# Dispenser_Motor_Controller.net
KiCad netlist of a schematic drawn in EasyEDA Pro
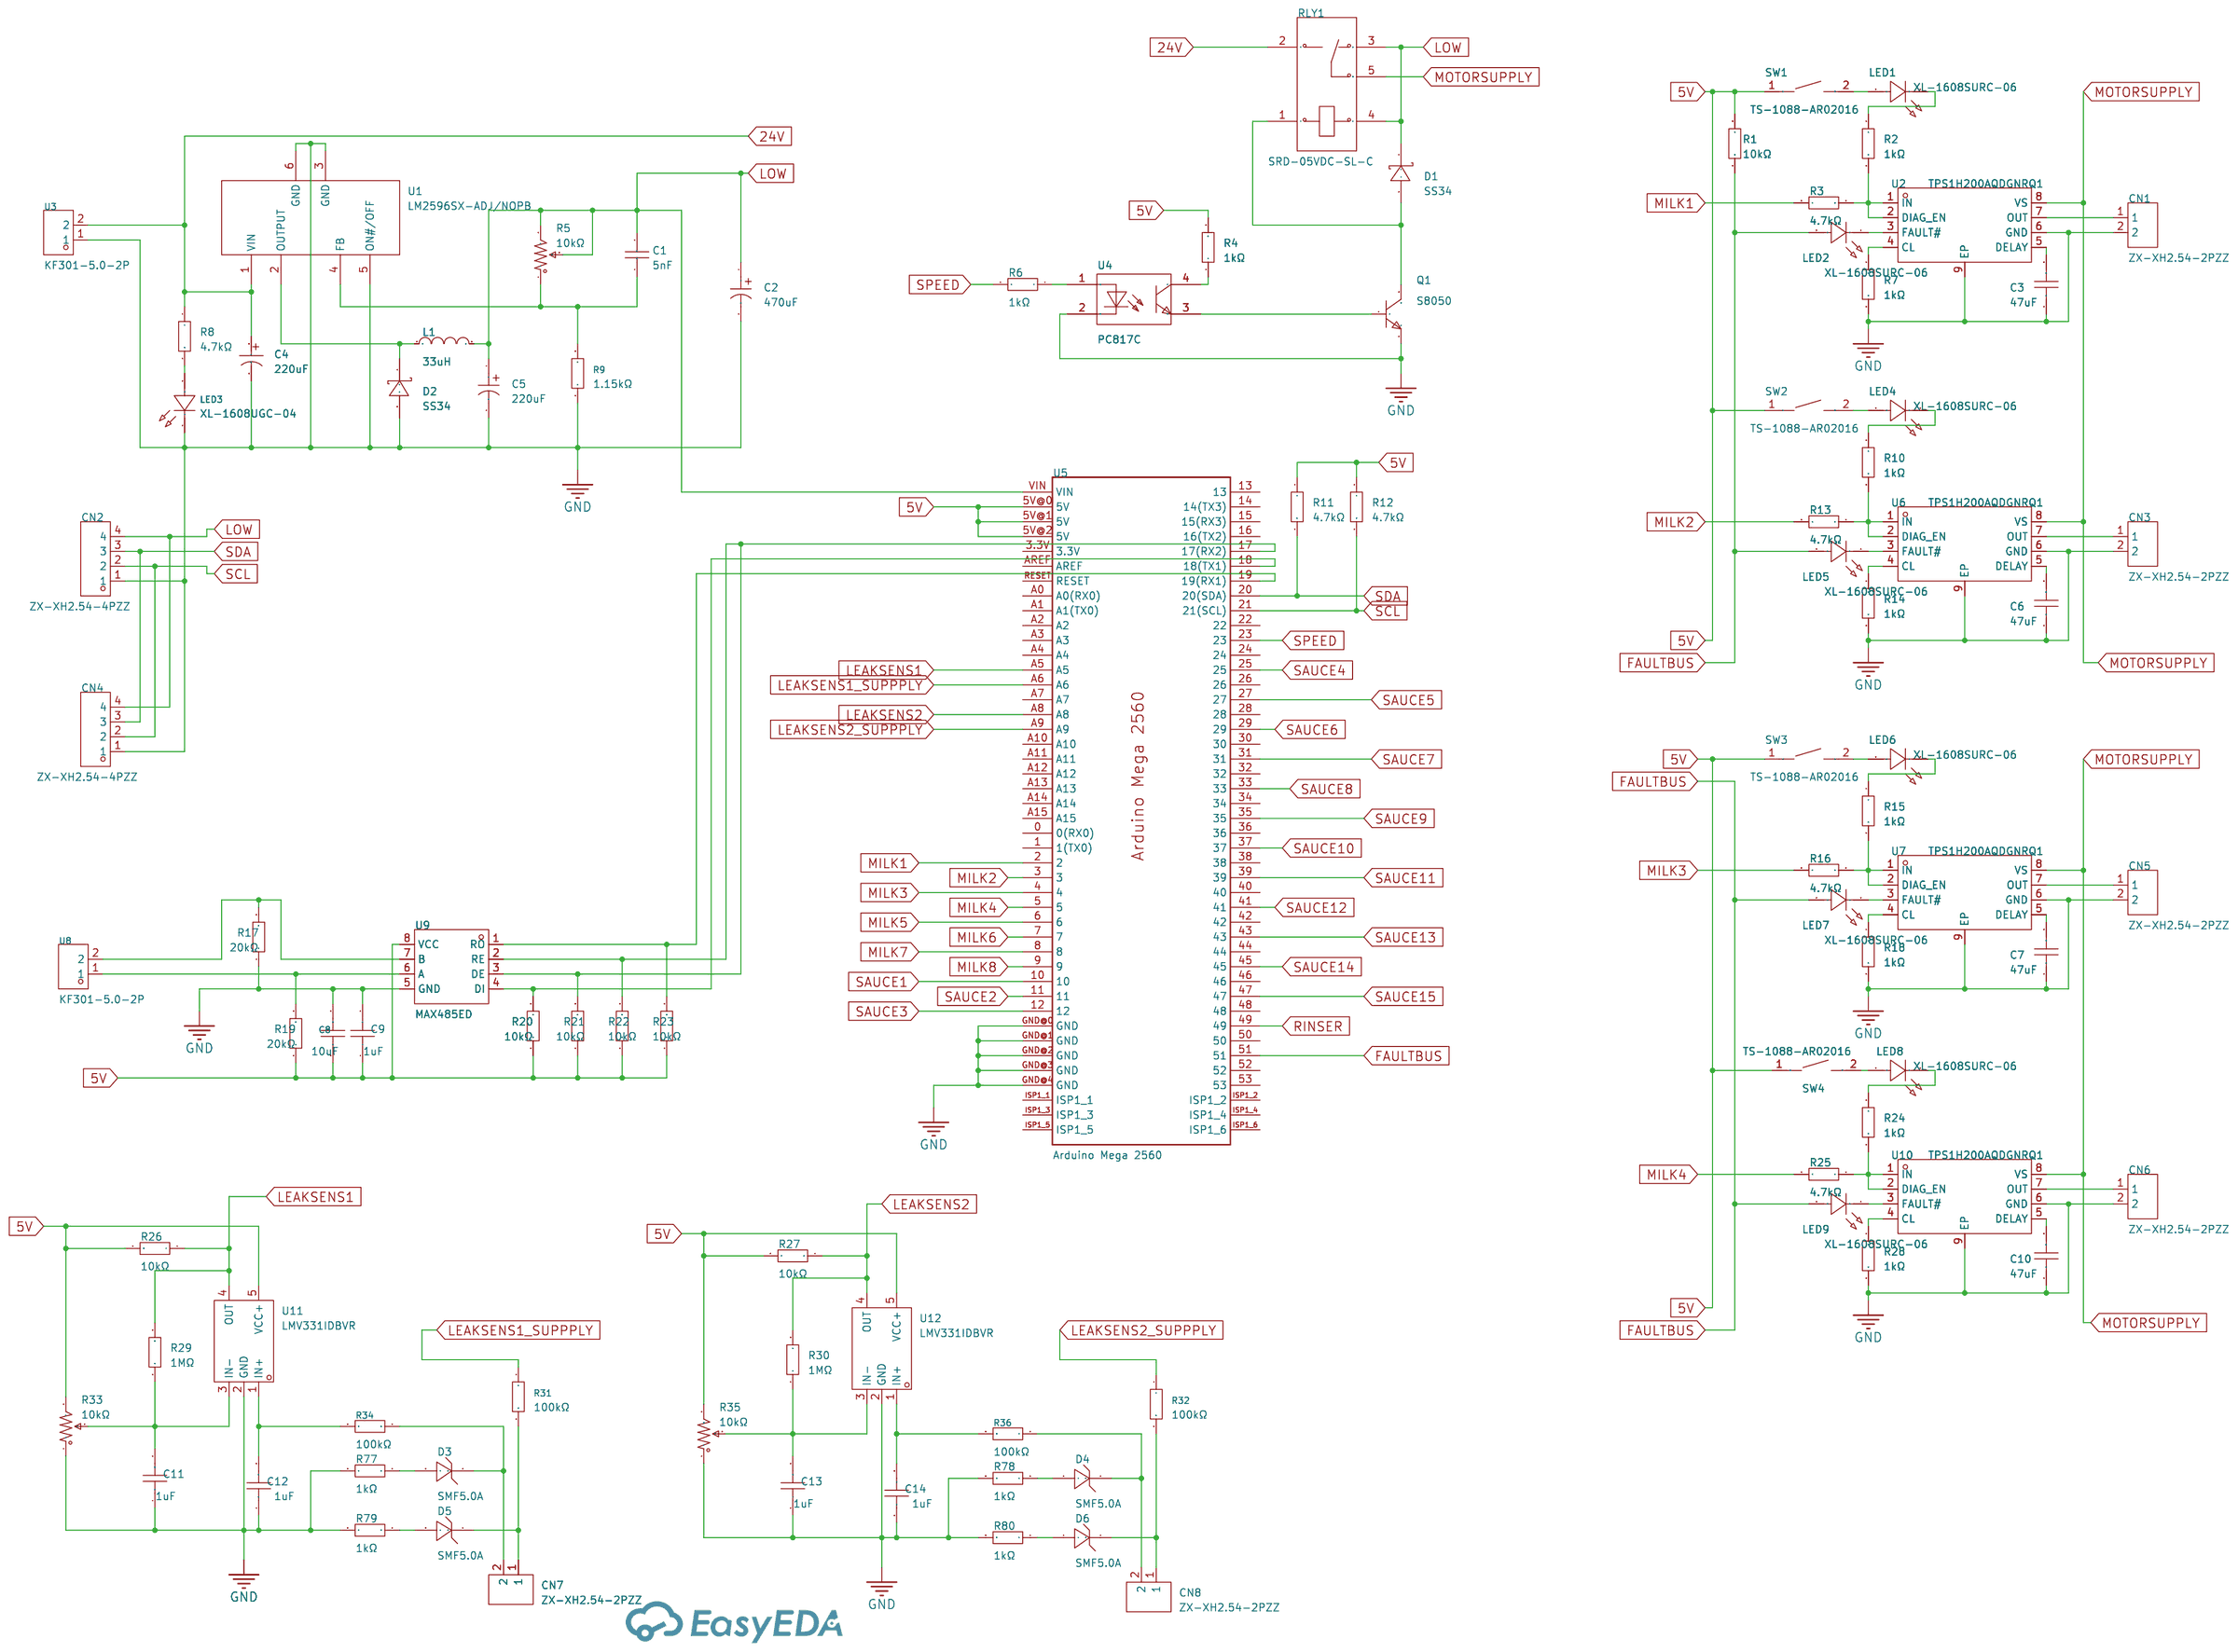
[diagram p0: P1]
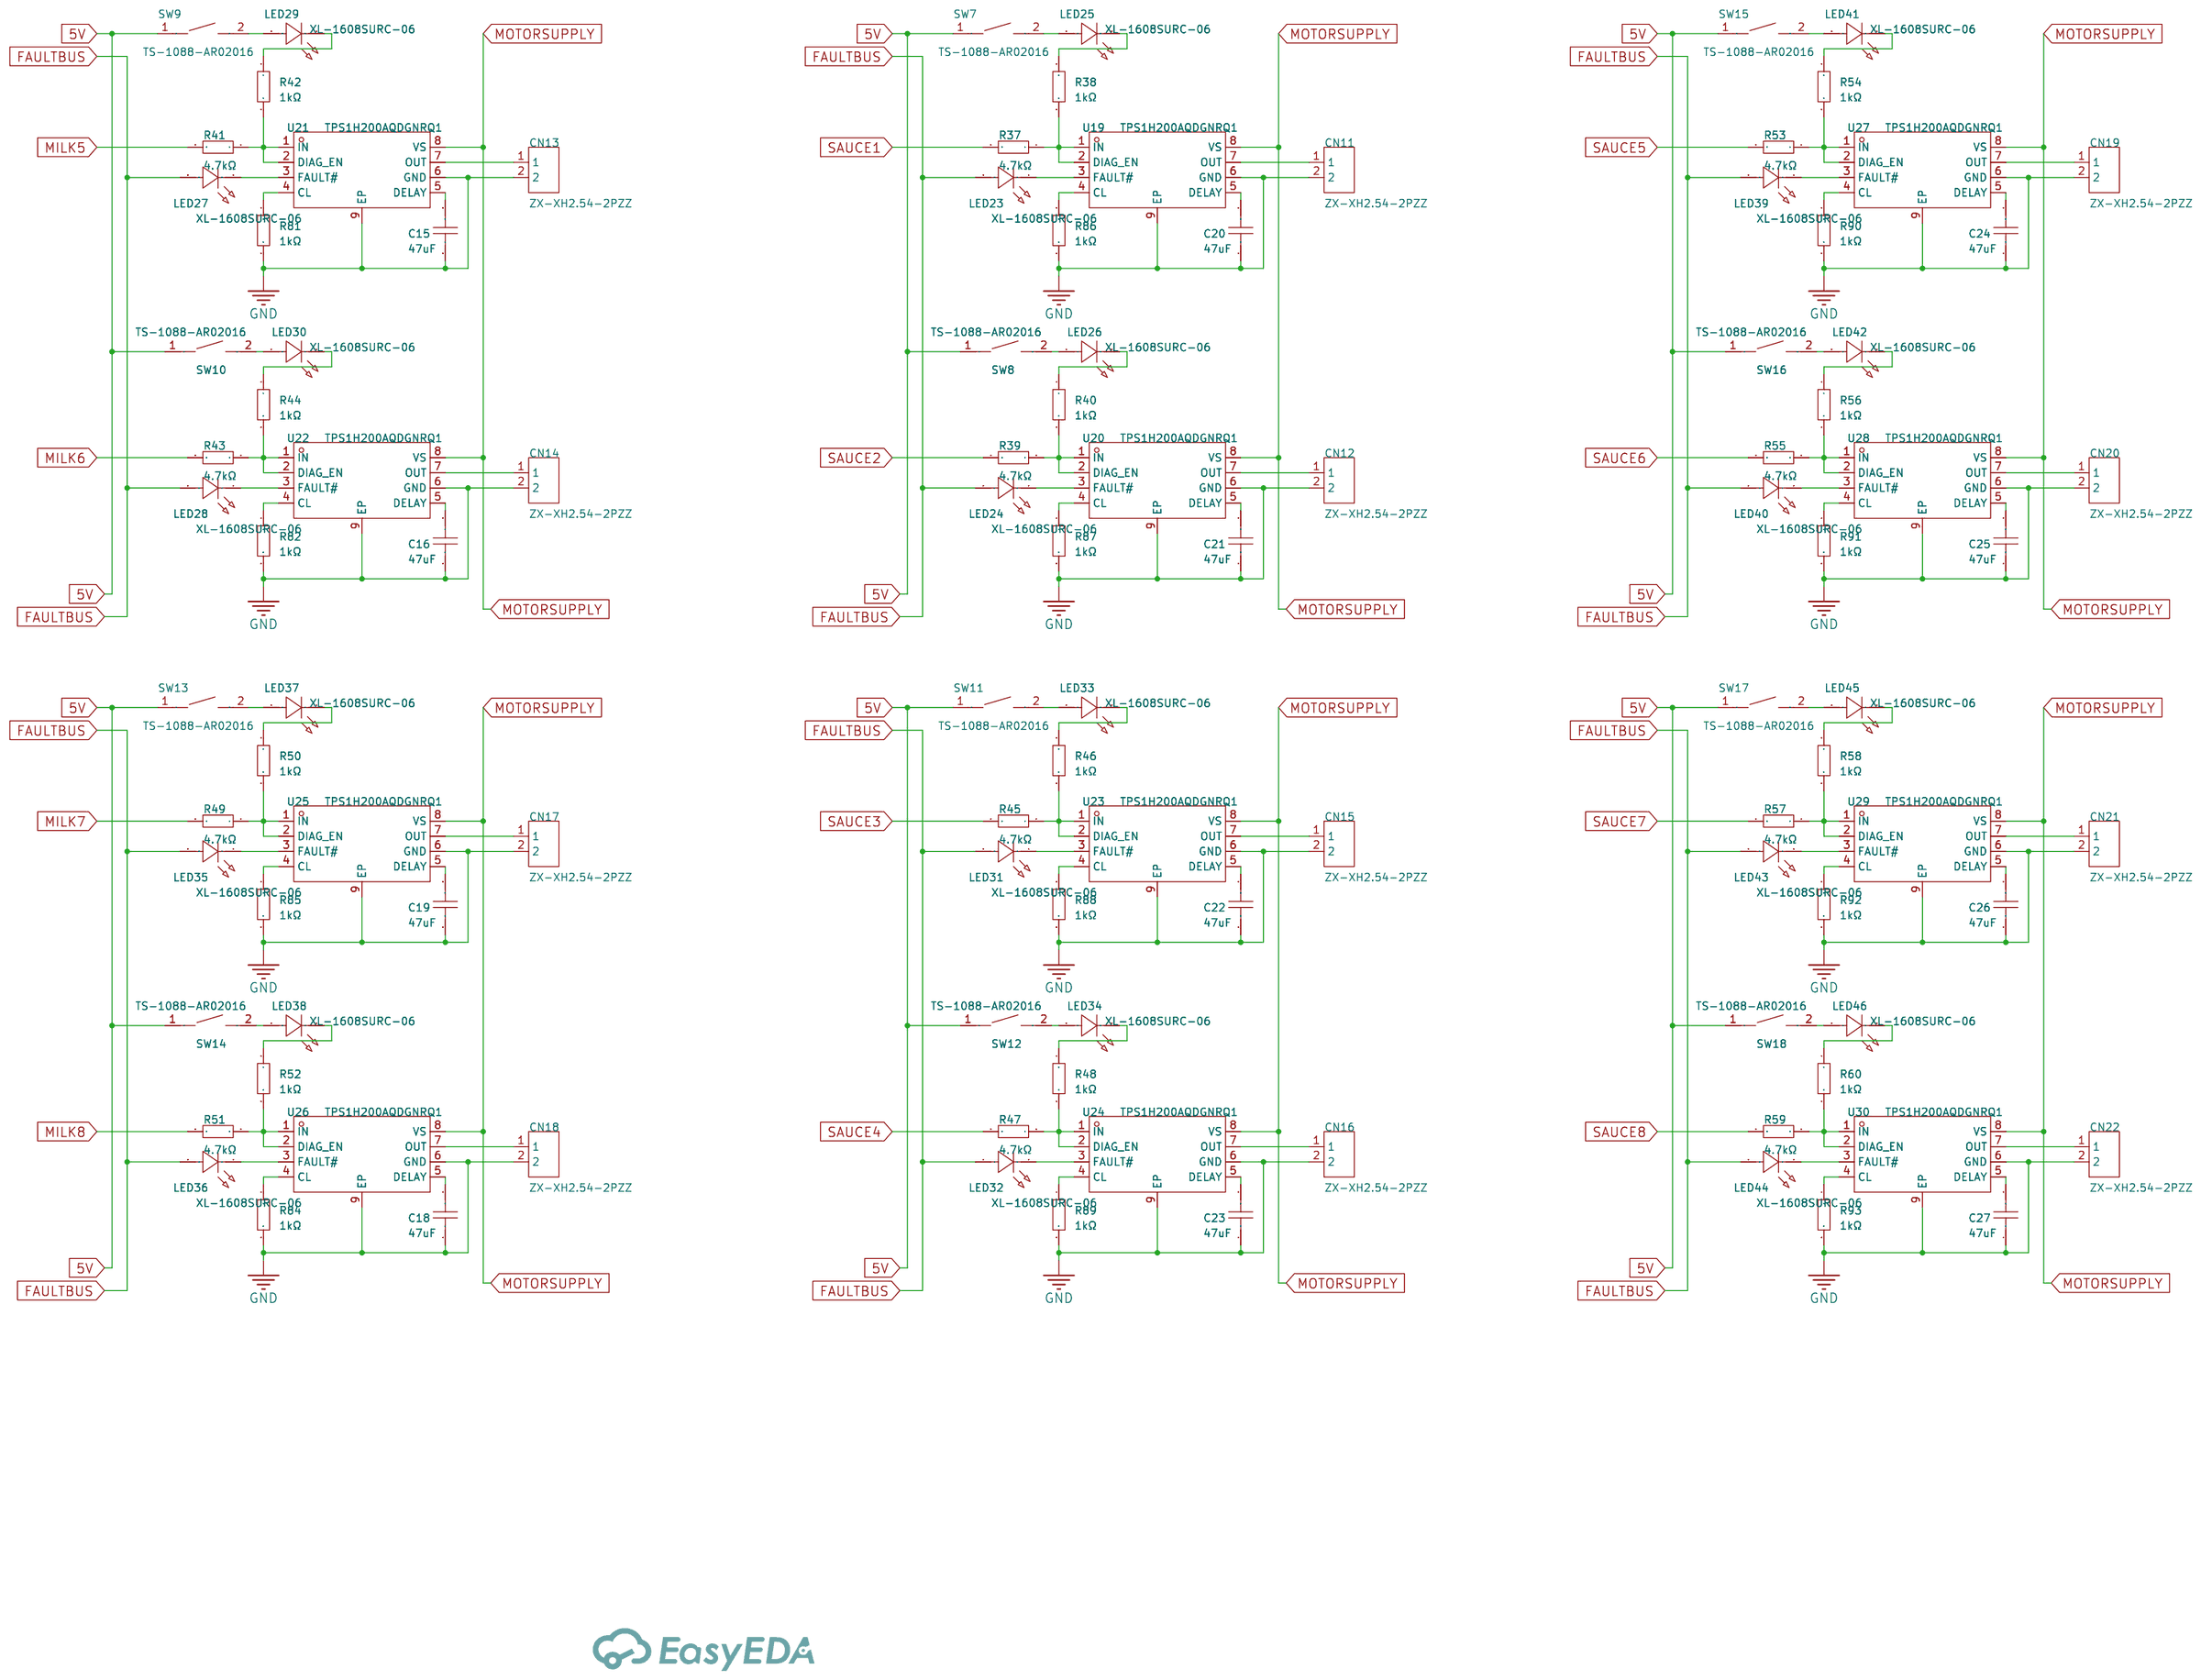
[diagram p1: P2]
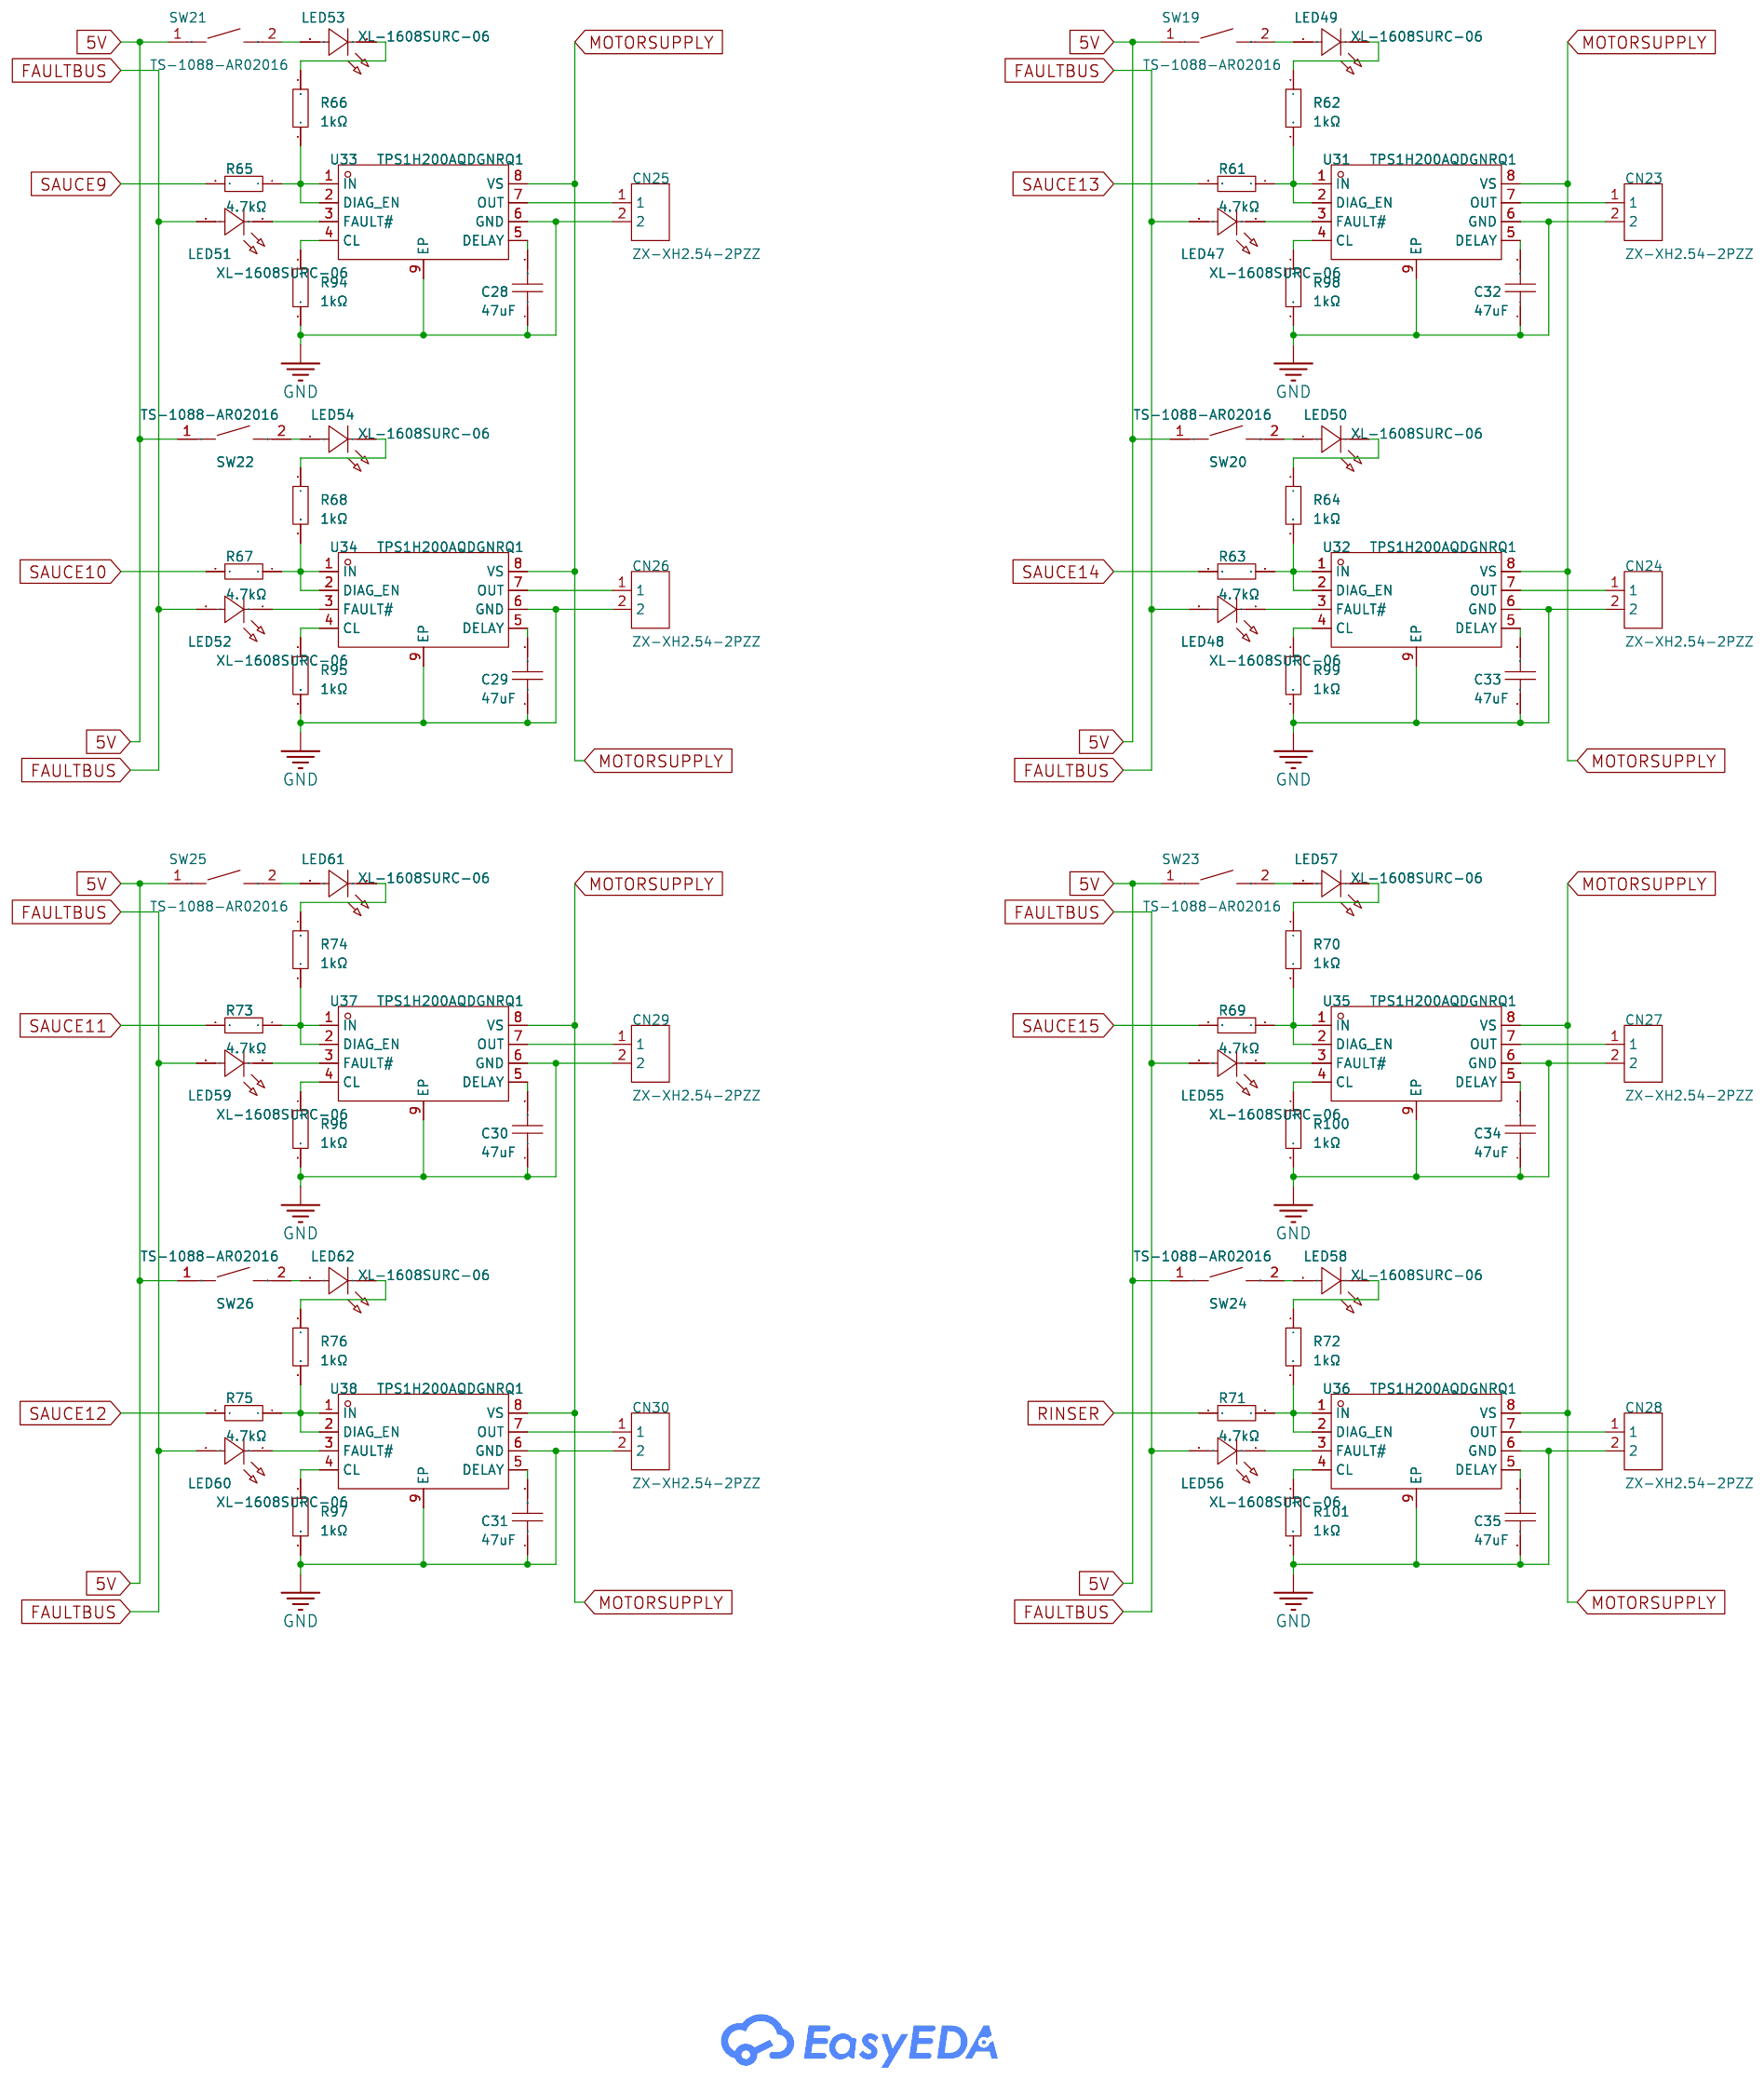
[diagram p2: P3]

(export (version "E")
  (design (tool "Eeschema 10.0.6"))
  (components
    (comp (ref "C1")
      (value "5nF")
      (footprint "easyedapro:C0805")
      (description "Capacitance:5nF Tolerance:±10% Tolerance:±10% Voltage Rating:50V Temperature Coefficient:X7R")
      (fields (field (name "Manufacturer Part") "0805B502K500NT") (field (name "Manufacturer") "FH(风华)"))
      (libsource (lib "easyedapro") (part "0805B502K500NT"))
    )
    (comp (ref "C2")
      (value "470uF")
      (footprint "easyedapro:CAP-SMD_BD8.0-L8.3-W8.3-LS9.1-FD")
      (fields
        (field (name "Manufacturer Part") "GVT1E477M0810CNVC")
        (field (name "Manufacturer") "HRK(鸿瑞凯电子)")
      )
      (libsource (lib "easyedapro") (part "GVT1E477M0810CNVC"))
    )
    (comp (ref "C3")
      (value "47uF")
      (footprint "easyedapro:C0603")
      (description "Capacitance:47uF Tolerance:±20% Tolerance:±20% Voltage Rating:6.3V Temperature Coefficient:X5R")
      (fields
        (field (name "Manufacturer Part") "CGA0603X5R476M6R3JT")
        (field (name "Manufacturer") "HRE(芯声)")
      )
      (libsource (lib "easyedapro") (part "CGA0603X5R476M6R3JT"))
    )
    (comp (ref "C4")
      (value "220uF")
      (footprint "easyedapro:CAP-SMD_BD10.0-L10.3-W10.3-LS11.3-FD")
      (fields (field (name "Manufacturer Part") "RVT1H221M1010") (field (name "Manufacturer") "ROQANG(容强)"))
      (libsource (lib "easyedapro") (part "RVT1H221M1010"))
    )
    (comp (ref "C5")
      (value "220uF")
      (footprint "easyedapro:CAP-SMD_BD6.3-L6.6-W6.6-LS7.4-FD")
      (fields (field (name "Manufacturer Part") "RVT1E221M0607") (field (name "Manufacturer") "ROQANG(容强)"))
      (libsource (lib "easyedapro") (part "RVT1E221M0607_C2918361"))
    )
    (comp (ref "C6")
      (value "47uF")
      (footprint "easyedapro:C0603")
      (description "Capacitance:47uF Tolerance:±20% Tolerance:±20% Voltage Rating:6.3V Temperature Coefficient:X5R")
      (fields
        (field (name "Manufacturer Part") "CGA0603X5R476M6R3JT")
        (field (name "Manufacturer") "HRE(芯声)")
      )
      (libsource (lib "easyedapro") (part "CGA0603X5R476M6R3JT"))
    )
    (comp (ref "C7")
      (value "47uF")
      (footprint "easyedapro:C0603")
      (description "Capacitance:47uF Tolerance:±20% Tolerance:±20% Voltage Rating:6.3V Temperature Coefficient:X5R")
      (fields
        (field (name "Manufacturer Part") "CGA0603X5R476M6R3JT")
        (field (name "Manufacturer") "HRE(芯声)")
      )
      (libsource (lib "easyedapro") (part "CGA0603X5R476M6R3JT"))
    )
    (comp (ref "C8")
      (value "10uF")
      (footprint "easyedapro:C0603")
      (fields
        (field (name "Manufacturer Part") "CL10A106MQ8NNNC")
        (field (name "Manufacturer") "SAMSUNG(三星)")
      )
      (libsource (lib "easyedapro") (part "CL10A106MQ8NNNC"))
    )
    (comp (ref "C9")
      (value "1uF")
      (footprint "easyedapro:C0603")
      (fields
        (field (name "Manufacturer Part") "CL10A105KB8NNNC")
        (field (name "Manufacturer") "SAMSUNG(三星)")
      )
      (libsource (lib "easyedapro") (part "CL10A105KB8NNNC"))
    )
    (comp (ref "C10")
      (value "47uF")
      (footprint "easyedapro:C0603")
      (description "Capacitance:47uF Tolerance:±20% Tolerance:±20% Voltage Rating:6.3V Temperature Coefficient:X5R")
      (fields
        (field (name "Manufacturer Part") "CGA0603X5R476M6R3JT")
        (field (name "Manufacturer") "HRE(芯声)")
      )
      (libsource (lib "easyedapro") (part "CGA0603X5R476M6R3JT"))
    )
    (comp (ref "C11")
      (value "1uF")
      (footprint "easyedapro:C0603")
      (fields
        (field (name "Manufacturer Part") "CL10A105KB8NNNC")
        (field (name "Manufacturer") "SAMSUNG(三星)")
      )
      (libsource (lib "easyedapro") (part "CL10A105KB8NNNC"))
    )
    (comp (ref "C12")
      (value "1uF")
      (footprint "easyedapro:C0603")
      (fields
        (field (name "Manufacturer Part") "CL10A105KB8NNNC")
        (field (name "Manufacturer") "SAMSUNG(三星)")
      )
      (libsource (lib "easyedapro") (part "CL10A105KB8NNNC"))
    )
    (comp (ref "C13")
      (value "1uF")
      (footprint "easyedapro:C0603")
      (fields
        (field (name "Manufacturer Part") "CL10A105KB8NNNC")
        (field (name "Manufacturer") "SAMSUNG(三星)")
      )
      (libsource (lib "easyedapro") (part "CL10A105KB8NNNC"))
    )
    (comp (ref "C14")
      (value "1uF")
      (footprint "easyedapro:C0603")
      (fields
        (field (name "Manufacturer Part") "CL10A105KB8NNNC")
        (field (name "Manufacturer") "SAMSUNG(三星)")
      )
      (libsource (lib "easyedapro") (part "CL10A105KB8NNNC"))
    )
    (comp (ref "CN1")
      (value "ZX-XH2.54-2PZZ")
      (footprint "easyedapro:CONN-TH_2P-P2.50_HX25003-2A")
      (fields (field (name "Manufacturer") "Megastar(兆星)"))
      (libsource (lib "easyedapro") (part "ZX-XH2.54-2PZZ"))
    )
    (comp (ref "CN2")
      (value "ZX-XH2.54-4PZZ")
      (footprint "easyedapro:CONN-TH_4P-P2.50_4PIN")
      (fields (field (name "Manufacturer") "Megastar(兆星)"))
      (libsource (lib "easyedapro") (part "ZX-XH2.54-4PZZ"))
    )
    (comp (ref "CN3")
      (value "ZX-XH2.54-2PZZ")
      (footprint "easyedapro:CONN-TH_2P-P2.50_HX25003-2A")
      (fields (field (name "Manufacturer") "Megastar(兆星)"))
      (libsource (lib "easyedapro") (part "ZX-XH2.54-2PZZ"))
    )
    (comp (ref "CN4")
      (value "ZX-XH2.54-4PZZ")
      (footprint "easyedapro:CONN-TH_4P-P2.50_4PIN")
      (fields (field (name "Manufacturer") "Megastar(兆星)"))
      (libsource (lib "easyedapro") (part "ZX-XH2.54-4PZZ"))
    )
    (comp (ref "CN5")
      (value "ZX-XH2.54-2PZZ")
      (footprint "easyedapro:CONN-TH_2P-P2.50_HX25003-2A")
      (fields (field (name "Manufacturer") "Megastar(兆星)"))
      (libsource (lib "easyedapro") (part "ZX-XH2.54-2PZZ"))
    )
    (comp (ref "CN6")
      (value "ZX-XH2.54-2PZZ")
      (footprint "easyedapro:CONN-TH_2P-P2.50_HX25003-2A")
      (fields (field (name "Manufacturer") "Megastar(兆星)"))
      (libsource (lib "easyedapro") (part "ZX-XH2.54-2PZZ"))
    )
    (comp (ref "CN7")
      (value "ZX-XH2.54-2PZZ")
      (footprint "easyedapro:CONN-TH_2P-P2.50_HX25003-2A")
      (fields (field (name "Manufacturer") "Megastar(兆星)"))
      (libsource (lib "easyedapro") (part "ZX-XH2.54-2PZZ"))
    )
    (comp (ref "CN8")
      (value "ZX-XH2.54-2PZZ")
      (footprint "easyedapro:CONN-TH_2P-P2.50_HX25003-2A")
      (fields (field (name "Manufacturer") "Megastar(兆星)"))
      (libsource (lib "easyedapro") (part "ZX-XH2.54-2PZZ"))
    )
    (comp (ref "D1")
      (value "SS34")
      (footprint "easyedapro:SMA_L4.3-W2.6-LS5.2-RD")
      (fields (field (name "Manufacturer") "MDD(辰达半导体)"))
      (libsource (lib "easyedapro") (part "SS34_C8678"))
    )
    (comp (ref "D2")
      (value "SS34")
      (footprint "easyedapro:SMA_L4.3-W2.6-LS5.2-RD")
      (fields (field (name "Manufacturer") "MDD(辰达半导体)"))
      (libsource (lib "easyedapro") (part "SS34_C8678"))
    )
    (comp (ref "D3")
      (value "SMF5.0A")
      (footprint "easyedapro:SOD-123FL_L2.7-W1.8-LS3.8-RD")
      (fields (field (name "Manufacturer") "MDD(辰达半导体)"))
      (libsource (lib "easyedapro") (part "SMF5.0A_C193402"))
    )
    (comp (ref "D4")
      (value "SMF5.0A")
      (footprint "easyedapro:SOD-123FL_L2.7-W1.8-LS3.8-RD")
      (fields (field (name "Manufacturer") "MDD(辰达半导体)"))
      (libsource (lib "easyedapro") (part "SMF5.0A_C193402"))
    )
    (comp (ref "D5")
      (value "SMF5.0A")
      (footprint "easyedapro:SOD-123FL_L2.7-W1.8-LS3.8-RD")
      (fields (field (name "Manufacturer") "MDD(辰达半导体)"))
      (libsource (lib "easyedapro") (part "SMF5.0A_C193402"))
    )
    (comp (ref "D6")
      (value "SMF5.0A")
      (footprint "easyedapro:SOD-123FL_L2.7-W1.8-LS3.8-RD")
      (fields (field (name "Manufacturer") "MDD(辰达半导体)"))
      (libsource (lib "easyedapro") (part "SMF5.0A_C193402"))
    )
    (comp (ref "L1")
      (value "33uH")
      (footprint "easyedapro:IND-SMD_L12.3-W12.3")
      (fields (field (name "Manufacturer Part") "SMDRI127-330MT") (field (name "Manufacturer") "SXN(顺翔诺)"))
      (libsource (lib "easyedapro") (part "SMDRI127-330MT"))
    )
    (comp (ref "LED1")
      (value "XL-1608SURC-06")
      (footprint "easyedapro:LED0603-RD_RED")
      (fields (field (name "Manufacturer") "XINGLIGHT(成兴光)"))
      (libsource (lib "easyedapro") (part "XL-1608SURC-06"))
    )
    (comp (ref "LED2")
      (value "XL-1608SURC-06")
      (footprint "easyedapro:LED0603-RD_RED")
      (fields (field (name "Manufacturer") "XINGLIGHT(成兴光)"))
      (libsource (lib "easyedapro") (part "XL-1608SURC-06"))
    )
    (comp (ref "LED3")
      (value "XL-1608UGC-04")
      (footprint "easyedapro:LED0603-RD_GREEN")
      (fields (field (name "Manufacturer") "XINGLIGHT(成兴光)"))
      (libsource (lib "easyedapro") (part "XL-1608UGC-04"))
    )
    (comp (ref "LED4")
      (value "XL-1608SURC-06")
      (footprint "easyedapro:LED0603-RD_RED")
      (fields (field (name "Manufacturer") "XINGLIGHT(成兴光)"))
      (libsource (lib "easyedapro") (part "XL-1608SURC-06"))
    )
    (comp (ref "LED5")
      (value "XL-1608SURC-06")
      (footprint "easyedapro:LED0603-RD_RED")
      (fields (field (name "Manufacturer") "XINGLIGHT(成兴光)"))
      (libsource (lib "easyedapro") (part "XL-1608SURC-06"))
    )
    (comp (ref "LED6")
      (value "XL-1608SURC-06")
      (footprint "easyedapro:LED0603-RD_RED")
      (fields (field (name "Manufacturer") "XINGLIGHT(成兴光)"))
      (libsource (lib "easyedapro") (part "XL-1608SURC-06"))
    )
    (comp (ref "LED7")
      (value "XL-1608SURC-06")
      (footprint "easyedapro:LED0603-RD_RED")
      (fields (field (name "Manufacturer") "XINGLIGHT(成兴光)"))
      (libsource (lib "easyedapro") (part "XL-1608SURC-06"))
    )
    (comp (ref "LED8")
      (value "XL-1608SURC-06")
      (footprint "easyedapro:LED0603-RD_RED")
      (fields (field (name "Manufacturer") "XINGLIGHT(成兴光)"))
      (libsource (lib "easyedapro") (part "XL-1608SURC-06"))
    )
    (comp (ref "LED9")
      (value "XL-1608SURC-06")
      (footprint "easyedapro:LED0603-RD_RED")
      (fields (field (name "Manufacturer") "XINGLIGHT(成兴光)"))
      (libsource (lib "easyedapro") (part "XL-1608SURC-06"))
    )
    (comp (ref "Q1")
      (value "S8050")
      (footprint "easyedapro:SOT-23-3_L2.9-W1.6-P1.90-LS2.8-BR")
      (fields (field (name "Manufacturer") "Hottech(合科泰)"))
      (libsource (lib "easyedapro") (part "S8050_C181158"))
    )
    (comp (ref "R1")
      (value "10kΩ")
      (footprint "easyedapro:R0603")
      (fields (field (name "Manufacturer Part") "RC0603FR-0710KL") (field (name "Manufacturer") "YAGEO(国巨)"))
      (libsource (lib "easyedapro") (part "RC0603FR-0710KL"))
    )
    (comp (ref "R2")
      (value "1kΩ")
      (footprint "easyedapro:R0603")
      (fields
        (field (name "Manufacturer Part") "0603WAF1001T5E")
        (field (name "Manufacturer") "UNI-ROYAL(厚声)")
      )
      (libsource (lib "easyedapro") (part "0603WAF1001T5E"))
    )
    (comp (ref "R3")
      (value "4.7kΩ")
      (footprint "easyedapro:R0603")
      (fields
        (field (name "Manufacturer Part") "0603WAF4701T5E")
        (field (name "Manufacturer") "UNI-ROYAL(厚声)")
      )
      (libsource (lib "easyedapro") (part "0603WAF4701T5E"))
    )
    (comp (ref "R4")
      (value "1kΩ")
      (footprint "easyedapro:R0603")
      (fields
        (field (name "Manufacturer Part") "0603WAF1001T5E")
        (field (name "Manufacturer") "UNI-ROYAL(厚声)")
      )
      (libsource (lib "easyedapro") (part "0603WAF1001T5E"))
    )
    (comp (ref "R5")
      (value "10kΩ")
      (footprint "easyedapro:RES-ADJ-TH_3P-L10.0-W10.0-P2.50-L")
      (description "Resistance: Tolerance:±10% Tolerance:±10%")
      (fields (field (name "Manufacturer Part") "3296W-1-103") (field (name "Manufacturer") "BOCHEN(博晨)"))
      (libsource (lib "easyedapro") (part "3296W-1-103"))
    )
    (comp (ref "R6")
      (value "1kΩ")
      (footprint "easyedapro:R0603")
      (fields
        (field (name "Manufacturer Part") "0603WAF1001T5E")
        (field (name "Manufacturer") "UNI-ROYAL(厚声)")
      )
      (libsource (lib "easyedapro") (part "0603WAF1001T5E"))
    )
    (comp (ref "R7")
      (value "1kΩ")
      (footprint "easyedapro:R0603")
      (fields
        (field (name "Manufacturer Part") "0603WAF1001T5E")
        (field (name "Manufacturer") "UNI-ROYAL(厚声)")
      )
      (libsource (lib "easyedapro") (part "0603WAF1001T5E"))
    )
    (comp (ref "R8")
      (value "4.7kΩ")
      (footprint "easyedapro:R0603")
      (fields
        (field (name "Manufacturer Part") "0603WAF4701T5E")
        (field (name "Manufacturer") "UNI-ROYAL(厚声)")
      )
      (libsource (lib "easyedapro") (part "0603WAF4701T5E"))
    )
    (comp (ref "R9")
      (value "1.15kΩ")
      (footprint "easyedapro:R0603")
      (fields
        (field (name "Manufacturer Part") "0603WAF1151T5E")
        (field (name "Manufacturer") "UNI-ROYAL(厚声)")
      )
      (libsource (lib "easyedapro") (part "0603WAF1151T5E"))
    )
    (comp (ref "R10")
      (value "1kΩ")
      (footprint "easyedapro:R0603")
      (fields
        (field (name "Manufacturer Part") "0603WAF1001T5E")
        (field (name "Manufacturer") "UNI-ROYAL(厚声)")
      )
      (libsource (lib "easyedapro") (part "0603WAF1001T5E"))
    )
    (comp (ref "R11")
      (value "4.7kΩ")
      (footprint "easyedapro:R0603")
      (fields
        (field (name "Manufacturer Part") "0603WAF4701T5E")
        (field (name "Manufacturer") "UNI-ROYAL(厚声)")
      )
      (libsource (lib "easyedapro") (part "0603WAF4701T5E"))
    )
    (comp (ref "R12")
      (value "4.7kΩ")
      (footprint "easyedapro:R0603")
      (fields
        (field (name "Manufacturer Part") "0603WAF4701T5E")
        (field (name "Manufacturer") "UNI-ROYAL(厚声)")
      )
      (libsource (lib "easyedapro") (part "0603WAF4701T5E"))
    )
    (comp (ref "R13")
      (value "4.7kΩ")
      (footprint "easyedapro:R0603")
      (fields
        (field (name "Manufacturer Part") "0603WAF4701T5E")
        (field (name "Manufacturer") "UNI-ROYAL(厚声)")
      )
      (libsource (lib "easyedapro") (part "0603WAF4701T5E"))
    )
    (comp (ref "R14")
      (value "1kΩ")
      (footprint "easyedapro:R0603")
      (fields
        (field (name "Manufacturer Part") "0603WAF1001T5E")
        (field (name "Manufacturer") "UNI-ROYAL(厚声)")
      )
      (libsource (lib "easyedapro") (part "0603WAF1001T5E"))
    )
    (comp (ref "R15")
      (value "1kΩ")
      (footprint "easyedapro:R0603")
      (fields
        (field (name "Manufacturer Part") "0603WAF1001T5E")
        (field (name "Manufacturer") "UNI-ROYAL(厚声)")
      )
      (libsource (lib "easyedapro") (part "0603WAF1001T5E"))
    )
    (comp (ref "R16")
      (value "4.7kΩ")
      (footprint "easyedapro:R0603")
      (fields
        (field (name "Manufacturer Part") "0603WAF4701T5E")
        (field (name "Manufacturer") "UNI-ROYAL(厚声)")
      )
      (libsource (lib "easyedapro") (part "0603WAF4701T5E"))
    )
    (comp (ref "R17")
      (value "20kΩ")
      (footprint "easyedapro:R0603")
      (fields (field (name "Manufacturer Part") "SCR0603J20K") (field (name "Manufacturer") "VO(翔胜)"))
      (libsource (lib "easyedapro") (part "RC0603FR-0710KL"))
    )
    (comp (ref "R18")
      (value "1kΩ")
      (footprint "easyedapro:R0603")
      (fields
        (field (name "Manufacturer Part") "0603WAF1001T5E")
        (field (name "Manufacturer") "UNI-ROYAL(厚声)")
      )
      (libsource (lib "easyedapro") (part "0603WAF1001T5E"))
    )
    (comp (ref "R19")
      (value "20kΩ")
      (footprint "easyedapro:R0603")
      (fields (field (name "Manufacturer Part") "SCR0603J20K") (field (name "Manufacturer") "VO(翔胜)"))
      (libsource (lib "easyedapro") (part "RC0603FR-0710KL"))
    )
    (comp (ref "R20")
      (value "10kΩ")
      (footprint "easyedapro:R0603")
      (fields (field (name "Manufacturer Part") "RC0603FR-0710KL") (field (name "Manufacturer") "YAGEO(国巨)"))
      (libsource (lib "easyedapro") (part "RC0603FR-0710KL"))
    )
    (comp (ref "R21")
      (value "10kΩ")
      (footprint "easyedapro:R0603")
      (fields (field (name "Manufacturer Part") "RC0603FR-0710KL") (field (name "Manufacturer") "YAGEO(国巨)"))
      (libsource (lib "easyedapro") (part "RC0603FR-0710KL"))
    )
    (comp (ref "R22")
      (value "10kΩ")
      (footprint "easyedapro:R0603")
      (fields (field (name "Manufacturer Part") "RC0603FR-0710KL") (field (name "Manufacturer") "YAGEO(国巨)"))
      (libsource (lib "easyedapro") (part "RC0603FR-0710KL"))
    )
    (comp (ref "R23")
      (value "10kΩ")
      (footprint "easyedapro:R0603")
      (fields (field (name "Manufacturer Part") "RC0603FR-0710KL") (field (name "Manufacturer") "YAGEO(国巨)"))
      (libsource (lib "easyedapro") (part "RC0603FR-0710KL"))
    )
    (comp (ref "R24")
      (value "1kΩ")
      (footprint "easyedapro:R0603")
      (fields
        (field (name "Manufacturer Part") "0603WAF1001T5E")
        (field (name "Manufacturer") "UNI-ROYAL(厚声)")
      )
      (libsource (lib "easyedapro") (part "0603WAF1001T5E"))
    )
    (comp (ref "R25")
      (value "4.7kΩ")
      (footprint "easyedapro:R0603")
      (fields
        (field (name "Manufacturer Part") "0603WAF4701T5E")
        (field (name "Manufacturer") "UNI-ROYAL(厚声)")
      )
      (libsource (lib "easyedapro") (part "0603WAF4701T5E"))
    )
    (comp (ref "R26")
      (value "10kΩ")
      (footprint "easyedapro:R0603")
      (fields (field (name "Manufacturer Part") "RC0603FR-0710KL") (field (name "Manufacturer") "YAGEO(国巨)"))
      (libsource (lib "easyedapro") (part "RC0603FR-0710KL"))
    )
    (comp (ref "R27")
      (value "10kΩ")
      (footprint "easyedapro:R0603")
      (fields (field (name "Manufacturer Part") "RC0603FR-0710KL") (field (name "Manufacturer") "YAGEO(国巨)"))
      (libsource (lib "easyedapro") (part "RC0603FR-0710KL"))
    )
    (comp (ref "R28")
      (value "1kΩ")
      (footprint "easyedapro:R0603")
      (fields
        (field (name "Manufacturer Part") "0603WAF1001T5E")
        (field (name "Manufacturer") "UNI-ROYAL(厚声)")
      )
      (libsource (lib "easyedapro") (part "0603WAF1001T5E"))
    )
    (comp (ref "R29")
      (value "1MΩ")
      (footprint "easyedapro:R0603")
      (fields (field (name "Manufacturer Part") "RC0603FR-071ML") (field (name "Manufacturer") "YAGEO(国巨)"))
      (libsource (lib "easyedapro") (part "RC0603FR-071ML"))
    )
    (comp (ref "R30")
      (value "1MΩ")
      (footprint "easyedapro:R0603")
      (fields (field (name "Manufacturer Part") "RC0603FR-071ML") (field (name "Manufacturer") "YAGEO(国巨)"))
      (libsource (lib "easyedapro") (part "RC0603FR-071ML"))
    )
    (comp (ref "R31")
      (value "100kΩ")
      (footprint "easyedapro:R0603")
      (fields (field (name "Manufacturer Part") "RC0603FR-07100KL") (field (name "Manufacturer") "YAGEO(国巨)"))
      (libsource (lib "easyedapro") (part "RC0603FR-07100KL"))
    )
    (comp (ref "R32")
      (value "100kΩ")
      (footprint "easyedapro:R0603")
      (fields (field (name "Manufacturer Part") "RC0603FR-07100KL") (field (name "Manufacturer") "YAGEO(国巨)"))
      (libsource (lib "easyedapro") (part "RC0603FR-07100KL"))
    )
    (comp (ref "R33")
      (value "10kΩ")
      (footprint "easyedapro:RES-ADJ-TH_3P-L10.0-W10.0-P2.50-L")
      (description "Resistance: Tolerance:±10% Tolerance:±10%")
      (fields (field (name "Manufacturer Part") "3296W-1-103") (field (name "Manufacturer") "BOCHEN(博晨)"))
      (libsource (lib "easyedapro") (part "3296W-1-103"))
    )
    (comp (ref "R34")
      (value "100kΩ")
      (footprint "easyedapro:R0603")
      (fields (field (name "Manufacturer Part") "RC0603FR-07100KL") (field (name "Manufacturer") "YAGEO(国巨)"))
      (libsource (lib "easyedapro") (part "RC0603FR-07100KL"))
    )
    (comp (ref "R35")
      (value "10kΩ")
      (footprint "easyedapro:RES-ADJ-TH_3P-L10.0-W10.0-P2.50-L")
      (description "Resistance: Tolerance:±10% Tolerance:±10%")
      (fields (field (name "Manufacturer Part") "3296W-1-103") (field (name "Manufacturer") "BOCHEN(博晨)"))
      (libsource (lib "easyedapro") (part "3296W-1-103"))
    )
    (comp (ref "R36")
      (value "100kΩ")
      (footprint "easyedapro:R0603")
      (fields (field (name "Manufacturer Part") "RC0603FR-07100KL") (field (name "Manufacturer") "YAGEO(国巨)"))
      (libsource (lib "easyedapro") (part "RC0603FR-07100KL"))
    )
    (comp (ref "R77")
      (value "1kΩ")
      (footprint "easyedapro:R0603")
      (fields
        (field (name "Manufacturer Part") "0603WAF1001T5E")
        (field (name "Manufacturer") "UNI-ROYAL(厚声)")
      )
      (libsource (lib "easyedapro") (part "0603WAF1001T5E"))
    )
    (comp (ref "R78")
      (value "1kΩ")
      (footprint "easyedapro:R0603")
      (fields
        (field (name "Manufacturer Part") "0603WAF1001T5E")
        (field (name "Manufacturer") "UNI-ROYAL(厚声)")
      )
      (libsource (lib "easyedapro") (part "0603WAF1001T5E"))
    )
    (comp (ref "R79")
      (value "1kΩ")
      (footprint "easyedapro:R0603")
      (fields
        (field (name "Manufacturer Part") "0603WAF1001T5E")
        (field (name "Manufacturer") "UNI-ROYAL(厚声)")
      )
      (libsource (lib "easyedapro") (part "0603WAF1001T5E"))
    )
    (comp (ref "R80")
      (value "1kΩ")
      (footprint "easyedapro:R0603")
      (fields
        (field (name "Manufacturer Part") "0603WAF1001T5E")
        (field (name "Manufacturer") "UNI-ROYAL(厚声)")
      )
      (libsource (lib "easyedapro") (part "0603WAF1001T5E"))
    )
    (comp (ref "RLY1")
      (value "SRD-05VDC-SL-C")
      (footprint "easyedapro:RELAY-TH_SRD-XXVDC-XL-C")
      (fields (field (name "Manufacturer") "松乐"))
      (libsource (lib "easyedapro") (part "SRD-05VDC-SL-C"))
    )
    (comp (ref "SW1")
      (value "TS-1088-AR02016")
      (footprint "easyedapro:SW-SMD_L3.9-W3.0-P4.45")
      (fields (field (name "Manufacturer") "XUNPU(讯普)"))
      (libsource (lib "easyedapro") (part "TS-1088-AR02016"))
    )
    (comp (ref "SW2")
      (value "TS-1088-AR02016")
      (footprint "easyedapro:SW-SMD_L3.9-W3.0-P4.45")
      (fields (field (name "Manufacturer") "XUNPU(讯普)"))
      (libsource (lib "easyedapro") (part "TS-1088-AR02016"))
    )
    (comp (ref "SW3")
      (value "TS-1088-AR02016")
      (footprint "easyedapro:SW-SMD_L3.9-W3.0-P4.45")
      (fields (field (name "Manufacturer") "XUNPU(讯普)"))
      (libsource (lib "easyedapro") (part "TS-1088-AR02016"))
    )
    (comp (ref "SW4")
      (value "TS-1088-AR02016")
      (footprint "easyedapro:SW-SMD_L3.9-W3.0-P4.45")
      (fields (field (name "Manufacturer") "XUNPU(讯普)"))
      (libsource (lib "easyedapro") (part "TS-1088-AR02016"))
    )
    (comp (ref "U1")
      (value "LM2596SX-ADJ/NOPB")
      (footprint "easyedapro:TO-263-5_L10.2-W8.9-P1.70-TL")
      (fields (field (name "Manufacturer") "TI(德州仪器)"))
      (libsource (lib "easyedapro") (part "LM2596SX-ADJ/NOPB"))
    )
    (comp (ref "U2")
      (value "TPS1H200AQDGNRQ1")
      (footprint "easyedapro:EMSOP-8_L3.0-W3.0-P0.65-LS4.9-BL-EP-A")
      (fields (field (name "Manufacturer") "TI(德州仪器)"))
      (libsource (lib "easyedapro") (part "TPS1H200AQDGNRQ1"))
    )
    (comp (ref "U3")
      (value "KF301-5.0-2P")
      (footprint "easyedapro:CONN-TH_P5.00_KF301-5.0-2P")
      (fields (field (name "Manufacturer") "KEFA(科发)"))
      (libsource (lib "easyedapro") (part "KF301-5.0-2P"))
    )
    (comp (ref "U4")
      (value "PC817C")
      (footprint "easyedapro:OPTO-SMD-4_L4.6-W6.5-P2.54-LS10.3-TL")
      (fields (field (name "Manufacturer") "GOODWORK(固得沃克)"))
      (libsource (lib "easyedapro") (part "PC817C_C3025164"))
    )
    (comp (ref "U5")
      (value "Arduino Mega 2560")
      (footprint "easyedapro:ARDUINO MEGA 2560 ADDON ON PCB")
      (libsource (lib "easyedapro") (part "Arduino Mega 2560"))
    )
    (comp (ref "U6")
      (value "TPS1H200AQDGNRQ1")
      (footprint "easyedapro:EMSOP-8_L3.0-W3.0-P0.65-LS4.9-BL-EP-A")
      (fields (field (name "Manufacturer") "TI(德州仪器)"))
      (libsource (lib "easyedapro") (part "TPS1H200AQDGNRQ1"))
    )
    (comp (ref "U7")
      (value "TPS1H200AQDGNRQ1")
      (footprint "easyedapro:EMSOP-8_L3.0-W3.0-P0.65-LS4.9-BL-EP-A")
      (fields (field (name "Manufacturer") "TI(德州仪器)"))
      (libsource (lib "easyedapro") (part "TPS1H200AQDGNRQ1"))
    )
    (comp (ref "U8")
      (value "KF301-5.0-2P")
      (footprint "easyedapro:CONN-TH_P5.00_KF301-5.0-2P")
      (fields (field (name "Manufacturer") "KEFA(科发)"))
      (libsource (lib "easyedapro") (part "KF301-5.0-2P"))
    )
    (comp (ref "U9")
      (value "MAX485ED")
      (footprint "easyedapro:SOP-8_L4.9-W3.9-P1.27-LS6.0-BL")
      (fields (field (name "Manufacturer") "HTC"))
      (libsource (lib "easyedapro") (part "MAX485ED"))
    )
    (comp (ref "U10")
      (value "TPS1H200AQDGNRQ1")
      (footprint "easyedapro:EMSOP-8_L3.0-W3.0-P0.65-LS4.9-BL-EP-A")
      (fields (field (name "Manufacturer") "TI(德州仪器)"))
      (libsource (lib "easyedapro") (part "TPS1H200AQDGNRQ1"))
    )
    (comp (ref "U11")
      (value "LMV331IDBVR")
      (footprint "easyedapro:SOT-23-5_L3.0-W1.7-P0.95-LS2.8-BR")
      (fields (field (name "Manufacturer") "TI(德州仪器)"))
      (libsource (lib "easyedapro") (part "LMV331IDBVR"))
    )
    (comp (ref "U12")
      (value "LMV331IDBVR")
      (footprint "easyedapro:SOT-23-5_L3.0-W1.7-P0.95-LS2.8-BR")
      (fields (field (name "Manufacturer") "TI(德州仪器)"))
      (libsource (lib "easyedapro") (part "LMV331IDBVR"))
    )
    (comp (ref "C15")
      (value "47uF")
      (footprint "easyedapro:C0603")
      (description "Capacitance:47uF Tolerance:±20% Tolerance:±20% Voltage Rating:6.3V Temperature Coefficient:X5R")
      (fields
        (field (name "Manufacturer Part") "CGA0603X5R476M6R3JT")
        (field (name "Manufacturer") "HRE(芯声)")
      )
      (libsource (lib "easyedapro") (part "CGA0603X5R476M6R3JT"))
    )
    (comp (ref "C16")
      (value "47uF")
      (footprint "easyedapro:C0603")
      (description "Capacitance:47uF Tolerance:±20% Tolerance:±20% Voltage Rating:6.3V Temperature Coefficient:X5R")
      (fields
        (field (name "Manufacturer Part") "CGA0603X5R476M6R3JT")
        (field (name "Manufacturer") "HRE(芯声)")
      )
      (libsource (lib "easyedapro") (part "CGA0603X5R476M6R3JT"))
    )
    (comp (ref "C18")
      (value "47uF")
      (footprint "easyedapro:C0603")
      (description "Capacitance:47uF Tolerance:±20% Tolerance:±20% Voltage Rating:6.3V Temperature Coefficient:X5R")
      (fields
        (field (name "Manufacturer Part") "CGA0603X5R476M6R3JT")
        (field (name "Manufacturer") "HRE(芯声)")
      )
      (libsource (lib "easyedapro") (part "CGA0603X5R476M6R3JT"))
    )
    (comp (ref "C19")
      (value "47uF")
      (footprint "easyedapro:C0603")
      (description "Capacitance:47uF Tolerance:±20% Tolerance:±20% Voltage Rating:6.3V Temperature Coefficient:X5R")
      (fields
        (field (name "Manufacturer Part") "CGA0603X5R476M6R3JT")
        (field (name "Manufacturer") "HRE(芯声)")
      )
      (libsource (lib "easyedapro") (part "CGA0603X5R476M6R3JT"))
    )
    (comp (ref "C20")
      (value "47uF")
      (footprint "easyedapro:C0603")
      (description "Capacitance:47uF Tolerance:±20% Tolerance:±20% Voltage Rating:6.3V Temperature Coefficient:X5R")
      (fields
        (field (name "Manufacturer Part") "CGA0603X5R476M6R3JT")
        (field (name "Manufacturer") "HRE(芯声)")
      )
      (libsource (lib "easyedapro") (part "CGA0603X5R476M6R3JT"))
    )
    (comp (ref "C21")
      (value "47uF")
      (footprint "easyedapro:C0603")
      (description "Capacitance:47uF Tolerance:±20% Tolerance:±20% Voltage Rating:6.3V Temperature Coefficient:X5R")
      (fields
        (field (name "Manufacturer Part") "CGA0603X5R476M6R3JT")
        (field (name "Manufacturer") "HRE(芯声)")
      )
      (libsource (lib "easyedapro") (part "CGA0603X5R476M6R3JT"))
    )
    (comp (ref "C22")
      (value "47uF")
      (footprint "easyedapro:C0603")
      (description "Capacitance:47uF Tolerance:±20% Tolerance:±20% Voltage Rating:6.3V Temperature Coefficient:X5R")
      (fields
        (field (name "Manufacturer Part") "CGA0603X5R476M6R3JT")
        (field (name "Manufacturer") "HRE(芯声)")
      )
      (libsource (lib "easyedapro") (part "CGA0603X5R476M6R3JT"))
    )
    (comp (ref "C23")
      (value "47uF")
      (footprint "easyedapro:C0603")
      (description "Capacitance:47uF Tolerance:±20% Tolerance:±20% Voltage Rating:6.3V Temperature Coefficient:X5R")
      (fields
        (field (name "Manufacturer Part") "CGA0603X5R476M6R3JT")
        (field (name "Manufacturer") "HRE(芯声)")
      )
      (libsource (lib "easyedapro") (part "CGA0603X5R476M6R3JT"))
    )
    (comp (ref "C24")
      (value "47uF")
      (footprint "easyedapro:C0603")
      (description "Capacitance:47uF Tolerance:±20% Tolerance:±20% Voltage Rating:6.3V Temperature Coefficient:X5R")
      (fields
        (field (name "Manufacturer Part") "CGA0603X5R476M6R3JT")
        (field (name "Manufacturer") "HRE(芯声)")
      )
      (libsource (lib "easyedapro") (part "CGA0603X5R476M6R3JT"))
    )
    (comp (ref "C25")
      (value "47uF")
      (footprint "easyedapro:C0603")
      (description "Capacitance:47uF Tolerance:±20% Tolerance:±20% Voltage Rating:6.3V Temperature Coefficient:X5R")
      (fields
        (field (name "Manufacturer Part") "CGA0603X5R476M6R3JT")
        (field (name "Manufacturer") "HRE(芯声)")
      )
      (libsource (lib "easyedapro") (part "CGA0603X5R476M6R3JT"))
    )
    (comp (ref "C26")
      (value "47uF")
      (footprint "easyedapro:C0603")
      (description "Capacitance:47uF Tolerance:±20% Tolerance:±20% Voltage Rating:6.3V Temperature Coefficient:X5R")
      (fields
        (field (name "Manufacturer Part") "CGA0603X5R476M6R3JT")
        (field (name "Manufacturer") "HRE(芯声)")
      )
      (libsource (lib "easyedapro") (part "CGA0603X5R476M6R3JT"))
    )
    (comp (ref "C27")
      (value "47uF")
      (footprint "easyedapro:C0603")
      (description "Capacitance:47uF Tolerance:±20% Tolerance:±20% Voltage Rating:6.3V Temperature Coefficient:X5R")
      (fields
        (field (name "Manufacturer Part") "CGA0603X5R476M6R3JT")
        (field (name "Manufacturer") "HRE(芯声)")
      )
      (libsource (lib "easyedapro") (part "CGA0603X5R476M6R3JT"))
    )
    (comp (ref "CN11")
      (value "ZX-XH2.54-2PZZ")
      (footprint "easyedapro:CONN-TH_2P-P2.50_HX25003-2A")
      (fields (field (name "Manufacturer") "Megastar(兆星)"))
      (libsource (lib "easyedapro") (part "ZX-XH2.54-2PZZ"))
    )
    (comp (ref "CN12")
      (value "ZX-XH2.54-2PZZ")
      (footprint "easyedapro:CONN-TH_2P-P2.50_HX25003-2A")
      (fields (field (name "Manufacturer") "Megastar(兆星)"))
      (libsource (lib "easyedapro") (part "ZX-XH2.54-2PZZ"))
    )
    (comp (ref "CN13")
      (value "ZX-XH2.54-2PZZ")
      (footprint "easyedapro:CONN-TH_2P-P2.50_HX25003-2A")
      (fields (field (name "Manufacturer") "Megastar(兆星)"))
      (libsource (lib "easyedapro") (part "ZX-XH2.54-2PZZ"))
    )
    (comp (ref "CN14")
      (value "ZX-XH2.54-2PZZ")
      (footprint "easyedapro:CONN-TH_2P-P2.50_HX25003-2A")
      (fields (field (name "Manufacturer") "Megastar(兆星)"))
      (libsource (lib "easyedapro") (part "ZX-XH2.54-2PZZ"))
    )
    (comp (ref "CN15")
      (value "ZX-XH2.54-2PZZ")
      (footprint "easyedapro:CONN-TH_2P-P2.50_HX25003-2A")
      (fields (field (name "Manufacturer") "Megastar(兆星)"))
      (libsource (lib "easyedapro") (part "ZX-XH2.54-2PZZ"))
    )
    (comp (ref "CN16")
      (value "ZX-XH2.54-2PZZ")
      (footprint "easyedapro:CONN-TH_2P-P2.50_HX25003-2A")
      (fields (field (name "Manufacturer") "Megastar(兆星)"))
      (libsource (lib "easyedapro") (part "ZX-XH2.54-2PZZ"))
    )
    (comp (ref "CN17")
      (value "ZX-XH2.54-2PZZ")
      (footprint "easyedapro:CONN-TH_2P-P2.50_HX25003-2A")
      (fields (field (name "Manufacturer") "Megastar(兆星)"))
      (libsource (lib "easyedapro") (part "ZX-XH2.54-2PZZ"))
    )
    (comp (ref "CN18")
      (value "ZX-XH2.54-2PZZ")
      (footprint "easyedapro:CONN-TH_2P-P2.50_HX25003-2A")
      (fields (field (name "Manufacturer") "Megastar(兆星)"))
      (libsource (lib "easyedapro") (part "ZX-XH2.54-2PZZ"))
    )
    (comp (ref "CN19")
      (value "ZX-XH2.54-2PZZ")
      (footprint "easyedapro:CONN-TH_2P-P2.50_HX25003-2A")
      (fields (field (name "Manufacturer") "Megastar(兆星)"))
      (libsource (lib "easyedapro") (part "ZX-XH2.54-2PZZ"))
    )
    (comp (ref "CN20")
      (value "ZX-XH2.54-2PZZ")
      (footprint "easyedapro:CONN-TH_2P-P2.50_HX25003-2A")
      (fields (field (name "Manufacturer") "Megastar(兆星)"))
      (libsource (lib "easyedapro") (part "ZX-XH2.54-2PZZ"))
    )
    (comp (ref "CN21")
      (value "ZX-XH2.54-2PZZ")
      (footprint "easyedapro:CONN-TH_2P-P2.50_HX25003-2A")
      (fields (field (name "Manufacturer") "Megastar(兆星)"))
      (libsource (lib "easyedapro") (part "ZX-XH2.54-2PZZ"))
    )
    (comp (ref "CN22")
      (value "ZX-XH2.54-2PZZ")
      (footprint "easyedapro:CONN-TH_2P-P2.50_HX25003-2A")
      (fields (field (name "Manufacturer") "Megastar(兆星)"))
      (libsource (lib "easyedapro") (part "ZX-XH2.54-2PZZ"))
    )
    (comp (ref "LED23")
      (value "XL-1608SURC-06")
      (footprint "easyedapro:LED0603-RD_RED")
      (fields (field (name "Manufacturer") "XINGLIGHT(成兴光)"))
      (libsource (lib "easyedapro") (part "XL-1608SURC-06"))
    )
    (comp (ref "LED24")
      (value "XL-1608SURC-06")
      (footprint "easyedapro:LED0603-RD_RED")
      (fields (field (name "Manufacturer") "XINGLIGHT(成兴光)"))
      (libsource (lib "easyedapro") (part "XL-1608SURC-06"))
    )
    (comp (ref "LED25")
      (value "XL-1608SURC-06")
      (footprint "easyedapro:LED0603-RD_RED")
      (fields (field (name "Manufacturer") "XINGLIGHT(成兴光)"))
      (libsource (lib "easyedapro") (part "XL-1608SURC-06"))
    )
    (comp (ref "LED26")
      (value "XL-1608SURC-06")
      (footprint "easyedapro:LED0603-RD_RED")
      (fields (field (name "Manufacturer") "XINGLIGHT(成兴光)"))
      (libsource (lib "easyedapro") (part "XL-1608SURC-06"))
    )
    (comp (ref "LED27")
      (value "XL-1608SURC-06")
      (footprint "easyedapro:LED0603-RD_RED")
      (fields (field (name "Manufacturer") "XINGLIGHT(成兴光)"))
      (libsource (lib "easyedapro") (part "XL-1608SURC-06"))
    )
    (comp (ref "LED28")
      (value "XL-1608SURC-06")
      (footprint "easyedapro:LED0603-RD_RED")
      (fields (field (name "Manufacturer") "XINGLIGHT(成兴光)"))
      (libsource (lib "easyedapro") (part "XL-1608SURC-06"))
    )
    (comp (ref "LED29")
      (value "XL-1608SURC-06")
      (footprint "easyedapro:LED0603-RD_RED")
      (fields (field (name "Manufacturer") "XINGLIGHT(成兴光)"))
      (libsource (lib "easyedapro") (part "XL-1608SURC-06"))
    )
    (comp (ref "LED30")
      (value "XL-1608SURC-06")
      (footprint "easyedapro:LED0603-RD_RED")
      (fields (field (name "Manufacturer") "XINGLIGHT(成兴光)"))
      (libsource (lib "easyedapro") (part "XL-1608SURC-06"))
    )
    (comp (ref "LED31")
      (value "XL-1608SURC-06")
      (footprint "easyedapro:LED0603-RD_RED")
      (fields (field (name "Manufacturer") "XINGLIGHT(成兴光)"))
      (libsource (lib "easyedapro") (part "XL-1608SURC-06"))
    )
    (comp (ref "LED32")
      (value "XL-1608SURC-06")
      (footprint "easyedapro:LED0603-RD_RED")
      (fields (field (name "Manufacturer") "XINGLIGHT(成兴光)"))
      (libsource (lib "easyedapro") (part "XL-1608SURC-06"))
    )
    (comp (ref "LED33")
      (value "XL-1608SURC-06")
      (footprint "easyedapro:LED0603-RD_RED")
      (fields (field (name "Manufacturer") "XINGLIGHT(成兴光)"))
      (libsource (lib "easyedapro") (part "XL-1608SURC-06"))
    )
    (comp (ref "LED34")
      (value "XL-1608SURC-06")
      (footprint "easyedapro:LED0603-RD_RED")
      (fields (field (name "Manufacturer") "XINGLIGHT(成兴光)"))
      (libsource (lib "easyedapro") (part "XL-1608SURC-06"))
    )
    (comp (ref "LED35")
      (value "XL-1608SURC-06")
      (footprint "easyedapro:LED0603-RD_RED")
      (fields (field (name "Manufacturer") "XINGLIGHT(成兴光)"))
      (libsource (lib "easyedapro") (part "XL-1608SURC-06"))
    )
    (comp (ref "LED36")
      (value "XL-1608SURC-06")
      (footprint "easyedapro:LED0603-RD_RED")
      (fields (field (name "Manufacturer") "XINGLIGHT(成兴光)"))
      (libsource (lib "easyedapro") (part "XL-1608SURC-06"))
    )
    (comp (ref "LED37")
      (value "XL-1608SURC-06")
      (footprint "easyedapro:LED0603-RD_RED")
      (fields (field (name "Manufacturer") "XINGLIGHT(成兴光)"))
      (libsource (lib "easyedapro") (part "XL-1608SURC-06"))
    )
    (comp (ref "LED38")
      (value "XL-1608SURC-06")
      (footprint "easyedapro:LED0603-RD_RED")
      (fields (field (name "Manufacturer") "XINGLIGHT(成兴光)"))
      (libsource (lib "easyedapro") (part "XL-1608SURC-06"))
    )
    (comp (ref "LED39")
      (value "XL-1608SURC-06")
      (footprint "easyedapro:LED0603-RD_RED")
      (fields (field (name "Manufacturer") "XINGLIGHT(成兴光)"))
      (libsource (lib "easyedapro") (part "XL-1608SURC-06"))
    )
    (comp (ref "LED40")
      (value "XL-1608SURC-06")
      (footprint "easyedapro:LED0603-RD_RED")
      (fields (field (name "Manufacturer") "XINGLIGHT(成兴光)"))
      (libsource (lib "easyedapro") (part "XL-1608SURC-06"))
    )
    (comp (ref "LED41")
      (value "XL-1608SURC-06")
      (footprint "easyedapro:LED0603-RD_RED")
      (fields (field (name "Manufacturer") "XINGLIGHT(成兴光)"))
      (libsource (lib "easyedapro") (part "XL-1608SURC-06"))
    )
    (comp (ref "LED42")
      (value "XL-1608SURC-06")
      (footprint "easyedapro:LED0603-RD_RED")
      (fields (field (name "Manufacturer") "XINGLIGHT(成兴光)"))
      (libsource (lib "easyedapro") (part "XL-1608SURC-06"))
    )
    (comp (ref "LED43")
      (value "XL-1608SURC-06")
      (footprint "easyedapro:LED0603-RD_RED")
      (fields (field (name "Manufacturer") "XINGLIGHT(成兴光)"))
      (libsource (lib "easyedapro") (part "XL-1608SURC-06"))
    )
    (comp (ref "LED44")
      (value "XL-1608SURC-06")
      (footprint "easyedapro:LED0603-RD_RED")
      (fields (field (name "Manufacturer") "XINGLIGHT(成兴光)"))
      (libsource (lib "easyedapro") (part "XL-1608SURC-06"))
    )
    (comp (ref "LED45")
      (value "XL-1608SURC-06")
      (footprint "easyedapro:LED0603-RD_RED")
      (fields (field (name "Manufacturer") "XINGLIGHT(成兴光)"))
      (libsource (lib "easyedapro") (part "XL-1608SURC-06"))
    )
    (comp (ref "LED46")
      (value "XL-1608SURC-06")
      (footprint "easyedapro:LED0603-RD_RED")
      (fields (field (name "Manufacturer") "XINGLIGHT(成兴光)"))
      (libsource (lib "easyedapro") (part "XL-1608SURC-06"))
    )
    (comp (ref "R37")
      (value "4.7kΩ")
      (footprint "easyedapro:R0603")
      (fields
        (field (name "Manufacturer Part") "0603WAF4701T5E")
        (field (name "Manufacturer") "UNI-ROYAL(厚声)")
      )
      (libsource (lib "easyedapro") (part "0603WAF4701T5E"))
    )
    (comp (ref "R38")
      (value "1kΩ")
      (footprint "easyedapro:R0603")
      (fields
        (field (name "Manufacturer Part") "0603WAF1001T5E")
        (field (name "Manufacturer") "UNI-ROYAL(厚声)")
      )
      (libsource (lib "easyedapro") (part "0603WAF1001T5E"))
    )
    (comp (ref "R39")
      (value "4.7kΩ")
      (footprint "easyedapro:R0603")
      (fields
        (field (name "Manufacturer Part") "0603WAF4701T5E")
        (field (name "Manufacturer") "UNI-ROYAL(厚声)")
      )
      (libsource (lib "easyedapro") (part "0603WAF4701T5E"))
    )
    (comp (ref "R40")
      (value "1kΩ")
      (footprint "easyedapro:R0603")
      (fields
        (field (name "Manufacturer Part") "0603WAF1001T5E")
        (field (name "Manufacturer") "UNI-ROYAL(厚声)")
      )
      (libsource (lib "easyedapro") (part "0603WAF1001T5E"))
    )
    (comp (ref "R41")
      (value "4.7kΩ")
      (footprint "easyedapro:R0603")
      (fields
        (field (name "Manufacturer Part") "0603WAF4701T5E")
        (field (name "Manufacturer") "UNI-ROYAL(厚声)")
      )
      (libsource (lib "easyedapro") (part "0603WAF4701T5E"))
    )
    (comp (ref "R42")
      (value "1kΩ")
      (footprint "easyedapro:R0603")
      (fields
        (field (name "Manufacturer Part") "0603WAF1001T5E")
        (field (name "Manufacturer") "UNI-ROYAL(厚声)")
      )
      (libsource (lib "easyedapro") (part "0603WAF1001T5E"))
    )
    (comp (ref "R43")
      (value "4.7kΩ")
      (footprint "easyedapro:R0603")
      (fields
        (field (name "Manufacturer Part") "0603WAF4701T5E")
        (field (name "Manufacturer") "UNI-ROYAL(厚声)")
      )
      (libsource (lib "easyedapro") (part "0603WAF4701T5E"))
    )
    (comp (ref "R44")
      (value "1kΩ")
      (footprint "easyedapro:R0603")
      (fields
        (field (name "Manufacturer Part") "0603WAF1001T5E")
        (field (name "Manufacturer") "UNI-ROYAL(厚声)")
      )
      (libsource (lib "easyedapro") (part "0603WAF1001T5E"))
    )
    (comp (ref "R45")
      (value "4.7kΩ")
      (footprint "easyedapro:R0603")
      (fields
        (field (name "Manufacturer Part") "0603WAF4701T5E")
        (field (name "Manufacturer") "UNI-ROYAL(厚声)")
      )
      (libsource (lib "easyedapro") (part "0603WAF4701T5E"))
    )
    (comp (ref "R46")
      (value "1kΩ")
      (footprint "easyedapro:R0603")
      (fields
        (field (name "Manufacturer Part") "0603WAF1001T5E")
        (field (name "Manufacturer") "UNI-ROYAL(厚声)")
      )
      (libsource (lib "easyedapro") (part "0603WAF1001T5E"))
    )
    (comp (ref "R47")
      (value "4.7kΩ")
      (footprint "easyedapro:R0603")
      (fields
        (field (name "Manufacturer Part") "0603WAF4701T5E")
        (field (name "Manufacturer") "UNI-ROYAL(厚声)")
      )
      (libsource (lib "easyedapro") (part "0603WAF4701T5E"))
    )
    (comp (ref "R48")
      (value "1kΩ")
      (footprint "easyedapro:R0603")
      (fields
        (field (name "Manufacturer Part") "0603WAF1001T5E")
        (field (name "Manufacturer") "UNI-ROYAL(厚声)")
      )
      (libsource (lib "easyedapro") (part "0603WAF1001T5E"))
    )
    (comp (ref "R49")
      (value "4.7kΩ")
      (footprint "easyedapro:R0603")
      (fields
        (field (name "Manufacturer Part") "0603WAF4701T5E")
        (field (name "Manufacturer") "UNI-ROYAL(厚声)")
      )
      (libsource (lib "easyedapro") (part "0603WAF4701T5E"))
    )
    (comp (ref "R50")
      (value "1kΩ")
      (footprint "easyedapro:R0603")
      (fields
        (field (name "Manufacturer Part") "0603WAF1001T5E")
        (field (name "Manufacturer") "UNI-ROYAL(厚声)")
      )
      (libsource (lib "easyedapro") (part "0603WAF1001T5E"))
    )
    (comp (ref "R51")
      (value "4.7kΩ")
      (footprint "easyedapro:R0603")
      (fields
        (field (name "Manufacturer Part") "0603WAF4701T5E")
        (field (name "Manufacturer") "UNI-ROYAL(厚声)")
      )
      (libsource (lib "easyedapro") (part "0603WAF4701T5E"))
    )
    (comp (ref "R52")
      (value "1kΩ")
      (footprint "easyedapro:R0603")
      (fields
        (field (name "Manufacturer Part") "0603WAF1001T5E")
        (field (name "Manufacturer") "UNI-ROYAL(厚声)")
      )
      (libsource (lib "easyedapro") (part "0603WAF1001T5E"))
    )
    (comp (ref "R53")
      (value "4.7kΩ")
      (footprint "easyedapro:R0603")
      (fields
        (field (name "Manufacturer Part") "0603WAF4701T5E")
        (field (name "Manufacturer") "UNI-ROYAL(厚声)")
      )
      (libsource (lib "easyedapro") (part "0603WAF4701T5E"))
    )
    (comp (ref "R54")
      (value "1kΩ")
      (footprint "easyedapro:R0603")
      (fields
        (field (name "Manufacturer Part") "0603WAF1001T5E")
        (field (name "Manufacturer") "UNI-ROYAL(厚声)")
      )
      (libsource (lib "easyedapro") (part "0603WAF1001T5E"))
    )
    (comp (ref "R55")
      (value "4.7kΩ")
      (footprint "easyedapro:R0603")
      (fields
        (field (name "Manufacturer Part") "0603WAF4701T5E")
        (field (name "Manufacturer") "UNI-ROYAL(厚声)")
      )
      (libsource (lib "easyedapro") (part "0603WAF4701T5E"))
    )
    (comp (ref "R56")
      (value "1kΩ")
      (footprint "easyedapro:R0603")
      (fields
        (field (name "Manufacturer Part") "0603WAF1001T5E")
        (field (name "Manufacturer") "UNI-ROYAL(厚声)")
      )
      (libsource (lib "easyedapro") (part "0603WAF1001T5E"))
    )
    (comp (ref "R57")
      (value "4.7kΩ")
      (footprint "easyedapro:R0603")
      (fields
        (field (name "Manufacturer Part") "0603WAF4701T5E")
        (field (name "Manufacturer") "UNI-ROYAL(厚声)")
      )
      (libsource (lib "easyedapro") (part "0603WAF4701T5E"))
    )
    (comp (ref "R58")
      (value "1kΩ")
      (footprint "easyedapro:R0603")
      (fields
        (field (name "Manufacturer Part") "0603WAF1001T5E")
        (field (name "Manufacturer") "UNI-ROYAL(厚声)")
      )
      (libsource (lib "easyedapro") (part "0603WAF1001T5E"))
    )
    (comp (ref "R59")
      (value "4.7kΩ")
      (footprint "easyedapro:R0603")
      (fields
        (field (name "Manufacturer Part") "0603WAF4701T5E")
        (field (name "Manufacturer") "UNI-ROYAL(厚声)")
      )
      (libsource (lib "easyedapro") (part "0603WAF4701T5E"))
    )
    (comp (ref "R60")
      (value "1kΩ")
      (footprint "easyedapro:R0603")
      (fields
        (field (name "Manufacturer Part") "0603WAF1001T5E")
        (field (name "Manufacturer") "UNI-ROYAL(厚声)")
      )
      (libsource (lib "easyedapro") (part "0603WAF1001T5E"))
    )
    (comp (ref "R81")
      (value "1kΩ")
      (footprint "easyedapro:R0603")
      (fields
        (field (name "Manufacturer Part") "0603WAF1001T5E")
        (field (name "Manufacturer") "UNI-ROYAL(厚声)")
      )
      (libsource (lib "easyedapro") (part "0603WAF1001T5E"))
    )
    (comp (ref "R82")
      (value "1kΩ")
      (footprint "easyedapro:R0603")
      (fields
        (field (name "Manufacturer Part") "0603WAF1001T5E")
        (field (name "Manufacturer") "UNI-ROYAL(厚声)")
      )
      (libsource (lib "easyedapro") (part "0603WAF1001T5E"))
    )
    (comp (ref "R84")
      (value "1kΩ")
      (footprint "easyedapro:R0603")
      (fields
        (field (name "Manufacturer Part") "0603WAF1001T5E")
        (field (name "Manufacturer") "UNI-ROYAL(厚声)")
      )
      (libsource (lib "easyedapro") (part "0603WAF1001T5E"))
    )
    (comp (ref "R85")
      (value "1kΩ")
      (footprint "easyedapro:R0603")
      (fields
        (field (name "Manufacturer Part") "0603WAF1001T5E")
        (field (name "Manufacturer") "UNI-ROYAL(厚声)")
      )
      (libsource (lib "easyedapro") (part "0603WAF1001T5E"))
    )
    (comp (ref "R86")
      (value "1kΩ")
      (footprint "easyedapro:R0603")
      (fields
        (field (name "Manufacturer Part") "0603WAF1001T5E")
        (field (name "Manufacturer") "UNI-ROYAL(厚声)")
      )
      (libsource (lib "easyedapro") (part "0603WAF1001T5E"))
    )
    (comp (ref "R87")
      (value "1kΩ")
      (footprint "easyedapro:R0603")
      (fields
        (field (name "Manufacturer Part") "0603WAF1001T5E")
        (field (name "Manufacturer") "UNI-ROYAL(厚声)")
      )
      (libsource (lib "easyedapro") (part "0603WAF1001T5E"))
    )
    (comp (ref "R88")
      (value "1kΩ")
      (footprint "easyedapro:R0603")
      (fields
        (field (name "Manufacturer Part") "0603WAF1001T5E")
        (field (name "Manufacturer") "UNI-ROYAL(厚声)")
      )
      (libsource (lib "easyedapro") (part "0603WAF1001T5E"))
    )
    (comp (ref "R89")
      (value "1kΩ")
      (footprint "easyedapro:R0603")
      (fields
        (field (name "Manufacturer Part") "0603WAF1001T5E")
        (field (name "Manufacturer") "UNI-ROYAL(厚声)")
      )
      (libsource (lib "easyedapro") (part "0603WAF1001T5E"))
    )
    (comp (ref "R90")
      (value "1kΩ")
      (footprint "easyedapro:R0603")
      (fields
        (field (name "Manufacturer Part") "0603WAF1001T5E")
        (field (name "Manufacturer") "UNI-ROYAL(厚声)")
      )
      (libsource (lib "easyedapro") (part "0603WAF1001T5E"))
    )
    (comp (ref "R91")
      (value "1kΩ")
      (footprint "easyedapro:R0603")
      (fields
        (field (name "Manufacturer Part") "0603WAF1001T5E")
        (field (name "Manufacturer") "UNI-ROYAL(厚声)")
      )
      (libsource (lib "easyedapro") (part "0603WAF1001T5E"))
    )
    (comp (ref "R92")
      (value "1kΩ")
      (footprint "easyedapro:R0603")
      (fields
        (field (name "Manufacturer Part") "0603WAF1001T5E")
        (field (name "Manufacturer") "UNI-ROYAL(厚声)")
      )
      (libsource (lib "easyedapro") (part "0603WAF1001T5E"))
    )
    (comp (ref "R93")
      (value "1kΩ")
      (footprint "easyedapro:R0603")
      (fields
        (field (name "Manufacturer Part") "0603WAF1001T5E")
        (field (name "Manufacturer") "UNI-ROYAL(厚声)")
      )
      (libsource (lib "easyedapro") (part "0603WAF1001T5E"))
    )
    (comp (ref "SW7")
      (value "TS-1088-AR02016")
      (footprint "easyedapro:SW-SMD_L3.9-W3.0-P4.45")
      (fields (field (name "Manufacturer") "XUNPU(讯普)"))
      (libsource (lib "easyedapro") (part "TS-1088-AR02016"))
    )
    (comp (ref "SW8")
      (value "TS-1088-AR02016")
      (footprint "easyedapro:SW-SMD_L3.9-W3.0-P4.45")
      (fields (field (name "Manufacturer") "XUNPU(讯普)"))
      (libsource (lib "easyedapro") (part "TS-1088-AR02016"))
    )
    (comp (ref "SW9")
      (value "TS-1088-AR02016")
      (footprint "easyedapro:SW-SMD_L3.9-W3.0-P4.45")
      (fields (field (name "Manufacturer") "XUNPU(讯普)"))
      (libsource (lib "easyedapro") (part "TS-1088-AR02016"))
    )
    (comp (ref "SW10")
      (value "TS-1088-AR02016")
      (footprint "easyedapro:SW-SMD_L3.9-W3.0-P4.45")
      (fields (field (name "Manufacturer") "XUNPU(讯普)"))
      (libsource (lib "easyedapro") (part "TS-1088-AR02016"))
    )
    (comp (ref "SW11")
      (value "TS-1088-AR02016")
      (footprint "easyedapro:SW-SMD_L3.9-W3.0-P4.45")
      (fields (field (name "Manufacturer") "XUNPU(讯普)"))
      (libsource (lib "easyedapro") (part "TS-1088-AR02016"))
    )
    (comp (ref "SW12")
      (value "TS-1088-AR02016")
      (footprint "easyedapro:SW-SMD_L3.9-W3.0-P4.45")
      (fields (field (name "Manufacturer") "XUNPU(讯普)"))
      (libsource (lib "easyedapro") (part "TS-1088-AR02016"))
    )
    (comp (ref "SW13")
      (value "TS-1088-AR02016")
      (footprint "easyedapro:SW-SMD_L3.9-W3.0-P4.45")
      (fields (field (name "Manufacturer") "XUNPU(讯普)"))
      (libsource (lib "easyedapro") (part "TS-1088-AR02016"))
    )
    (comp (ref "SW14")
      (value "TS-1088-AR02016")
      (footprint "easyedapro:SW-SMD_L3.9-W3.0-P4.45")
      (fields (field (name "Manufacturer") "XUNPU(讯普)"))
      (libsource (lib "easyedapro") (part "TS-1088-AR02016"))
    )
    (comp (ref "SW15")
      (value "TS-1088-AR02016")
      (footprint "easyedapro:SW-SMD_L3.9-W3.0-P4.45")
      (fields (field (name "Manufacturer") "XUNPU(讯普)"))
      (libsource (lib "easyedapro") (part "TS-1088-AR02016"))
    )
    (comp (ref "SW16")
      (value "TS-1088-AR02016")
      (footprint "easyedapro:SW-SMD_L3.9-W3.0-P4.45")
      (fields (field (name "Manufacturer") "XUNPU(讯普)"))
      (libsource (lib "easyedapro") (part "TS-1088-AR02016"))
    )
    (comp (ref "SW17")
      (value "TS-1088-AR02016")
      (footprint "easyedapro:SW-SMD_L3.9-W3.0-P4.45")
      (fields (field (name "Manufacturer") "XUNPU(讯普)"))
      (libsource (lib "easyedapro") (part "TS-1088-AR02016"))
    )
    (comp (ref "SW18")
      (value "TS-1088-AR02016")
      (footprint "easyedapro:SW-SMD_L3.9-W3.0-P4.45")
      (fields (field (name "Manufacturer") "XUNPU(讯普)"))
      (libsource (lib "easyedapro") (part "TS-1088-AR02016"))
    )
    (comp (ref "U19")
      (value "TPS1H200AQDGNRQ1")
      (footprint "easyedapro:EMSOP-8_L3.0-W3.0-P0.65-LS4.9-BL-EP-A")
      (fields (field (name "Manufacturer") "TI(德州仪器)"))
      (libsource (lib "easyedapro") (part "TPS1H200AQDGNRQ1"))
    )
    (comp (ref "U20")
      (value "TPS1H200AQDGNRQ1")
      (footprint "easyedapro:EMSOP-8_L3.0-W3.0-P0.65-LS4.9-BL-EP-A")
      (fields (field (name "Manufacturer") "TI(德州仪器)"))
      (libsource (lib "easyedapro") (part "TPS1H200AQDGNRQ1"))
    )
    (comp (ref "U21")
      (value "TPS1H200AQDGNRQ1")
      (footprint "easyedapro:EMSOP-8_L3.0-W3.0-P0.65-LS4.9-BL-EP-A")
      (fields (field (name "Manufacturer") "TI(德州仪器)"))
      (libsource (lib "easyedapro") (part "TPS1H200AQDGNRQ1"))
    )
    (comp (ref "U22")
      (value "TPS1H200AQDGNRQ1")
      (footprint "easyedapro:EMSOP-8_L3.0-W3.0-P0.65-LS4.9-BL-EP-A")
      (fields (field (name "Manufacturer") "TI(德州仪器)"))
      (libsource (lib "easyedapro") (part "TPS1H200AQDGNRQ1"))
    )
    (comp (ref "U23")
      (value "TPS1H200AQDGNRQ1")
      (footprint "easyedapro:EMSOP-8_L3.0-W3.0-P0.65-LS4.9-BL-EP-A")
      (fields (field (name "Manufacturer") "TI(德州仪器)"))
      (libsource (lib "easyedapro") (part "TPS1H200AQDGNRQ1"))
    )
    (comp (ref "U24")
      (value "TPS1H200AQDGNRQ1")
      (footprint "easyedapro:EMSOP-8_L3.0-W3.0-P0.65-LS4.9-BL-EP-A")
      (fields (field (name "Manufacturer") "TI(德州仪器)"))
      (libsource (lib "easyedapro") (part "TPS1H200AQDGNRQ1"))
    )
    (comp (ref "U25")
      (value "TPS1H200AQDGNRQ1")
      (footprint "easyedapro:EMSOP-8_L3.0-W3.0-P0.65-LS4.9-BL-EP-A")
      (fields (field (name "Manufacturer") "TI(德州仪器)"))
      (libsource (lib "easyedapro") (part "TPS1H200AQDGNRQ1"))
    )
    (comp (ref "U26")
      (value "TPS1H200AQDGNRQ1")
      (footprint "easyedapro:EMSOP-8_L3.0-W3.0-P0.65-LS4.9-BL-EP-A")
      (fields (field (name "Manufacturer") "TI(德州仪器)"))
      (libsource (lib "easyedapro") (part "TPS1H200AQDGNRQ1"))
    )
    (comp (ref "U27")
      (value "TPS1H200AQDGNRQ1")
      (footprint "easyedapro:EMSOP-8_L3.0-W3.0-P0.65-LS4.9-BL-EP-A")
      (fields (field (name "Manufacturer") "TI(德州仪器)"))
      (libsource (lib "easyedapro") (part "TPS1H200AQDGNRQ1"))
    )
    (comp (ref "U28")
      (value "TPS1H200AQDGNRQ1")
      (footprint "easyedapro:EMSOP-8_L3.0-W3.0-P0.65-LS4.9-BL-EP-A")
      (fields (field (name "Manufacturer") "TI(德州仪器)"))
      (libsource (lib "easyedapro") (part "TPS1H200AQDGNRQ1"))
    )
    (comp (ref "U29")
      (value "TPS1H200AQDGNRQ1")
      (footprint "easyedapro:EMSOP-8_L3.0-W3.0-P0.65-LS4.9-BL-EP-A")
      (fields (field (name "Manufacturer") "TI(德州仪器)"))
      (libsource (lib "easyedapro") (part "TPS1H200AQDGNRQ1"))
    )
    (comp (ref "U30")
      (value "TPS1H200AQDGNRQ1")
      (footprint "easyedapro:EMSOP-8_L3.0-W3.0-P0.65-LS4.9-BL-EP-A")
      (fields (field (name "Manufacturer") "TI(德州仪器)"))
      (libsource (lib "easyedapro") (part "TPS1H200AQDGNRQ1"))
    )
    (comp (ref "C28")
      (value "47uF")
      (footprint "easyedapro:C0603")
      (description "Capacitance:47uF Tolerance:±20% Tolerance:±20% Voltage Rating:6.3V Temperature Coefficient:X5R")
      (fields
        (field (name "Manufacturer Part") "CGA0603X5R476M6R3JT")
        (field (name "Manufacturer") "HRE(芯声)")
      )
      (libsource (lib "easyedapro") (part "CGA0603X5R476M6R3JT"))
    )
    (comp (ref "C29")
      (value "47uF")
      (footprint "easyedapro:C0603")
      (description "Capacitance:47uF Tolerance:±20% Tolerance:±20% Voltage Rating:6.3V Temperature Coefficient:X5R")
      (fields
        (field (name "Manufacturer Part") "CGA0603X5R476M6R3JT")
        (field (name "Manufacturer") "HRE(芯声)")
      )
      (libsource (lib "easyedapro") (part "CGA0603X5R476M6R3JT"))
    )
    (comp (ref "C30")
      (value "47uF")
      (footprint "easyedapro:C0603")
      (description "Capacitance:47uF Tolerance:±20% Tolerance:±20% Voltage Rating:6.3V Temperature Coefficient:X5R")
      (fields
        (field (name "Manufacturer Part") "CGA0603X5R476M6R3JT")
        (field (name "Manufacturer") "HRE(芯声)")
      )
      (libsource (lib "easyedapro") (part "CGA0603X5R476M6R3JT"))
    )
    (comp (ref "C31")
      (value "47uF")
      (footprint "easyedapro:C0603")
      (description "Capacitance:47uF Tolerance:±20% Tolerance:±20% Voltage Rating:6.3V Temperature Coefficient:X5R")
      (fields
        (field (name "Manufacturer Part") "CGA0603X5R476M6R3JT")
        (field (name "Manufacturer") "HRE(芯声)")
      )
      (libsource (lib "easyedapro") (part "CGA0603X5R476M6R3JT"))
    )
    (comp (ref "C32")
      (value "47uF")
      (footprint "easyedapro:C0603")
      (description "Capacitance:47uF Tolerance:±20% Tolerance:±20% Voltage Rating:6.3V Temperature Coefficient:X5R")
      (fields
        (field (name "Manufacturer Part") "CGA0603X5R476M6R3JT")
        (field (name "Manufacturer") "HRE(芯声)")
      )
      (libsource (lib "easyedapro") (part "CGA0603X5R476M6R3JT"))
    )
    (comp (ref "C33")
      (value "47uF")
      (footprint "easyedapro:C0603")
      (description "Capacitance:47uF Tolerance:±20% Tolerance:±20% Voltage Rating:6.3V Temperature Coefficient:X5R")
      (fields
        (field (name "Manufacturer Part") "CGA0603X5R476M6R3JT")
        (field (name "Manufacturer") "HRE(芯声)")
      )
      (libsource (lib "easyedapro") (part "CGA0603X5R476M6R3JT"))
    )
    (comp (ref "C34")
      (value "47uF")
      (footprint "easyedapro:C0603")
      (description "Capacitance:47uF Tolerance:±20% Tolerance:±20% Voltage Rating:6.3V Temperature Coefficient:X5R")
      (fields
        (field (name "Manufacturer Part") "CGA0603X5R476M6R3JT")
        (field (name "Manufacturer") "HRE(芯声)")
      )
      (libsource (lib "easyedapro") (part "CGA0603X5R476M6R3JT"))
    )
    (comp (ref "C35")
      (value "47uF")
      (footprint "easyedapro:C0603")
      (description "Capacitance:47uF Tolerance:±20% Tolerance:±20% Voltage Rating:6.3V Temperature Coefficient:X5R")
      (fields
        (field (name "Manufacturer Part") "CGA0603X5R476M6R3JT")
        (field (name "Manufacturer") "HRE(芯声)")
      )
      (libsource (lib "easyedapro") (part "CGA0603X5R476M6R3JT"))
    )
    (comp (ref "CN23")
      (value "ZX-XH2.54-2PZZ")
      (footprint "easyedapro:CONN-TH_2P-P2.50_HX25003-2A")
      (fields (field (name "Manufacturer") "Megastar(兆星)"))
      (libsource (lib "easyedapro") (part "ZX-XH2.54-2PZZ"))
    )
    (comp (ref "CN24")
      (value "ZX-XH2.54-2PZZ")
      (footprint "easyedapro:CONN-TH_2P-P2.50_HX25003-2A")
      (fields (field (name "Manufacturer") "Megastar(兆星)"))
      (libsource (lib "easyedapro") (part "ZX-XH2.54-2PZZ"))
    )
    (comp (ref "CN25")
      (value "ZX-XH2.54-2PZZ")
      (footprint "easyedapro:CONN-TH_2P-P2.50_HX25003-2A")
      (fields (field (name "Manufacturer") "Megastar(兆星)"))
      (libsource (lib "easyedapro") (part "ZX-XH2.54-2PZZ"))
    )
    (comp (ref "CN26")
      (value "ZX-XH2.54-2PZZ")
      (footprint "easyedapro:CONN-TH_2P-P2.50_HX25003-2A")
      (fields (field (name "Manufacturer") "Megastar(兆星)"))
      (libsource (lib "easyedapro") (part "ZX-XH2.54-2PZZ"))
    )
    (comp (ref "CN27")
      (value "ZX-XH2.54-2PZZ")
      (footprint "easyedapro:CONN-TH_2P-P2.50_HX25003-2A")
      (fields (field (name "Manufacturer") "Megastar(兆星)"))
      (libsource (lib "easyedapro") (part "ZX-XH2.54-2PZZ"))
    )
    (comp (ref "CN28")
      (value "ZX-XH2.54-2PZZ")
      (footprint "easyedapro:CONN-TH_2P-P2.50_HX25003-2A")
      (fields (field (name "Manufacturer") "Megastar(兆星)"))
      (libsource (lib "easyedapro") (part "ZX-XH2.54-2PZZ"))
    )
    (comp (ref "CN29")
      (value "ZX-XH2.54-2PZZ")
      (footprint "easyedapro:CONN-TH_2P-P2.50_HX25003-2A")
      (fields (field (name "Manufacturer") "Megastar(兆星)"))
      (libsource (lib "easyedapro") (part "ZX-XH2.54-2PZZ"))
    )
    (comp (ref "CN30")
      (value "ZX-XH2.54-2PZZ")
      (footprint "easyedapro:CONN-TH_2P-P2.50_HX25003-2A")
      (fields (field (name "Manufacturer") "Megastar(兆星)"))
      (libsource (lib "easyedapro") (part "ZX-XH2.54-2PZZ"))
    )
    (comp (ref "LED47")
      (value "XL-1608SURC-06")
      (footprint "easyedapro:LED0603-RD_RED")
      (fields (field (name "Manufacturer") "XINGLIGHT(成兴光)"))
      (libsource (lib "easyedapro") (part "XL-1608SURC-06"))
    )
    (comp (ref "LED48")
      (value "XL-1608SURC-06")
      (footprint "easyedapro:LED0603-RD_RED")
      (fields (field (name "Manufacturer") "XINGLIGHT(成兴光)"))
      (libsource (lib "easyedapro") (part "XL-1608SURC-06"))
    )
    (comp (ref "LED49")
      (value "XL-1608SURC-06")
      (footprint "easyedapro:LED0603-RD_RED")
      (fields (field (name "Manufacturer") "XINGLIGHT(成兴光)"))
      (libsource (lib "easyedapro") (part "XL-1608SURC-06"))
    )
    (comp (ref "LED50")
      (value "XL-1608SURC-06")
      (footprint "easyedapro:LED0603-RD_RED")
      (fields (field (name "Manufacturer") "XINGLIGHT(成兴光)"))
      (libsource (lib "easyedapro") (part "XL-1608SURC-06"))
    )
    (comp (ref "LED51")
      (value "XL-1608SURC-06")
      (footprint "easyedapro:LED0603-RD_RED")
      (fields (field (name "Manufacturer") "XINGLIGHT(成兴光)"))
      (libsource (lib "easyedapro") (part "XL-1608SURC-06"))
    )
    (comp (ref "LED52")
      (value "XL-1608SURC-06")
      (footprint "easyedapro:LED0603-RD_RED")
      (fields (field (name "Manufacturer") "XINGLIGHT(成兴光)"))
      (libsource (lib "easyedapro") (part "XL-1608SURC-06"))
    )
    (comp (ref "LED53")
      (value "XL-1608SURC-06")
      (footprint "easyedapro:LED0603-RD_RED")
      (fields (field (name "Manufacturer") "XINGLIGHT(成兴光)"))
      (libsource (lib "easyedapro") (part "XL-1608SURC-06"))
    )
    (comp (ref "LED54")
      (value "XL-1608SURC-06")
      (footprint "easyedapro:LED0603-RD_RED")
      (fields (field (name "Manufacturer") "XINGLIGHT(成兴光)"))
      (libsource (lib "easyedapro") (part "XL-1608SURC-06"))
    )
    (comp (ref "LED55")
      (value "XL-1608SURC-06")
      (footprint "easyedapro:LED0603-RD_RED")
      (fields (field (name "Manufacturer") "XINGLIGHT(成兴光)"))
      (libsource (lib "easyedapro") (part "XL-1608SURC-06"))
    )
    (comp (ref "LED56")
      (value "XL-1608SURC-06")
      (footprint "easyedapro:LED0603-RD_RED")
      (fields (field (name "Manufacturer") "XINGLIGHT(成兴光)"))
      (libsource (lib "easyedapro") (part "XL-1608SURC-06"))
    )
    (comp (ref "LED57")
      (value "XL-1608SURC-06")
      (footprint "easyedapro:LED0603-RD_RED")
      (fields (field (name "Manufacturer") "XINGLIGHT(成兴光)"))
      (libsource (lib "easyedapro") (part "XL-1608SURC-06"))
    )
    (comp (ref "LED58")
      (value "XL-1608SURC-06")
      (footprint "easyedapro:LED0603-RD_RED")
      (fields (field (name "Manufacturer") "XINGLIGHT(成兴光)"))
      (libsource (lib "easyedapro") (part "XL-1608SURC-06"))
    )
    (comp (ref "LED59")
      (value "XL-1608SURC-06")
      (footprint "easyedapro:LED0603-RD_RED")
      (fields (field (name "Manufacturer") "XINGLIGHT(成兴光)"))
      (libsource (lib "easyedapro") (part "XL-1608SURC-06"))
    )
    (comp (ref "LED60")
      (value "XL-1608SURC-06")
      (footprint "easyedapro:LED0603-RD_RED")
      (fields (field (name "Manufacturer") "XINGLIGHT(成兴光)"))
      (libsource (lib "easyedapro") (part "XL-1608SURC-06"))
    )
    (comp (ref "LED61")
      (value "XL-1608SURC-06")
      (footprint "easyedapro:LED0603-RD_RED")
      (fields (field (name "Manufacturer") "XINGLIGHT(成兴光)"))
      (libsource (lib "easyedapro") (part "XL-1608SURC-06"))
    )
    (comp (ref "LED62")
      (value "XL-1608SURC-06")
      (footprint "easyedapro:LED0603-RD_RED")
      (fields (field (name "Manufacturer") "XINGLIGHT(成兴光)"))
      (libsource (lib "easyedapro") (part "XL-1608SURC-06"))
    )
    (comp (ref "R61")
      (value "4.7kΩ")
      (footprint "easyedapro:R0603")
      (fields
        (field (name "Manufacturer Part") "0603WAF4701T5E")
        (field (name "Manufacturer") "UNI-ROYAL(厚声)")
      )
      (libsource (lib "easyedapro") (part "0603WAF4701T5E"))
    )
    (comp (ref "R62")
      (value "1kΩ")
      (footprint "easyedapro:R0603")
      (fields
        (field (name "Manufacturer Part") "0603WAF1001T5E")
        (field (name "Manufacturer") "UNI-ROYAL(厚声)")
      )
      (libsource (lib "easyedapro") (part "0603WAF1001T5E"))
    )
    (comp (ref "R63")
      (value "4.7kΩ")
      (footprint "easyedapro:R0603")
      (fields
        (field (name "Manufacturer Part") "0603WAF4701T5E")
        (field (name "Manufacturer") "UNI-ROYAL(厚声)")
      )
      (libsource (lib "easyedapro") (part "0603WAF4701T5E"))
    )
    (comp (ref "R64")
      (value "1kΩ")
      (footprint "easyedapro:R0603")
      (fields
        (field (name "Manufacturer Part") "0603WAF1001T5E")
        (field (name "Manufacturer") "UNI-ROYAL(厚声)")
      )
      (libsource (lib "easyedapro") (part "0603WAF1001T5E"))
    )
    (comp (ref "R65")
      (value "4.7kΩ")
      (footprint "easyedapro:R0603")
      (fields
        (field (name "Manufacturer Part") "0603WAF4701T5E")
        (field (name "Manufacturer") "UNI-ROYAL(厚声)")
      )
      (libsource (lib "easyedapro") (part "0603WAF4701T5E"))
    )
    (comp (ref "R66")
      (value "1kΩ")
      (footprint "easyedapro:R0603")
      (fields
        (field (name "Manufacturer Part") "0603WAF1001T5E")
        (field (name "Manufacturer") "UNI-ROYAL(厚声)")
      )
      (libsource (lib "easyedapro") (part "0603WAF1001T5E"))
    )
    (comp (ref "R67")
      (value "4.7kΩ")
      (footprint "easyedapro:R0603")
      (fields
        (field (name "Manufacturer Part") "0603WAF4701T5E")
        (field (name "Manufacturer") "UNI-ROYAL(厚声)")
      )
      (libsource (lib "easyedapro") (part "0603WAF4701T5E"))
    )
    (comp (ref "R68")
      (value "1kΩ")
      (footprint "easyedapro:R0603")
      (fields
        (field (name "Manufacturer Part") "0603WAF1001T5E")
        (field (name "Manufacturer") "UNI-ROYAL(厚声)")
      )
      (libsource (lib "easyedapro") (part "0603WAF1001T5E"))
    )
    (comp (ref "R69")
      (value "4.7kΩ")
      (footprint "easyedapro:R0603")
      (fields
        (field (name "Manufacturer Part") "0603WAF4701T5E")
        (field (name "Manufacturer") "UNI-ROYAL(厚声)")
      )
      (libsource (lib "easyedapro") (part "0603WAF4701T5E"))
    )
    (comp (ref "R70")
      (value "1kΩ")
      (footprint "easyedapro:R0603")
      (fields
        (field (name "Manufacturer Part") "0603WAF1001T5E")
        (field (name "Manufacturer") "UNI-ROYAL(厚声)")
      )
      (libsource (lib "easyedapro") (part "0603WAF1001T5E"))
    )
    (comp (ref "R71")
      (value "4.7kΩ")
      (footprint "easyedapro:R0603")
      (fields
        (field (name "Manufacturer Part") "0603WAF4701T5E")
        (field (name "Manufacturer") "UNI-ROYAL(厚声)")
      )
      (libsource (lib "easyedapro") (part "0603WAF4701T5E"))
    )
    (comp (ref "R72")
      (value "1kΩ")
      (footprint "easyedapro:R0603")
      (fields
        (field (name "Manufacturer Part") "0603WAF1001T5E")
        (field (name "Manufacturer") "UNI-ROYAL(厚声)")
      )
      (libsource (lib "easyedapro") (part "0603WAF1001T5E"))
    )
    (comp (ref "R73")
      (value "4.7kΩ")
      (footprint "easyedapro:R0603")
      (fields
        (field (name "Manufacturer Part") "0603WAF4701T5E")
        (field (name "Manufacturer") "UNI-ROYAL(厚声)")
      )
      (libsource (lib "easyedapro") (part "0603WAF4701T5E"))
    )
    (comp (ref "R74")
      (value "1kΩ")
      (footprint "easyedapro:R0603")
      (fields
        (field (name "Manufacturer Part") "0603WAF1001T5E")
        (field (name "Manufacturer") "UNI-ROYAL(厚声)")
      )
      (libsource (lib "easyedapro") (part "0603WAF1001T5E"))
    )
    (comp (ref "R75")
      (value "4.7kΩ")
      (footprint "easyedapro:R0603")
      (fields
        (field (name "Manufacturer Part") "0603WAF4701T5E")
        (field (name "Manufacturer") "UNI-ROYAL(厚声)")
      )
      (libsource (lib "easyedapro") (part "0603WAF4701T5E"))
    )
    (comp (ref "R76")
      (value "1kΩ")
      (footprint "easyedapro:R0603")
      (fields
        (field (name "Manufacturer Part") "0603WAF1001T5E")
        (field (name "Manufacturer") "UNI-ROYAL(厚声)")
      )
      (libsource (lib "easyedapro") (part "0603WAF1001T5E"))
    )
    (comp (ref "R94")
      (value "1kΩ")
      (footprint "easyedapro:R0603")
      (fields
        (field (name "Manufacturer Part") "0603WAF1001T5E")
        (field (name "Manufacturer") "UNI-ROYAL(厚声)")
      )
      (libsource (lib "easyedapro") (part "0603WAF1001T5E"))
    )
    (comp (ref "R95")
      (value "1kΩ")
      (footprint "easyedapro:R0603")
      (fields
        (field (name "Manufacturer Part") "0603WAF1001T5E")
        (field (name "Manufacturer") "UNI-ROYAL(厚声)")
      )
      (libsource (lib "easyedapro") (part "0603WAF1001T5E"))
    )
    (comp (ref "R96")
      (value "1kΩ")
      (footprint "easyedapro:R0603")
      (fields
        (field (name "Manufacturer Part") "0603WAF1001T5E")
        (field (name "Manufacturer") "UNI-ROYAL(厚声)")
      )
      (libsource (lib "easyedapro") (part "0603WAF1001T5E"))
    )
    (comp (ref "R97")
      (value "1kΩ")
      (footprint "easyedapro:R0603")
      (fields
        (field (name "Manufacturer Part") "0603WAF1001T5E")
        (field (name "Manufacturer") "UNI-ROYAL(厚声)")
      )
      (libsource (lib "easyedapro") (part "0603WAF1001T5E"))
    )
    (comp (ref "R98")
      (value "1kΩ")
      (footprint "easyedapro:R0603")
      (fields
        (field (name "Manufacturer Part") "0603WAF1001T5E")
        (field (name "Manufacturer") "UNI-ROYAL(厚声)")
      )
      (libsource (lib "easyedapro") (part "0603WAF1001T5E"))
    )
    (comp (ref "R99")
      (value "1kΩ")
      (footprint "easyedapro:R0603")
      (fields
        (field (name "Manufacturer Part") "0603WAF1001T5E")
        (field (name "Manufacturer") "UNI-ROYAL(厚声)")
      )
      (libsource (lib "easyedapro") (part "0603WAF1001T5E"))
    )
    (comp (ref "R100")
      (value "1kΩ")
      (footprint "easyedapro:R0603")
      (fields
        (field (name "Manufacturer Part") "0603WAF1001T5E")
        (field (name "Manufacturer") "UNI-ROYAL(厚声)")
      )
      (libsource (lib "easyedapro") (part "0603WAF1001T5E"))
    )
    (comp (ref "R101")
      (value "1kΩ")
      (footprint "easyedapro:R0603")
      (fields
        (field (name "Manufacturer Part") "0603WAF1001T5E")
        (field (name "Manufacturer") "UNI-ROYAL(厚声)")
      )
      (libsource (lib "easyedapro") (part "0603WAF1001T5E"))
    )
    (comp (ref "SW19")
      (value "TS-1088-AR02016")
      (footprint "easyedapro:SW-SMD_L3.9-W3.0-P4.45")
      (fields (field (name "Manufacturer") "XUNPU(讯普)"))
      (libsource (lib "easyedapro") (part "TS-1088-AR02016"))
    )
    (comp (ref "SW20")
      (value "TS-1088-AR02016")
      (footprint "easyedapro:SW-SMD_L3.9-W3.0-P4.45")
      (fields (field (name "Manufacturer") "XUNPU(讯普)"))
      (libsource (lib "easyedapro") (part "TS-1088-AR02016"))
    )
    (comp (ref "SW21")
      (value "TS-1088-AR02016")
      (footprint "easyedapro:SW-SMD_L3.9-W3.0-P4.45")
      (fields (field (name "Manufacturer") "XUNPU(讯普)"))
      (libsource (lib "easyedapro") (part "TS-1088-AR02016"))
    )
    (comp (ref "SW22")
      (value "TS-1088-AR02016")
      (footprint "easyedapro:SW-SMD_L3.9-W3.0-P4.45")
      (fields (field (name "Manufacturer") "XUNPU(讯普)"))
      (libsource (lib "easyedapro") (part "TS-1088-AR02016"))
    )
    (comp (ref "SW23")
      (value "TS-1088-AR02016")
      (footprint "easyedapro:SW-SMD_L3.9-W3.0-P4.45")
      (fields (field (name "Manufacturer") "XUNPU(讯普)"))
      (libsource (lib "easyedapro") (part "TS-1088-AR02016"))
    )
    (comp (ref "SW24")
      (value "TS-1088-AR02016")
      (footprint "easyedapro:SW-SMD_L3.9-W3.0-P4.45")
      (fields (field (name "Manufacturer") "XUNPU(讯普)"))
      (libsource (lib "easyedapro") (part "TS-1088-AR02016"))
    )
    (comp (ref "SW25")
      (value "TS-1088-AR02016")
      (footprint "easyedapro:SW-SMD_L3.9-W3.0-P4.45")
      (fields (field (name "Manufacturer") "XUNPU(讯普)"))
      (libsource (lib "easyedapro") (part "TS-1088-AR02016"))
    )
    (comp (ref "SW26")
      (value "TS-1088-AR02016")
      (footprint "easyedapro:SW-SMD_L3.9-W3.0-P4.45")
      (fields (field (name "Manufacturer") "XUNPU(讯普)"))
      (libsource (lib "easyedapro") (part "TS-1088-AR02016"))
    )
    (comp (ref "U31")
      (value "TPS1H200AQDGNRQ1")
      (footprint "easyedapro:EMSOP-8_L3.0-W3.0-P0.65-LS4.9-BL-EP-A")
      (fields (field (name "Manufacturer") "TI(德州仪器)"))
      (libsource (lib "easyedapro") (part "TPS1H200AQDGNRQ1"))
    )
    (comp (ref "U32")
      (value "TPS1H200AQDGNRQ1")
      (footprint "easyedapro:EMSOP-8_L3.0-W3.0-P0.65-LS4.9-BL-EP-A")
      (fields (field (name "Manufacturer") "TI(德州仪器)"))
      (libsource (lib "easyedapro") (part "TPS1H200AQDGNRQ1"))
    )
    (comp (ref "U33")
      (value "TPS1H200AQDGNRQ1")
      (footprint "easyedapro:EMSOP-8_L3.0-W3.0-P0.65-LS4.9-BL-EP-A")
      (fields (field (name "Manufacturer") "TI(德州仪器)"))
      (libsource (lib "easyedapro") (part "TPS1H200AQDGNRQ1"))
    )
    (comp (ref "U34")
      (value "TPS1H200AQDGNRQ1")
      (footprint "easyedapro:EMSOP-8_L3.0-W3.0-P0.65-LS4.9-BL-EP-A")
      (fields (field (name "Manufacturer") "TI(德州仪器)"))
      (libsource (lib "easyedapro") (part "TPS1H200AQDGNRQ1"))
    )
    (comp (ref "U35")
      (value "TPS1H200AQDGNRQ1")
      (footprint "easyedapro:EMSOP-8_L3.0-W3.0-P0.65-LS4.9-BL-EP-A")
      (fields (field (name "Manufacturer") "TI(德州仪器)"))
      (libsource (lib "easyedapro") (part "TPS1H200AQDGNRQ1"))
    )
    (comp (ref "U36")
      (value "TPS1H200AQDGNRQ1")
      (footprint "easyedapro:EMSOP-8_L3.0-W3.0-P0.65-LS4.9-BL-EP-A")
      (fields (field (name "Manufacturer") "TI(德州仪器)"))
      (libsource (lib "easyedapro") (part "TPS1H200AQDGNRQ1"))
    )
    (comp (ref "U37")
      (value "TPS1H200AQDGNRQ1")
      (footprint "easyedapro:EMSOP-8_L3.0-W3.0-P0.65-LS4.9-BL-EP-A")
      (fields (field (name "Manufacturer") "TI(德州仪器)"))
      (libsource (lib "easyedapro") (part "TPS1H200AQDGNRQ1"))
    )
    (comp (ref "U38")
      (value "TPS1H200AQDGNRQ1")
      (footprint "easyedapro:EMSOP-8_L3.0-W3.0-P0.65-LS4.9-BL-EP-A")
      (fields (field (name "Manufacturer") "TI(德州仪器)"))
      (libsource (lib "easyedapro") (part "TPS1H200AQDGNRQ1"))
    )
  )
  (nets
    (net (code "1") (name "5V") (class "Default")
      (node (ref "C8") (pin "1") (pinfunction "1_1") (pintype "input"))
      (node (ref "C9") (pin "1") (pinfunction "1_1") (pintype "unspecified"))
      (node (ref "R1") (pin "2") (pinfunction "2_2") (pintype "input"))
      (node (ref "R11") (pin "1") (pinfunction "1_1") (pintype "input"))
      (node (ref "R12") (pin "1") (pinfunction "1_1") (pintype "input"))
      (node (ref "R19") (pin "1") (pinfunction "1_1") (pintype "input"))
      (node (ref "R20") (pin "1") (pinfunction "1_1") (pintype "input"))
      (node (ref "R21") (pin "1") (pinfunction "1_1") (pintype "input"))
      (node (ref "R22") (pin "1") (pinfunction "1_1") (pintype "input"))
      (node (ref "R23") (pin "1") (pinfunction "1_1") (pintype "input"))
      (node (ref "R26") (pin "2") (pinfunction "2_2") (pintype "input"))
      (node (ref "R27") (pin "2") (pinfunction "2_2") (pintype "input"))
      (node (ref "R33") (pin "3") (pinfunction "3_3") (pintype "input"))
      (node (ref "R35") (pin "3") (pinfunction "3_3") (pintype "input"))
      (node (ref "R4") (pin "2") (pinfunction "2_2") (pintype "input"))
      (node (ref "SW1") (pin "1") (pinfunction "1_1") (pintype "unspecified"))
      (node (ref "SW10") (pin "1") (pinfunction "1_1") (pintype "unspecified"))
      (node (ref "SW11") (pin "1") (pinfunction "1_1") (pintype "unspecified"))
      (node (ref "SW12") (pin "1") (pinfunction "1_1") (pintype "unspecified"))
      (node (ref "SW13") (pin "1") (pinfunction "1_1") (pintype "unspecified"))
      (node (ref "SW14") (pin "1") (pinfunction "1_1") (pintype "unspecified"))
      (node (ref "SW15") (pin "1") (pinfunction "1_1") (pintype "unspecified"))
      (node (ref "SW16") (pin "1") (pinfunction "1_1") (pintype "unspecified"))
      (node (ref "SW17") (pin "1") (pinfunction "1_1") (pintype "unspecified"))
      (node (ref "SW18") (pin "1") (pinfunction "1_1") (pintype "unspecified"))
      (node (ref "SW19") (pin "1") (pinfunction "1_1") (pintype "unspecified"))
      (node (ref "SW2") (pin "1") (pinfunction "1_1") (pintype "unspecified"))
      (node (ref "SW20") (pin "1") (pinfunction "1_1") (pintype "unspecified"))
      (node (ref "SW21") (pin "1") (pinfunction "1_1") (pintype "unspecified"))
      (node (ref "SW22") (pin "1") (pinfunction "1_1") (pintype "unspecified"))
      (node (ref "SW23") (pin "1") (pinfunction "1_1") (pintype "unspecified"))
      (node (ref "SW24") (pin "1") (pinfunction "1_1") (pintype "unspecified"))
      (node (ref "SW25") (pin "1") (pinfunction "1_1") (pintype "unspecified"))
      (node (ref "SW26") (pin "1") (pinfunction "1_1") (pintype "unspecified"))
      (node (ref "SW3") (pin "1") (pinfunction "1_1") (pintype "unspecified"))
      (node (ref "SW4") (pin "1") (pinfunction "1_1") (pintype "unspecified"))
      (node (ref "SW7") (pin "1") (pinfunction "1_1") (pintype "unspecified"))
      (node (ref "SW8") (pin "1") (pinfunction "1_1") (pintype "unspecified"))
      (node (ref "SW9") (pin "1") (pinfunction "1_1") (pintype "unspecified"))
      (node (ref "U11") (pin "5") (pinfunction "VCC+_5") (pintype "input"))
      (node (ref "U12") (pin "5") (pinfunction "VCC+_5") (pintype "input"))
      (node (ref "U5") (pin "5V@0") (pinfunction "5V_5V@0") (pintype "unspecified"))
      (node (ref "U5") (pin "5V@1") (pinfunction "5V_5V@1") (pintype "unspecified"))
      (node (ref "U5") (pin "5V@2") (pinfunction "5V_5V@2") (pintype "unspecified"))
      (node (ref "U9") (pin "8") (pinfunction "VCC_8") (pintype "unspecified"))
    )
    (net (code "2") (name "24V") (class "Default")
      (node (ref "C4") (pin "1") (pinfunction "1_1") (pintype "input"))
      (node (ref "R8") (pin "1") (pinfunction "1_1") (pintype "input"))
      (node (ref "RLY1") (pin "2") (pinfunction "2_2") (pintype "input"))
      (node (ref "U1") (pin "1") (pinfunction "VIN_1") (pintype "unspecified"))
      (node (ref "U3") (pin "2") (pinfunction "2_2") (pintype "input"))
    )
    (net (code "3") (name "FAULTBUS") (class "Default")
      (node (ref "LED2") (pin "2") (pinfunction "A_2") (pintype "unspecified"))
      (node (ref "LED23") (pin "2") (pinfunction "A_2") (pintype "unspecified"))
      (node (ref "LED24") (pin "2") (pinfunction "A_2") (pintype "unspecified"))
      (node (ref "LED27") (pin "2") (pinfunction "A_2") (pintype "unspecified"))
      (node (ref "LED28") (pin "2") (pinfunction "A_2") (pintype "unspecified"))
      (node (ref "LED31") (pin "2") (pinfunction "A_2") (pintype "unspecified"))
      (node (ref "LED32") (pin "2") (pinfunction "A_2") (pintype "unspecified"))
      (node (ref "LED35") (pin "2") (pinfunction "A_2") (pintype "unspecified"))
      (node (ref "LED36") (pin "2") (pinfunction "A_2") (pintype "unspecified"))
      (node (ref "LED39") (pin "2") (pinfunction "A_2") (pintype "unspecified"))
      (node (ref "LED40") (pin "2") (pinfunction "A_2") (pintype "unspecified"))
      (node (ref "LED43") (pin "2") (pinfunction "A_2") (pintype "unspecified"))
      (node (ref "LED44") (pin "2") (pinfunction "A_2") (pintype "unspecified"))
      (node (ref "LED47") (pin "2") (pinfunction "A_2") (pintype "unspecified"))
      (node (ref "LED48") (pin "2") (pinfunction "A_2") (pintype "unspecified"))
      (node (ref "LED5") (pin "2") (pinfunction "A_2") (pintype "unspecified"))
      (node (ref "LED51") (pin "2") (pinfunction "A_2") (pintype "unspecified"))
      (node (ref "LED52") (pin "2") (pinfunction "A_2") (pintype "unspecified"))
      (node (ref "LED55") (pin "2") (pinfunction "A_2") (pintype "unspecified"))
      (node (ref "LED56") (pin "2") (pinfunction "A_2") (pintype "unspecified"))
      (node (ref "LED59") (pin "2") (pinfunction "A_2") (pintype "unspecified"))
      (node (ref "LED60") (pin "2") (pinfunction "A_2") (pintype "unspecified"))
      (node (ref "LED7") (pin "2") (pinfunction "A_2") (pintype "unspecified"))
      (node (ref "LED9") (pin "2") (pinfunction "A_2") (pintype "unspecified"))
      (node (ref "R1") (pin "1") (pinfunction "1_1") (pintype "input"))
      (node (ref "U5") (pin "51") (pinfunction "51_51") (pintype "unspecified"))
    )
    (net (code "4") (name "GND") (class "Default")
      (node (ref "C10") (pin "1") (pinfunction "1_1") (pintype "unspecified"))
      (node (ref "C11") (pin "1") (pinfunction "1_1") (pintype "unspecified"))
      (node (ref "C12") (pin "1") (pinfunction "1_1") (pintype "unspecified"))
      (node (ref "C13") (pin "1") (pinfunction "1_1") (pintype "unspecified"))
      (node (ref "C14") (pin "1") (pinfunction "1_1") (pintype "unspecified"))
      (node (ref "C15") (pin "1") (pinfunction "1_1") (pintype "unspecified"))
      (node (ref "C16") (pin "1") (pinfunction "1_1") (pintype "unspecified"))
      (node (ref "C18") (pin "1") (pinfunction "1_1") (pintype "unspecified"))
      (node (ref "C19") (pin "1") (pinfunction "1_1") (pintype "unspecified"))
      (node (ref "C2") (pin "2") (pinfunction "2_2") (pintype "input"))
      (node (ref "C20") (pin "1") (pinfunction "1_1") (pintype "unspecified"))
      (node (ref "C21") (pin "1") (pinfunction "1_1") (pintype "unspecified"))
      (node (ref "C22") (pin "1") (pinfunction "1_1") (pintype "unspecified"))
      (node (ref "C23") (pin "1") (pinfunction "1_1") (pintype "unspecified"))
      (node (ref "C24") (pin "1") (pinfunction "1_1") (pintype "unspecified"))
      (node (ref "C25") (pin "1") (pinfunction "1_1") (pintype "unspecified"))
      (node (ref "C26") (pin "1") (pinfunction "1_1") (pintype "unspecified"))
      (node (ref "C27") (pin "1") (pinfunction "1_1") (pintype "unspecified"))
      (node (ref "C28") (pin "1") (pinfunction "1_1") (pintype "unspecified"))
      (node (ref "C29") (pin "1") (pinfunction "1_1") (pintype "unspecified"))
      (node (ref "C3") (pin "1") (pinfunction "1_1") (pintype "unspecified"))
      (node (ref "C30") (pin "1") (pinfunction "1_1") (pintype "unspecified"))
      (node (ref "C31") (pin "1") (pinfunction "1_1") (pintype "unspecified"))
      (node (ref "C32") (pin "1") (pinfunction "1_1") (pintype "unspecified"))
      (node (ref "C33") (pin "1") (pinfunction "1_1") (pintype "unspecified"))
      (node (ref "C34") (pin "1") (pinfunction "1_1") (pintype "unspecified"))
      (node (ref "C35") (pin "1") (pinfunction "1_1") (pintype "unspecified"))
      (node (ref "C4") (pin "2") (pinfunction "2_2") (pintype "input"))
      (node (ref "C5") (pin "2") (pinfunction "2_2") (pintype "input"))
      (node (ref "C6") (pin "1") (pinfunction "1_1") (pintype "unspecified"))
      (node (ref "C7") (pin "1") (pinfunction "1_1") (pintype "unspecified"))
      (node (ref "C8") (pin "2") (pinfunction "2_2") (pintype "input"))
      (node (ref "C9") (pin "2") (pinfunction "2_2") (pintype "unspecified"))
      (node (ref "CN1") (pin "2") (pinfunction "2_2") (pintype "unspecified"))
      (node (ref "CN11") (pin "2") (pinfunction "2_2") (pintype "unspecified"))
      (node (ref "CN12") (pin "2") (pinfunction "2_2") (pintype "unspecified"))
      (node (ref "CN13") (pin "2") (pinfunction "2_2") (pintype "unspecified"))
      (node (ref "CN14") (pin "2") (pinfunction "2_2") (pintype "unspecified"))
      (node (ref "CN15") (pin "2") (pinfunction "2_2") (pintype "unspecified"))
      (node (ref "CN16") (pin "2") (pinfunction "2_2") (pintype "unspecified"))
      (node (ref "CN17") (pin "2") (pinfunction "2_2") (pintype "unspecified"))
      (node (ref "CN18") (pin "2") (pinfunction "2_2") (pintype "unspecified"))
      (node (ref "CN19") (pin "2") (pinfunction "2_2") (pintype "unspecified"))
      (node (ref "CN2") (pin "1") (pinfunction "1_1") (pintype "unspecified"))
      (node (ref "CN20") (pin "2") (pinfunction "2_2") (pintype "unspecified"))
      (node (ref "CN21") (pin "2") (pinfunction "2_2") (pintype "unspecified"))
      (node (ref "CN22") (pin "2") (pinfunction "2_2") (pintype "unspecified"))
      (node (ref "CN23") (pin "2") (pinfunction "2_2") (pintype "unspecified"))
      (node (ref "CN24") (pin "2") (pinfunction "2_2") (pintype "unspecified"))
      (node (ref "CN25") (pin "2") (pinfunction "2_2") (pintype "unspecified"))
      (node (ref "CN26") (pin "2") (pinfunction "2_2") (pintype "unspecified"))
      (node (ref "CN27") (pin "2") (pinfunction "2_2") (pintype "unspecified"))
      (node (ref "CN28") (pin "2") (pinfunction "2_2") (pintype "unspecified"))
      (node (ref "CN29") (pin "2") (pinfunction "2_2") (pintype "unspecified"))
      (node (ref "CN3") (pin "2") (pinfunction "2_2") (pintype "unspecified"))
      (node (ref "CN30") (pin "2") (pinfunction "2_2") (pintype "unspecified"))
      (node (ref "CN4") (pin "1") (pinfunction "1_1") (pintype "unspecified"))
      (node (ref "CN5") (pin "2") (pinfunction "2_2") (pintype "unspecified"))
      (node (ref "CN6") (pin "2") (pinfunction "2_2") (pintype "unspecified"))
      (node (ref "D2") (pin "2") (pinfunction "A_2") (pintype "unspecified"))
      (node (ref "LED3") (pin "1") (pinfunction "K_1") (pintype "input"))
      (node (ref "Q1") (pin "2") (pinfunction "2_2") (pintype "input"))
      (node (ref "R100") (pin "2") (pinfunction "2_2") (pintype "input"))
      (node (ref "R101") (pin "2") (pinfunction "2_2") (pintype "input"))
      (node (ref "R14") (pin "2") (pinfunction "2_2") (pintype "input"))
      (node (ref "R17") (pin "1") (pinfunction "1_1") (pintype "input"))
      (node (ref "R18") (pin "2") (pinfunction "2_2") (pintype "input"))
      (node (ref "R28") (pin "2") (pinfunction "2_2") (pintype "input"))
      (node (ref "R33") (pin "1") (pinfunction "1_1") (pintype "input"))
      (node (ref "R35") (pin "1") (pinfunction "1_1") (pintype "input"))
      (node (ref "R7") (pin "2") (pinfunction "2_2") (pintype "input"))
      (node (ref "R77") (pin "2") (pinfunction "2_2") (pintype "input"))
      (node (ref "R78") (pin "2") (pinfunction "2_2") (pintype "input"))
      (node (ref "R79") (pin "2") (pinfunction "2_2") (pintype "input"))
      (node (ref "R80") (pin "2") (pinfunction "2_2") (pintype "input"))
      (node (ref "R81") (pin "2") (pinfunction "2_2") (pintype "input"))
      (node (ref "R82") (pin "2") (pinfunction "2_2") (pintype "input"))
      (node (ref "R84") (pin "2") (pinfunction "2_2") (pintype "input"))
      (node (ref "R85") (pin "2") (pinfunction "2_2") (pintype "input"))
      (node (ref "R86") (pin "2") (pinfunction "2_2") (pintype "input"))
      (node (ref "R87") (pin "2") (pinfunction "2_2") (pintype "input"))
      (node (ref "R88") (pin "2") (pinfunction "2_2") (pintype "input"))
      (node (ref "R89") (pin "2") (pinfunction "2_2") (pintype "input"))
      (node (ref "R9") (pin "1") (pinfunction "1_1") (pintype "input"))
      (node (ref "R90") (pin "2") (pinfunction "2_2") (pintype "input"))
      (node (ref "R91") (pin "2") (pinfunction "2_2") (pintype "input"))
      (node (ref "R92") (pin "2") (pinfunction "2_2") (pintype "input"))
      (node (ref "R93") (pin "2") (pinfunction "2_2") (pintype "input"))
      (node (ref "R94") (pin "2") (pinfunction "2_2") (pintype "input"))
      (node (ref "R95") (pin "2") (pinfunction "2_2") (pintype "input"))
      (node (ref "R96") (pin "2") (pinfunction "2_2") (pintype "input"))
      (node (ref "R97") (pin "2") (pinfunction "2_2") (pintype "input"))
      (node (ref "R98") (pin "2") (pinfunction "2_2") (pintype "input"))
      (node (ref "R99") (pin "2") (pinfunction "2_2") (pintype "input"))
      (node (ref "U1") (pin "3") (pinfunction "GND_3") (pintype "unspecified"))
      (node (ref "U1") (pin "5") (pinfunction "ON#/OFF_5") (pintype "unspecified"))
      (node (ref "U1") (pin "6") (pinfunction "GND_6") (pintype "unspecified"))
      (node (ref "U10") (pin "6") (pinfunction "GND_6") (pintype "unspecified"))
      (node (ref "U10") (pin "9") (pinfunction "EP_9") (pintype "unspecified"))
      (node (ref "U11") (pin "2") (pinfunction "GND_2") (pintype "input"))
      (node (ref "U12") (pin "2") (pinfunction "GND_2") (pintype "input"))
      (node (ref "U19") (pin "6") (pinfunction "GND_6") (pintype "unspecified"))
      (node (ref "U19") (pin "9") (pinfunction "EP_9") (pintype "unspecified"))
      (node (ref "U2") (pin "6") (pinfunction "GND_6") (pintype "unspecified"))
      (node (ref "U2") (pin "9") (pinfunction "EP_9") (pintype "unspecified"))
      (node (ref "U20") (pin "6") (pinfunction "GND_6") (pintype "unspecified"))
      (node (ref "U20") (pin "9") (pinfunction "EP_9") (pintype "unspecified"))
      (node (ref "U21") (pin "6") (pinfunction "GND_6") (pintype "unspecified"))
      (node (ref "U21") (pin "9") (pinfunction "EP_9") (pintype "unspecified"))
      (node (ref "U22") (pin "6") (pinfunction "GND_6") (pintype "unspecified"))
      (node (ref "U22") (pin "9") (pinfunction "EP_9") (pintype "unspecified"))
      (node (ref "U23") (pin "6") (pinfunction "GND_6") (pintype "unspecified"))
      (node (ref "U23") (pin "9") (pinfunction "EP_9") (pintype "unspecified"))
      (node (ref "U24") (pin "6") (pinfunction "GND_6") (pintype "unspecified"))
      (node (ref "U24") (pin "9") (pinfunction "EP_9") (pintype "unspecified"))
      (node (ref "U25") (pin "6") (pinfunction "GND_6") (pintype "unspecified"))
      (node (ref "U25") (pin "9") (pinfunction "EP_9") (pintype "unspecified"))
      (node (ref "U26") (pin "6") (pinfunction "GND_6") (pintype "unspecified"))
      (node (ref "U26") (pin "9") (pinfunction "EP_9") (pintype "unspecified"))
      (node (ref "U27") (pin "6") (pinfunction "GND_6") (pintype "unspecified"))
      (node (ref "U27") (pin "9") (pinfunction "EP_9") (pintype "unspecified"))
      (node (ref "U28") (pin "6") (pinfunction "GND_6") (pintype "unspecified"))
      (node (ref "U28") (pin "9") (pinfunction "EP_9") (pintype "unspecified"))
      (node (ref "U29") (pin "6") (pinfunction "GND_6") (pintype "unspecified"))
      (node (ref "U29") (pin "9") (pinfunction "EP_9") (pintype "unspecified"))
      (node (ref "U3") (pin "1") (pinfunction "1_1") (pintype "input"))
      (node (ref "U30") (pin "6") (pinfunction "GND_6") (pintype "unspecified"))
      (node (ref "U30") (pin "9") (pinfunction "EP_9") (pintype "unspecified"))
      (node (ref "U31") (pin "6") (pinfunction "GND_6") (pintype "unspecified"))
      (node (ref "U31") (pin "9") (pinfunction "EP_9") (pintype "unspecified"))
      (node (ref "U32") (pin "6") (pinfunction "GND_6") (pintype "unspecified"))
      (node (ref "U32") (pin "9") (pinfunction "EP_9") (pintype "unspecified"))
      (node (ref "U33") (pin "6") (pinfunction "GND_6") (pintype "unspecified"))
      (node (ref "U33") (pin "9") (pinfunction "EP_9") (pintype "unspecified"))
      (node (ref "U34") (pin "6") (pinfunction "GND_6") (pintype "unspecified"))
      (node (ref "U34") (pin "9") (pinfunction "EP_9") (pintype "unspecified"))
      (node (ref "U35") (pin "6") (pinfunction "GND_6") (pintype "unspecified"))
      (node (ref "U35") (pin "9") (pinfunction "EP_9") (pintype "unspecified"))
      (node (ref "U36") (pin "6") (pinfunction "GND_6") (pintype "unspecified"))
      (node (ref "U36") (pin "9") (pinfunction "EP_9") (pintype "unspecified"))
      (node (ref "U37") (pin "6") (pinfunction "GND_6") (pintype "unspecified"))
      (node (ref "U37") (pin "9") (pinfunction "EP_9") (pintype "unspecified"))
      (node (ref "U38") (pin "6") (pinfunction "GND_6") (pintype "unspecified"))
      (node (ref "U38") (pin "9") (pinfunction "EP_9") (pintype "unspecified"))
      (node (ref "U4") (pin "2") (pinfunction "2_2") (pintype "unspecified"))
      (node (ref "U5") (pin "GND@0") (pinfunction "GND_GND@0") (pintype "unspecified"))
      (node (ref "U5") (pin "GND@1") (pinfunction "GND_GND@1") (pintype "unspecified"))
      (node (ref "U5") (pin "GND@2") (pinfunction "GND_GND@2") (pintype "unspecified"))
      (node (ref "U5") (pin "GND@3") (pinfunction "GND_GND@3") (pintype "unspecified"))
      (node (ref "U5") (pin "GND@4") (pinfunction "GND_GND@4") (pintype "unspecified"))
      (node (ref "U6") (pin "6") (pinfunction "GND_6") (pintype "unspecified"))
      (node (ref "U6") (pin "9") (pinfunction "EP_9") (pintype "unspecified"))
      (node (ref "U7") (pin "6") (pinfunction "GND_6") (pintype "unspecified"))
      (node (ref "U7") (pin "9") (pinfunction "EP_9") (pintype "unspecified"))
      (node (ref "U9") (pin "5") (pinfunction "GND_5") (pintype "unspecified"))
    )
    (net (code "5") (name "LEAKSENS1") (class "Default")
      (node (ref "R26") (pin "1") (pinfunction "1_1") (pintype "input"))
      (node (ref "R29") (pin "2") (pinfunction "2_2") (pintype "input"))
      (node (ref "U11") (pin "4") (pinfunction "OUT_4") (pintype "input"))
      (node (ref "U5") (pin "A5") (pinfunction "A5_A5") (pintype "unspecified"))
    )
    (net (code "6") (name "LEAKSENS1_SUPPPLY") (class "Default")
      (node (ref "R31") (pin "1") (pinfunction "1_1") (pintype "input"))
      (node (ref "U5") (pin "A6") (pinfunction "A6_A6") (pintype "unspecified"))
    )
    (net (code "7") (name "LEAKSENS2") (class "Default")
      (node (ref "R27") (pin "1") (pinfunction "1_1") (pintype "input"))
      (node (ref "R30") (pin "2") (pinfunction "2_2") (pintype "input"))
      (node (ref "U12") (pin "4") (pinfunction "OUT_4") (pintype "input"))
      (node (ref "U5") (pin "A8") (pinfunction "A8_A8") (pintype "unspecified"))
    )
    (net (code "8") (name "LEAKSENS2_SUPPPLY") (class "Default")
      (node (ref "R32") (pin "1") (pinfunction "1_1") (pintype "input"))
      (node (ref "U5") (pin "A9") (pinfunction "A9_A9") (pintype "unspecified"))
    )
    (net (code "9") (name "LOW") (class "Default")
      (node (ref "C1") (pin "2") (pinfunction "2_2") (pintype "input"))
      (node (ref "C2") (pin "1") (pinfunction "1_1") (pintype "input"))
      (node (ref "C5") (pin "1") (pinfunction "1_1") (pintype "input"))
      (node (ref "CN2") (pin "4") (pinfunction "4_4") (pintype "unspecified"))
      (node (ref "CN4") (pin "4") (pinfunction "4_4") (pintype "unspecified"))
      (node (ref "D1") (pin "1") (pinfunction "K_1") (pintype "unspecified"))
      (node (ref "L1") (pin "2") (pinfunction "2_2") (pintype "unspecified"))
      (node (ref "R5") (pin "2") (pinfunction "2_2") (pintype "input"))
      (node (ref "R5") (pin "3") (pinfunction "3_3") (pintype "input"))
      (node (ref "RLY1") (pin "3") (pinfunction "3_3") (pintype "input"))
      (node (ref "RLY1") (pin "4") (pinfunction "4_4") (pintype "input"))
      (node (ref "U5") (pin "VIN") (pinfunction "VIN_VIN") (pintype "unspecified"))
    )
    (net (code "10") (name "MILK1") (class "Default")
      (node (ref "R3") (pin "2") (pinfunction "2_2") (pintype "input"))
      (node (ref "U5") (pin "2") (pinfunction "2_2") (pintype "unspecified"))
    )
    (net (code "11") (name "MILK2") (class "Default")
      (node (ref "R13") (pin "2") (pinfunction "2_2") (pintype "input"))
      (node (ref "U5") (pin "3") (pinfunction "3_3") (pintype "unspecified"))
    )
    (net (code "12") (name "MILK3") (class "Default")
      (node (ref "R16") (pin "2") (pinfunction "2_2") (pintype "input"))
      (node (ref "U5") (pin "4") (pinfunction "4_4") (pintype "unspecified"))
    )
    (net (code "13") (name "MILK4") (class "Default")
      (node (ref "R25") (pin "2") (pinfunction "2_2") (pintype "input"))
      (node (ref "U5") (pin "5") (pinfunction "5_5") (pintype "unspecified"))
    )
    (net (code "14") (name "MILK5") (class "Default")
      (node (ref "R41") (pin "2") (pinfunction "2_2") (pintype "input"))
      (node (ref "U5") (pin "6") (pinfunction "6_6") (pintype "unspecified"))
    )
    (net (code "15") (name "MILK6") (class "Default")
      (node (ref "R43") (pin "2") (pinfunction "2_2") (pintype "input"))
      (node (ref "U5") (pin "7") (pinfunction "7_7") (pintype "unspecified"))
    )
    (net (code "16") (name "MILK7") (class "Default")
      (node (ref "R49") (pin "2") (pinfunction "2_2") (pintype "input"))
      (node (ref "U5") (pin "8") (pinfunction "8_8") (pintype "unspecified"))
    )
    (net (code "17") (name "MILK8") (class "Default")
      (node (ref "R51") (pin "2") (pinfunction "2_2") (pintype "input"))
      (node (ref "U5") (pin "9") (pinfunction "9_9") (pintype "unspecified"))
    )
    (net (code "18") (name "MOTORSUPPLY") (class "Default")
      (node (ref "RLY1") (pin "5") (pinfunction "5_5") (pintype "input"))
      (node (ref "U10") (pin "8") (pinfunction "VS_8") (pintype "unspecified"))
      (node (ref "U19") (pin "8") (pinfunction "VS_8") (pintype "unspecified"))
      (node (ref "U2") (pin "8") (pinfunction "VS_8") (pintype "unspecified"))
      (node (ref "U20") (pin "8") (pinfunction "VS_8") (pintype "unspecified"))
      (node (ref "U21") (pin "8") (pinfunction "VS_8") (pintype "unspecified"))
      (node (ref "U22") (pin "8") (pinfunction "VS_8") (pintype "unspecified"))
      (node (ref "U23") (pin "8") (pinfunction "VS_8") (pintype "unspecified"))
      (node (ref "U24") (pin "8") (pinfunction "VS_8") (pintype "unspecified"))
      (node (ref "U25") (pin "8") (pinfunction "VS_8") (pintype "unspecified"))
      (node (ref "U26") (pin "8") (pinfunction "VS_8") (pintype "unspecified"))
      (node (ref "U27") (pin "8") (pinfunction "VS_8") (pintype "unspecified"))
      (node (ref "U28") (pin "8") (pinfunction "VS_8") (pintype "unspecified"))
      (node (ref "U29") (pin "8") (pinfunction "VS_8") (pintype "unspecified"))
      (node (ref "U30") (pin "8") (pinfunction "VS_8") (pintype "unspecified"))
      (node (ref "U31") (pin "8") (pinfunction "VS_8") (pintype "unspecified"))
      (node (ref "U32") (pin "8") (pinfunction "VS_8") (pintype "unspecified"))
      (node (ref "U33") (pin "8") (pinfunction "VS_8") (pintype "unspecified"))
      (node (ref "U34") (pin "8") (pinfunction "VS_8") (pintype "unspecified"))
      (node (ref "U35") (pin "8") (pinfunction "VS_8") (pintype "unspecified"))
      (node (ref "U36") (pin "8") (pinfunction "VS_8") (pintype "unspecified"))
      (node (ref "U37") (pin "8") (pinfunction "VS_8") (pintype "unspecified"))
      (node (ref "U38") (pin "8") (pinfunction "VS_8") (pintype "unspecified"))
      (node (ref "U6") (pin "8") (pinfunction "VS_8") (pintype "unspecified"))
      (node (ref "U7") (pin "8") (pinfunction "VS_8") (pintype "unspecified"))
    )
    (net (code "19") (name "Net-(D1-A)") (class "Default")
      (node (ref "D1") (pin "2") (pinfunction "A_2") (pintype "unspecified"))
      (node (ref "Q1") (pin "3") (pinfunction "3_3") (pintype "input"))
      (node (ref "RLY1") (pin "1") (pinfunction "1_1") (pintype "input"))
    )
    (net (code "20") (name "Net-(D2-K)") (class "Default")
      (node (ref "D2") (pin "1") (pinfunction "K_1") (pintype "unspecified"))
      (node (ref "L1") (pin "1") (pinfunction "1_1") (pintype "unspecified"))
      (node (ref "U1") (pin "2") (pinfunction "OUTPUT_2") (pintype "unspecified"))
    )
    (net (code "21") (name "Net-(D3-A)") (class "Default")
      (node (ref "D3") (pin "2") (pinfunction "A_2") (pintype "unspecified"))
      (node (ref "R77") (pin "1") (pinfunction "1_1") (pintype "input"))
    )
    (net (code "22") (name "Net-(D3-C)") (class "Default")
      (node (ref "CN7") (pin "2") (pinfunction "2_2") (pintype "unspecified"))
      (node (ref "D3") (pin "1") (pinfunction "C_1") (pintype "unspecified"))
      (node (ref "R34") (pin "1") (pinfunction "1_1") (pintype "input"))
    )
    (net (code "23") (name "Net-(D4-A)") (class "Default")
      (node (ref "D4") (pin "2") (pinfunction "A_2") (pintype "unspecified"))
      (node (ref "R78") (pin "1") (pinfunction "1_1") (pintype "input"))
    )
    (net (code "24") (name "Net-(D4-C)") (class "Default")
      (node (ref "CN8") (pin "2") (pinfunction "2_2") (pintype "unspecified"))
      (node (ref "D4") (pin "1") (pinfunction "C_1") (pintype "unspecified"))
      (node (ref "R36") (pin "1") (pinfunction "1_1") (pintype "input"))
    )
    (net (code "25") (name "Net-(D5-A)") (class "Default")
      (node (ref "D5") (pin "2") (pinfunction "A_2") (pintype "unspecified"))
      (node (ref "R79") (pin "1") (pinfunction "1_1") (pintype "input"))
    )
    (net (code "26") (name "Net-(D5-C)") (class "Default")
      (node (ref "CN7") (pin "1") (pinfunction "1_1") (pintype "unspecified"))
      (node (ref "D5") (pin "1") (pinfunction "C_1") (pintype "unspecified"))
      (node (ref "R31") (pin "2") (pinfunction "2_2") (pintype "input"))
    )
    (net (code "27") (name "Net-(D6-A)") (class "Default")
      (node (ref "D6") (pin "2") (pinfunction "A_2") (pintype "unspecified"))
      (node (ref "R80") (pin "1") (pinfunction "1_1") (pintype "input"))
    )
    (net (code "28") (name "Net-(D6-C)") (class "Default")
      (node (ref "CN8") (pin "1") (pinfunction "1_1") (pintype "unspecified"))
      (node (ref "D6") (pin "1") (pinfunction "C_1") (pintype "unspecified"))
      (node (ref "R32") (pin "2") (pinfunction "2_2") (pintype "input"))
    )
    (net (code "29") (name "Net-(LED1-A)") (class "Default")
      (node (ref "LED1") (pin "2") (pinfunction "A_2") (pintype "unspecified"))
      (node (ref "SW1") (pin "2") (pinfunction "2_2") (pintype "unspecified"))
    )
    (net (code "30") (name "Net-(LED1-K)") (class "Default")
      (node (ref "LED1") (pin "1") (pinfunction "K_1") (pintype "unspecified"))
      (node (ref "R2") (pin "1") (pinfunction "1_1") (pintype "input"))
    )
    (net (code "31") (name "Net-(LED2-K)") (class "Default")
      (node (ref "LED2") (pin "1") (pinfunction "K_1") (pintype "unspecified"))
      (node (ref "U2") (pin "3") (pinfunction "FAULT#_3") (pintype "unspecified"))
    )
    (net (code "32") (name "Net-(LED3-A)") (class "Default")
      (node (ref "LED3") (pin "2") (pinfunction "A_2") (pintype "input"))
      (node (ref "R8") (pin "2") (pinfunction "2_2") (pintype "input"))
    )
    (net (code "33") (name "Net-(LED4-A)") (class "Default")
      (node (ref "LED4") (pin "2") (pinfunction "A_2") (pintype "unspecified"))
      (node (ref "SW2") (pin "2") (pinfunction "2_2") (pintype "unspecified"))
    )
    (net (code "34") (name "Net-(LED4-K)") (class "Default")
      (node (ref "LED4") (pin "1") (pinfunction "K_1") (pintype "unspecified"))
      (node (ref "R10") (pin "1") (pinfunction "1_1") (pintype "input"))
    )
    (net (code "35") (name "Net-(LED5-K)") (class "Default")
      (node (ref "LED5") (pin "1") (pinfunction "K_1") (pintype "unspecified"))
      (node (ref "U6") (pin "3") (pinfunction "FAULT#_3") (pintype "unspecified"))
    )
    (net (code "36") (name "Net-(LED6-A)") (class "Default")
      (node (ref "LED6") (pin "2") (pinfunction "A_2") (pintype "unspecified"))
      (node (ref "SW3") (pin "2") (pinfunction "2_2") (pintype "unspecified"))
    )
    (net (code "37") (name "Net-(LED6-K)") (class "Default")
      (node (ref "LED6") (pin "1") (pinfunction "K_1") (pintype "unspecified"))
      (node (ref "R15") (pin "1") (pinfunction "1_1") (pintype "input"))
    )
    (net (code "38") (name "Net-(LED7-K)") (class "Default")
      (node (ref "LED7") (pin "1") (pinfunction "K_1") (pintype "unspecified"))
      (node (ref "U7") (pin "3") (pinfunction "FAULT#_3") (pintype "unspecified"))
    )
    (net (code "39") (name "Net-(LED8-A)") (class "Default")
      (node (ref "LED8") (pin "2") (pinfunction "A_2") (pintype "unspecified"))
      (node (ref "SW4") (pin "2") (pinfunction "2_2") (pintype "unspecified"))
    )
    (net (code "40") (name "Net-(LED8-K)") (class "Default")
      (node (ref "LED8") (pin "1") (pinfunction "K_1") (pintype "unspecified"))
      (node (ref "R24") (pin "1") (pinfunction "1_1") (pintype "input"))
    )
    (net (code "41") (name "Net-(LED9-K)") (class "Default")
      (node (ref "LED9") (pin "1") (pinfunction "K_1") (pintype "unspecified"))
      (node (ref "U10") (pin "3") (pinfunction "FAULT#_3") (pintype "unspecified"))
    )
    (net (code "42") (name "Net-(LED23-K)") (class "Default")
      (node (ref "LED23") (pin "1") (pinfunction "K_1") (pintype "unspecified"))
      (node (ref "U19") (pin "3") (pinfunction "FAULT#_3") (pintype "unspecified"))
    )
    (net (code "43") (name "Net-(LED24-K)") (class "Default")
      (node (ref "LED24") (pin "1") (pinfunction "K_1") (pintype "unspecified"))
      (node (ref "U20") (pin "3") (pinfunction "FAULT#_3") (pintype "unspecified"))
    )
    (net (code "44") (name "Net-(LED25-A)") (class "Default")
      (node (ref "LED25") (pin "2") (pinfunction "A_2") (pintype "unspecified"))
      (node (ref "SW7") (pin "2") (pinfunction "2_2") (pintype "unspecified"))
    )
    (net (code "45") (name "Net-(LED25-K)") (class "Default")
      (node (ref "LED25") (pin "1") (pinfunction "K_1") (pintype "unspecified"))
      (node (ref "R38") (pin "1") (pinfunction "1_1") (pintype "input"))
    )
    (net (code "46") (name "Net-(LED26-A)") (class "Default")
      (node (ref "LED26") (pin "2") (pinfunction "A_2") (pintype "unspecified"))
      (node (ref "SW8") (pin "2") (pinfunction "2_2") (pintype "unspecified"))
    )
    (net (code "47") (name "Net-(LED26-K)") (class "Default")
      (node (ref "LED26") (pin "1") (pinfunction "K_1") (pintype "unspecified"))
      (node (ref "R40") (pin "1") (pinfunction "1_1") (pintype "input"))
    )
    (net (code "48") (name "Net-(LED27-K)") (class "Default")
      (node (ref "LED27") (pin "1") (pinfunction "K_1") (pintype "unspecified"))
      (node (ref "U21") (pin "3") (pinfunction "FAULT#_3") (pintype "unspecified"))
    )
    (net (code "49") (name "Net-(LED28-K)") (class "Default")
      (node (ref "LED28") (pin "1") (pinfunction "K_1") (pintype "unspecified"))
      (node (ref "U22") (pin "3") (pinfunction "FAULT#_3") (pintype "unspecified"))
    )
    (net (code "50") (name "Net-(LED29-A)") (class "Default")
      (node (ref "LED29") (pin "2") (pinfunction "A_2") (pintype "unspecified"))
      (node (ref "SW9") (pin "2") (pinfunction "2_2") (pintype "unspecified"))
    )
    (net (code "51") (name "Net-(LED29-K)") (class "Default")
      (node (ref "LED29") (pin "1") (pinfunction "K_1") (pintype "unspecified"))
      (node (ref "R42") (pin "1") (pinfunction "1_1") (pintype "input"))
    )
    (net (code "52") (name "Net-(LED30-A)") (class "Default")
      (node (ref "LED30") (pin "2") (pinfunction "A_2") (pintype "unspecified"))
      (node (ref "SW10") (pin "2") (pinfunction "2_2") (pintype "unspecified"))
    )
    (net (code "53") (name "Net-(LED30-K)") (class "Default")
      (node (ref "LED30") (pin "1") (pinfunction "K_1") (pintype "unspecified"))
      (node (ref "R44") (pin "1") (pinfunction "1_1") (pintype "input"))
    )
    (net (code "54") (name "Net-(LED31-K)") (class "Default")
      (node (ref "LED31") (pin "1") (pinfunction "K_1") (pintype "unspecified"))
      (node (ref "U23") (pin "3") (pinfunction "FAULT#_3") (pintype "unspecified"))
    )
    (net (code "55") (name "Net-(LED32-K)") (class "Default")
      (node (ref "LED32") (pin "1") (pinfunction "K_1") (pintype "unspecified"))
      (node (ref "U24") (pin "3") (pinfunction "FAULT#_3") (pintype "unspecified"))
    )
    (net (code "56") (name "Net-(LED33-A)") (class "Default")
      (node (ref "LED33") (pin "2") (pinfunction "A_2") (pintype "unspecified"))
      (node (ref "SW11") (pin "2") (pinfunction "2_2") (pintype "unspecified"))
    )
    (net (code "57") (name "Net-(LED33-K)") (class "Default")
      (node (ref "LED33") (pin "1") (pinfunction "K_1") (pintype "unspecified"))
      (node (ref "R46") (pin "1") (pinfunction "1_1") (pintype "input"))
    )
    (net (code "58") (name "Net-(LED34-A)") (class "Default")
      (node (ref "LED34") (pin "2") (pinfunction "A_2") (pintype "unspecified"))
      (node (ref "SW12") (pin "2") (pinfunction "2_2") (pintype "unspecified"))
    )
    (net (code "59") (name "Net-(LED34-K)") (class "Default")
      (node (ref "LED34") (pin "1") (pinfunction "K_1") (pintype "unspecified"))
      (node (ref "R48") (pin "1") (pinfunction "1_1") (pintype "input"))
    )
    (net (code "60") (name "Net-(LED35-K)") (class "Default")
      (node (ref "LED35") (pin "1") (pinfunction "K_1") (pintype "unspecified"))
      (node (ref "U25") (pin "3") (pinfunction "FAULT#_3") (pintype "unspecified"))
    )
    (net (code "61") (name "Net-(LED36-K)") (class "Default")
      (node (ref "LED36") (pin "1") (pinfunction "K_1") (pintype "unspecified"))
      (node (ref "U26") (pin "3") (pinfunction "FAULT#_3") (pintype "unspecified"))
    )
    (net (code "62") (name "Net-(LED37-A)") (class "Default")
      (node (ref "LED37") (pin "2") (pinfunction "A_2") (pintype "unspecified"))
      (node (ref "SW13") (pin "2") (pinfunction "2_2") (pintype "unspecified"))
    )
    (net (code "63") (name "Net-(LED37-K)") (class "Default")
      (node (ref "LED37") (pin "1") (pinfunction "K_1") (pintype "unspecified"))
      (node (ref "R50") (pin "1") (pinfunction "1_1") (pintype "input"))
    )
    (net (code "64") (name "Net-(LED38-A)") (class "Default")
      (node (ref "LED38") (pin "2") (pinfunction "A_2") (pintype "unspecified"))
      (node (ref "SW14") (pin "2") (pinfunction "2_2") (pintype "unspecified"))
    )
    (net (code "65") (name "Net-(LED38-K)") (class "Default")
      (node (ref "LED38") (pin "1") (pinfunction "K_1") (pintype "unspecified"))
      (node (ref "R52") (pin "1") (pinfunction "1_1") (pintype "input"))
    )
    (net (code "66") (name "Net-(LED39-K)") (class "Default")
      (node (ref "LED39") (pin "1") (pinfunction "K_1") (pintype "unspecified"))
      (node (ref "U27") (pin "3") (pinfunction "FAULT#_3") (pintype "unspecified"))
    )
    (net (code "67") (name "Net-(LED40-K)") (class "Default")
      (node (ref "LED40") (pin "1") (pinfunction "K_1") (pintype "unspecified"))
      (node (ref "U28") (pin "3") (pinfunction "FAULT#_3") (pintype "unspecified"))
    )
    (net (code "68") (name "Net-(LED41-A)") (class "Default")
      (node (ref "LED41") (pin "2") (pinfunction "A_2") (pintype "unspecified"))
      (node (ref "SW15") (pin "2") (pinfunction "2_2") (pintype "unspecified"))
    )
    (net (code "69") (name "Net-(LED41-K)") (class "Default")
      (node (ref "LED41") (pin "1") (pinfunction "K_1") (pintype "unspecified"))
      (node (ref "R54") (pin "1") (pinfunction "1_1") (pintype "input"))
    )
    (net (code "70") (name "Net-(LED42-A)") (class "Default")
      (node (ref "LED42") (pin "2") (pinfunction "A_2") (pintype "unspecified"))
      (node (ref "SW16") (pin "2") (pinfunction "2_2") (pintype "unspecified"))
    )
    (net (code "71") (name "Net-(LED42-K)") (class "Default")
      (node (ref "LED42") (pin "1") (pinfunction "K_1") (pintype "unspecified"))
      (node (ref "R56") (pin "1") (pinfunction "1_1") (pintype "input"))
    )
    (net (code "72") (name "Net-(LED43-K)") (class "Default")
      (node (ref "LED43") (pin "1") (pinfunction "K_1") (pintype "unspecified"))
      (node (ref "U29") (pin "3") (pinfunction "FAULT#_3") (pintype "unspecified"))
    )
    (net (code "73") (name "Net-(LED44-K)") (class "Default")
      (node (ref "LED44") (pin "1") (pinfunction "K_1") (pintype "unspecified"))
      (node (ref "U30") (pin "3") (pinfunction "FAULT#_3") (pintype "unspecified"))
    )
    (net (code "74") (name "Net-(LED45-A)") (class "Default")
      (node (ref "LED45") (pin "2") (pinfunction "A_2") (pintype "unspecified"))
      (node (ref "SW17") (pin "2") (pinfunction "2_2") (pintype "unspecified"))
    )
    (net (code "75") (name "Net-(LED45-K)") (class "Default")
      (node (ref "LED45") (pin "1") (pinfunction "K_1") (pintype "unspecified"))
      (node (ref "R58") (pin "1") (pinfunction "1_1") (pintype "input"))
    )
    (net (code "76") (name "Net-(LED46-A)") (class "Default")
      (node (ref "LED46") (pin "2") (pinfunction "A_2") (pintype "unspecified"))
      (node (ref "SW18") (pin "2") (pinfunction "2_2") (pintype "unspecified"))
    )
    (net (code "77") (name "Net-(LED46-K)") (class "Default")
      (node (ref "LED46") (pin "1") (pinfunction "K_1") (pintype "unspecified"))
      (node (ref "R60") (pin "1") (pinfunction "1_1") (pintype "input"))
    )
    (net (code "78") (name "Net-(LED47-K)") (class "Default")
      (node (ref "LED47") (pin "1") (pinfunction "K_1") (pintype "unspecified"))
      (node (ref "U31") (pin "3") (pinfunction "FAULT#_3") (pintype "unspecified"))
    )
    (net (code "79") (name "Net-(LED48-K)") (class "Default")
      (node (ref "LED48") (pin "1") (pinfunction "K_1") (pintype "unspecified"))
      (node (ref "U32") (pin "3") (pinfunction "FAULT#_3") (pintype "unspecified"))
    )
    (net (code "80") (name "Net-(LED49-A)") (class "Default")
      (node (ref "LED49") (pin "2") (pinfunction "A_2") (pintype "unspecified"))
      (node (ref "SW19") (pin "2") (pinfunction "2_2") (pintype "unspecified"))
    )
    (net (code "81") (name "Net-(LED49-K)") (class "Default")
      (node (ref "LED49") (pin "1") (pinfunction "K_1") (pintype "unspecified"))
      (node (ref "R62") (pin "1") (pinfunction "1_1") (pintype "input"))
    )
    (net (code "82") (name "Net-(LED50-A)") (class "Default")
      (node (ref "LED50") (pin "2") (pinfunction "A_2") (pintype "unspecified"))
      (node (ref "SW20") (pin "2") (pinfunction "2_2") (pintype "unspecified"))
    )
    (net (code "83") (name "Net-(LED50-K)") (class "Default")
      (node (ref "LED50") (pin "1") (pinfunction "K_1") (pintype "unspecified"))
      (node (ref "R64") (pin "1") (pinfunction "1_1") (pintype "input"))
    )
    (net (code "84") (name "Net-(LED51-K)") (class "Default")
      (node (ref "LED51") (pin "1") (pinfunction "K_1") (pintype "unspecified"))
      (node (ref "U33") (pin "3") (pinfunction "FAULT#_3") (pintype "unspecified"))
    )
    (net (code "85") (name "Net-(LED52-K)") (class "Default")
      (node (ref "LED52") (pin "1") (pinfunction "K_1") (pintype "unspecified"))
      (node (ref "U34") (pin "3") (pinfunction "FAULT#_3") (pintype "unspecified"))
    )
    (net (code "86") (name "Net-(LED53-A)") (class "Default")
      (node (ref "LED53") (pin "2") (pinfunction "A_2") (pintype "unspecified"))
      (node (ref "SW21") (pin "2") (pinfunction "2_2") (pintype "unspecified"))
    )
    (net (code "87") (name "Net-(LED53-K)") (class "Default")
      (node (ref "LED53") (pin "1") (pinfunction "K_1") (pintype "unspecified"))
      (node (ref "R66") (pin "1") (pinfunction "1_1") (pintype "input"))
    )
    (net (code "88") (name "Net-(LED54-A)") (class "Default")
      (node (ref "LED54") (pin "2") (pinfunction "A_2") (pintype "unspecified"))
      (node (ref "SW22") (pin "2") (pinfunction "2_2") (pintype "unspecified"))
    )
    (net (code "89") (name "Net-(LED54-K)") (class "Default")
      (node (ref "LED54") (pin "1") (pinfunction "K_1") (pintype "unspecified"))
      (node (ref "R68") (pin "1") (pinfunction "1_1") (pintype "input"))
    )
    (net (code "90") (name "Net-(LED55-K)") (class "Default")
      (node (ref "LED55") (pin "1") (pinfunction "K_1") (pintype "unspecified"))
      (node (ref "U35") (pin "3") (pinfunction "FAULT#_3") (pintype "unspecified"))
    )
    (net (code "91") (name "Net-(LED56-K)") (class "Default")
      (node (ref "LED56") (pin "1") (pinfunction "K_1") (pintype "unspecified"))
      (node (ref "U36") (pin "3") (pinfunction "FAULT#_3") (pintype "unspecified"))
    )
    (net (code "92") (name "Net-(LED57-A)") (class "Default")
      (node (ref "LED57") (pin "2") (pinfunction "A_2") (pintype "unspecified"))
      (node (ref "SW23") (pin "2") (pinfunction "2_2") (pintype "unspecified"))
    )
    (net (code "93") (name "Net-(LED57-K)") (class "Default")
      (node (ref "LED57") (pin "1") (pinfunction "K_1") (pintype "unspecified"))
      (node (ref "R70") (pin "1") (pinfunction "1_1") (pintype "input"))
    )
    (net (code "94") (name "Net-(LED58-A)") (class "Default")
      (node (ref "LED58") (pin "2") (pinfunction "A_2") (pintype "unspecified"))
      (node (ref "SW24") (pin "2") (pinfunction "2_2") (pintype "unspecified"))
    )
    (net (code "95") (name "Net-(LED58-K)") (class "Default")
      (node (ref "LED58") (pin "1") (pinfunction "K_1") (pintype "unspecified"))
      (node (ref "R72") (pin "1") (pinfunction "1_1") (pintype "input"))
    )
    (net (code "96") (name "Net-(LED59-K)") (class "Default")
      (node (ref "LED59") (pin "1") (pinfunction "K_1") (pintype "unspecified"))
      (node (ref "U37") (pin "3") (pinfunction "FAULT#_3") (pintype "unspecified"))
    )
    (net (code "97") (name "Net-(LED60-K)") (class "Default")
      (node (ref "LED60") (pin "1") (pinfunction "K_1") (pintype "unspecified"))
      (node (ref "U38") (pin "3") (pinfunction "FAULT#_3") (pintype "unspecified"))
    )
    (net (code "98") (name "Net-(LED61-A)") (class "Default")
      (node (ref "LED61") (pin "2") (pinfunction "A_2") (pintype "unspecified"))
      (node (ref "SW25") (pin "2") (pinfunction "2_2") (pintype "unspecified"))
    )
    (net (code "99") (name "Net-(LED61-K)") (class "Default")
      (node (ref "LED61") (pin "1") (pinfunction "K_1") (pintype "unspecified"))
      (node (ref "R74") (pin "1") (pinfunction "1_1") (pintype "input"))
    )
    (net (code "100") (name "Net-(LED62-A)") (class "Default")
      (node (ref "LED62") (pin "2") (pinfunction "A_2") (pintype "unspecified"))
      (node (ref "SW26") (pin "2") (pinfunction "2_2") (pintype "unspecified"))
    )
    (net (code "101") (name "Net-(LED62-K)") (class "Default")
      (node (ref "LED62") (pin "1") (pinfunction "K_1") (pintype "unspecified"))
      (node (ref "R76") (pin "1") (pinfunction "1_1") (pintype "input"))
    )
    (net (code "102") (name "Net-(Q1-Pad1)") (class "Default")
      (node (ref "Q1") (pin "1") (pinfunction "1_1") (pintype "input"))
      (node (ref "U4") (pin "3") (pinfunction "3_3") (pintype "unspecified"))
    )
    (net (code "103") (name "Net-(R4-Pad1)") (class "Default")
      (node (ref "R4") (pin "1") (pinfunction "1_1") (pintype "input"))
      (node (ref "U4") (pin "4") (pinfunction "4_4") (pintype "unspecified"))
    )
    (net (code "104") (name "Net-(R6-Pad1)") (class "Default")
      (node (ref "R6") (pin "1") (pinfunction "1_1") (pintype "input"))
      (node (ref "U4") (pin "1") (pinfunction "1_1") (pintype "unspecified"))
    )
    (net (code "105") (name "Net-(U1-FB)") (class "Default")
      (node (ref "C1") (pin "1") (pinfunction "1_1") (pintype "input"))
      (node (ref "R5") (pin "1") (pinfunction "1_1") (pintype "input"))
      (node (ref "R9") (pin "2") (pinfunction "2_2") (pintype "input"))
      (node (ref "U1") (pin "4") (pinfunction "FB_4") (pintype "unspecified"))
    )
    (net (code "106") (name "Net-(U2-CL)") (class "Default")
      (node (ref "R7") (pin "1") (pinfunction "1_1") (pintype "input"))
      (node (ref "U2") (pin "4") (pinfunction "CL_4") (pintype "unspecified"))
    )
    (net (code "107") (name "Net-(U2-DELAY)") (class "Default")
      (node (ref "C3") (pin "2") (pinfunction "2_2") (pintype "unspecified"))
      (node (ref "U2") (pin "5") (pinfunction "DELAY_5") (pintype "unspecified"))
    )
    (net (code "108") (name "Net-(U2-DIAG_EN)") (class "Default")
      (node (ref "R2") (pin "2") (pinfunction "2_2") (pintype "input"))
      (node (ref "R3") (pin "1") (pinfunction "1_1") (pintype "input"))
      (node (ref "U2") (pin "1") (pinfunction "IN_1") (pintype "unspecified"))
      (node (ref "U2") (pin "2") (pinfunction "DIAG_EN_2") (pintype "unspecified"))
    )
    (net (code "109") (name "Net-(U2-OUT)") (class "Default")
      (node (ref "CN1") (pin "1") (pinfunction "1_1") (pintype "unspecified"))
      (node (ref "U2") (pin "7") (pinfunction "OUT_7") (pintype "unspecified"))
    )
    (net (code "110") (name "Net-(U5-17(RX2))") (class "Default")
      (node (ref "R21") (pin "2") (pinfunction "2_2") (pintype "input"))
      (node (ref "R22") (pin "2") (pinfunction "2_2") (pintype "input"))
      (node (ref "U5") (pin "17") (pinfunction "17(RX2)_17") (pintype "unspecified"))
      (node (ref "U9") (pin "2") (pinfunction "RE_2") (pintype "unspecified"))
      (node (ref "U9") (pin "3") (pinfunction "DE_3") (pintype "unspecified"))
    )
    (net (code "111") (name "Net-(U5-18(TX1))") (class "Default")
      (node (ref "R20") (pin "2") (pinfunction "2_2") (pintype "input"))
      (node (ref "U5") (pin "18") (pinfunction "18(TX1)_18") (pintype "unspecified"))
      (node (ref "U9") (pin "4") (pinfunction "DI_4") (pintype "unspecified"))
    )
    (net (code "112") (name "Net-(U5-19(RX1))") (class "Default")
      (node (ref "R23") (pin "2") (pinfunction "2_2") (pintype "input"))
      (node (ref "U5") (pin "19") (pinfunction "19(RX1)_19") (pintype "unspecified"))
      (node (ref "U9") (pin "1") (pinfunction "RO_1") (pintype "unspecified"))
    )
    (net (code "113") (name "Net-(U6-CL)") (class "Default")
      (node (ref "R14") (pin "1") (pinfunction "1_1") (pintype "input"))
      (node (ref "U6") (pin "4") (pinfunction "CL_4") (pintype "unspecified"))
    )
    (net (code "114") (name "Net-(U6-DELAY)") (class "Default")
      (node (ref "C6") (pin "2") (pinfunction "2_2") (pintype "unspecified"))
      (node (ref "U6") (pin "5") (pinfunction "DELAY_5") (pintype "unspecified"))
    )
    (net (code "115") (name "Net-(U6-DIAG_EN)") (class "Default")
      (node (ref "R10") (pin "2") (pinfunction "2_2") (pintype "input"))
      (node (ref "R13") (pin "1") (pinfunction "1_1") (pintype "input"))
      (node (ref "U6") (pin "1") (pinfunction "IN_1") (pintype "unspecified"))
      (node (ref "U6") (pin "2") (pinfunction "DIAG_EN_2") (pintype "unspecified"))
    )
    (net (code "116") (name "Net-(U6-OUT)") (class "Default")
      (node (ref "CN3") (pin "1") (pinfunction "1_1") (pintype "unspecified"))
      (node (ref "U6") (pin "7") (pinfunction "OUT_7") (pintype "unspecified"))
    )
    (net (code "117") (name "Net-(U7-CL)") (class "Default")
      (node (ref "R18") (pin "1") (pinfunction "1_1") (pintype "input"))
      (node (ref "U7") (pin "4") (pinfunction "CL_4") (pintype "unspecified"))
    )
    (net (code "118") (name "Net-(U7-DELAY)") (class "Default")
      (node (ref "C7") (pin "2") (pinfunction "2_2") (pintype "unspecified"))
      (node (ref "U7") (pin "5") (pinfunction "DELAY_5") (pintype "unspecified"))
    )
    (net (code "119") (name "Net-(U7-DIAG_EN)") (class "Default")
      (node (ref "R15") (pin "2") (pinfunction "2_2") (pintype "input"))
      (node (ref "R16") (pin "1") (pinfunction "1_1") (pintype "input"))
      (node (ref "U7") (pin "1") (pinfunction "IN_1") (pintype "unspecified"))
      (node (ref "U7") (pin "2") (pinfunction "DIAG_EN_2") (pintype "unspecified"))
    )
    (net (code "120") (name "Net-(U7-OUT)") (class "Default")
      (node (ref "CN5") (pin "1") (pinfunction "1_1") (pintype "unspecified"))
      (node (ref "U7") (pin "7") (pinfunction "OUT_7") (pintype "unspecified"))
    )
    (net (code "121") (name "Net-(U9-A)") (class "Default")
      (node (ref "R19") (pin "2") (pinfunction "2_2") (pintype "input"))
      (node (ref "U8") (pin "1") (pinfunction "1_1") (pintype "input"))
      (node (ref "U9") (pin "6") (pinfunction "A_6") (pintype "unspecified"))
    )
    (net (code "122") (name "Net-(U9-B)") (class "Default")
      (node (ref "R17") (pin "2") (pinfunction "2_2") (pintype "input"))
      (node (ref "U8") (pin "2") (pinfunction "2_2") (pintype "input"))
      (node (ref "U9") (pin "7") (pinfunction "B_7") (pintype "unspecified"))
    )
    (net (code "123") (name "Net-(U10-CL)") (class "Default")
      (node (ref "R28") (pin "1") (pinfunction "1_1") (pintype "input"))
      (node (ref "U10") (pin "4") (pinfunction "CL_4") (pintype "unspecified"))
    )
    (net (code "124") (name "Net-(U10-DELAY)") (class "Default")
      (node (ref "C10") (pin "2") (pinfunction "2_2") (pintype "unspecified"))
      (node (ref "U10") (pin "5") (pinfunction "DELAY_5") (pintype "unspecified"))
    )
    (net (code "125") (name "Net-(U10-DIAG_EN)") (class "Default")
      (node (ref "R24") (pin "2") (pinfunction "2_2") (pintype "input"))
      (node (ref "R25") (pin "1") (pinfunction "1_1") (pintype "input"))
      (node (ref "U10") (pin "1") (pinfunction "IN_1") (pintype "unspecified"))
      (node (ref "U10") (pin "2") (pinfunction "DIAG_EN_2") (pintype "unspecified"))
    )
    (net (code "126") (name "Net-(U10-OUT)") (class "Default")
      (node (ref "CN6") (pin "1") (pinfunction "1_1") (pintype "unspecified"))
      (node (ref "U10") (pin "7") (pinfunction "OUT_7") (pintype "unspecified"))
    )
    (net (code "127") (name "Net-(U11-IN+)") (class "Default")
      (node (ref "C12") (pin "2") (pinfunction "2_2") (pintype "unspecified"))
      (node (ref "R34") (pin "2") (pinfunction "2_2") (pintype "input"))
      (node (ref "U11") (pin "1") (pinfunction "IN+_1") (pintype "input"))
    )
    (net (code "128") (name "Net-(U11-IN-)") (class "Default")
      (node (ref "C11") (pin "2") (pinfunction "2_2") (pintype "unspecified"))
      (node (ref "R29") (pin "1") (pinfunction "1_1") (pintype "input"))
      (node (ref "R33") (pin "2") (pinfunction "2_2") (pintype "input"))
      (node (ref "U11") (pin "3") (pinfunction "IN-_3") (pintype "input"))
    )
    (net (code "129") (name "Net-(U12-IN+)") (class "Default")
      (node (ref "C14") (pin "2") (pinfunction "2_2") (pintype "unspecified"))
      (node (ref "R36") (pin "2") (pinfunction "2_2") (pintype "input"))
      (node (ref "U12") (pin "1") (pinfunction "IN+_1") (pintype "input"))
    )
    (net (code "130") (name "Net-(U12-IN-)") (class "Default")
      (node (ref "C13") (pin "2") (pinfunction "2_2") (pintype "unspecified"))
      (node (ref "R30") (pin "1") (pinfunction "1_1") (pintype "input"))
      (node (ref "R35") (pin "2") (pinfunction "2_2") (pintype "input"))
      (node (ref "U12") (pin "3") (pinfunction "IN-_3") (pintype "input"))
    )
    (net (code "131") (name "Net-(U19-CL)") (class "Default")
      (node (ref "R86") (pin "1") (pinfunction "1_1") (pintype "input"))
      (node (ref "U19") (pin "4") (pinfunction "CL_4") (pintype "unspecified"))
    )
    (net (code "132") (name "Net-(U19-DELAY)") (class "Default")
      (node (ref "C20") (pin "2") (pinfunction "2_2") (pintype "unspecified"))
      (node (ref "U19") (pin "5") (pinfunction "DELAY_5") (pintype "unspecified"))
    )
    (net (code "133") (name "Net-(U19-DIAG_EN)") (class "Default")
      (node (ref "R37") (pin "1") (pinfunction "1_1") (pintype "input"))
      (node (ref "R38") (pin "2") (pinfunction "2_2") (pintype "input"))
      (node (ref "U19") (pin "1") (pinfunction "IN_1") (pintype "unspecified"))
      (node (ref "U19") (pin "2") (pinfunction "DIAG_EN_2") (pintype "unspecified"))
    )
    (net (code "134") (name "Net-(U19-OUT)") (class "Default")
      (node (ref "CN11") (pin "1") (pinfunction "1_1") (pintype "unspecified"))
      (node (ref "U19") (pin "7") (pinfunction "OUT_7") (pintype "unspecified"))
    )
    (net (code "135") (name "Net-(U20-CL)") (class "Default")
      (node (ref "R87") (pin "1") (pinfunction "1_1") (pintype "input"))
      (node (ref "U20") (pin "4") (pinfunction "CL_4") (pintype "unspecified"))
    )
    (net (code "136") (name "Net-(U20-DELAY)") (class "Default")
      (node (ref "C21") (pin "2") (pinfunction "2_2") (pintype "unspecified"))
      (node (ref "U20") (pin "5") (pinfunction "DELAY_5") (pintype "unspecified"))
    )
    (net (code "137") (name "Net-(U20-DIAG_EN)") (class "Default")
      (node (ref "R39") (pin "1") (pinfunction "1_1") (pintype "input"))
      (node (ref "R40") (pin "2") (pinfunction "2_2") (pintype "input"))
      (node (ref "U20") (pin "1") (pinfunction "IN_1") (pintype "unspecified"))
      (node (ref "U20") (pin "2") (pinfunction "DIAG_EN_2") (pintype "unspecified"))
    )
    (net (code "138") (name "Net-(U20-OUT)") (class "Default")
      (node (ref "CN12") (pin "1") (pinfunction "1_1") (pintype "unspecified"))
      (node (ref "U20") (pin "7") (pinfunction "OUT_7") (pintype "unspecified"))
    )
    (net (code "139") (name "Net-(U21-CL)") (class "Default")
      (node (ref "R81") (pin "1") (pinfunction "1_1") (pintype "input"))
      (node (ref "U21") (pin "4") (pinfunction "CL_4") (pintype "unspecified"))
    )
    (net (code "140") (name "Net-(U21-DELAY)") (class "Default")
      (node (ref "C15") (pin "2") (pinfunction "2_2") (pintype "unspecified"))
      (node (ref "U21") (pin "5") (pinfunction "DELAY_5") (pintype "unspecified"))
    )
    (net (code "141") (name "Net-(U21-DIAG_EN)") (class "Default")
      (node (ref "R41") (pin "1") (pinfunction "1_1") (pintype "input"))
      (node (ref "R42") (pin "2") (pinfunction "2_2") (pintype "input"))
      (node (ref "U21") (pin "1") (pinfunction "IN_1") (pintype "unspecified"))
      (node (ref "U21") (pin "2") (pinfunction "DIAG_EN_2") (pintype "unspecified"))
    )
    (net (code "142") (name "Net-(U21-OUT)") (class "Default")
      (node (ref "CN13") (pin "1") (pinfunction "1_1") (pintype "unspecified"))
      (node (ref "U21") (pin "7") (pinfunction "OUT_7") (pintype "unspecified"))
    )
    (net (code "143") (name "Net-(U22-CL)") (class "Default")
      (node (ref "R82") (pin "1") (pinfunction "1_1") (pintype "input"))
      (node (ref "U22") (pin "4") (pinfunction "CL_4") (pintype "unspecified"))
    )
    (net (code "144") (name "Net-(U22-DELAY)") (class "Default")
      (node (ref "C16") (pin "2") (pinfunction "2_2") (pintype "unspecified"))
      (node (ref "U22") (pin "5") (pinfunction "DELAY_5") (pintype "unspecified"))
    )
    (net (code "145") (name "Net-(U22-DIAG_EN)") (class "Default")
      (node (ref "R43") (pin "1") (pinfunction "1_1") (pintype "input"))
      (node (ref "R44") (pin "2") (pinfunction "2_2") (pintype "input"))
      (node (ref "U22") (pin "1") (pinfunction "IN_1") (pintype "unspecified"))
      (node (ref "U22") (pin "2") (pinfunction "DIAG_EN_2") (pintype "unspecified"))
    )
    (net (code "146") (name "Net-(U22-OUT)") (class "Default")
      (node (ref "CN14") (pin "1") (pinfunction "1_1") (pintype "unspecified"))
      (node (ref "U22") (pin "7") (pinfunction "OUT_7") (pintype "unspecified"))
    )
    (net (code "147") (name "Net-(U23-CL)") (class "Default")
      (node (ref "R88") (pin "1") (pinfunction "1_1") (pintype "input"))
      (node (ref "U23") (pin "4") (pinfunction "CL_4") (pintype "unspecified"))
    )
    (net (code "148") (name "Net-(U23-DELAY)") (class "Default")
      (node (ref "C22") (pin "2") (pinfunction "2_2") (pintype "unspecified"))
      (node (ref "U23") (pin "5") (pinfunction "DELAY_5") (pintype "unspecified"))
    )
    (net (code "149") (name "Net-(U23-DIAG_EN)") (class "Default")
      (node (ref "R45") (pin "1") (pinfunction "1_1") (pintype "input"))
      (node (ref "R46") (pin "2") (pinfunction "2_2") (pintype "input"))
      (node (ref "U23") (pin "1") (pinfunction "IN_1") (pintype "unspecified"))
      (node (ref "U23") (pin "2") (pinfunction "DIAG_EN_2") (pintype "unspecified"))
    )
    (net (code "150") (name "Net-(U23-OUT)") (class "Default")
      (node (ref "CN15") (pin "1") (pinfunction "1_1") (pintype "unspecified"))
      (node (ref "U23") (pin "7") (pinfunction "OUT_7") (pintype "unspecified"))
    )
    (net (code "151") (name "Net-(U24-CL)") (class "Default")
      (node (ref "R89") (pin "1") (pinfunction "1_1") (pintype "input"))
      (node (ref "U24") (pin "4") (pinfunction "CL_4") (pintype "unspecified"))
    )
    (net (code "152") (name "Net-(U24-DELAY)") (class "Default")
      (node (ref "C23") (pin "2") (pinfunction "2_2") (pintype "unspecified"))
      (node (ref "U24") (pin "5") (pinfunction "DELAY_5") (pintype "unspecified"))
    )
    (net (code "153") (name "Net-(U24-DIAG_EN)") (class "Default")
      (node (ref "R47") (pin "1") (pinfunction "1_1") (pintype "input"))
      (node (ref "R48") (pin "2") (pinfunction "2_2") (pintype "input"))
      (node (ref "U24") (pin "1") (pinfunction "IN_1") (pintype "unspecified"))
      (node (ref "U24") (pin "2") (pinfunction "DIAG_EN_2") (pintype "unspecified"))
    )
    (net (code "154") (name "Net-(U24-OUT)") (class "Default")
      (node (ref "CN16") (pin "1") (pinfunction "1_1") (pintype "unspecified"))
      (node (ref "U24") (pin "7") (pinfunction "OUT_7") (pintype "unspecified"))
    )
    (net (code "155") (name "Net-(U25-CL)") (class "Default")
      (node (ref "R85") (pin "1") (pinfunction "1_1") (pintype "input"))
      (node (ref "U25") (pin "4") (pinfunction "CL_4") (pintype "unspecified"))
    )
    (net (code "156") (name "Net-(U25-DELAY)") (class "Default")
      (node (ref "C19") (pin "2") (pinfunction "2_2") (pintype "unspecified"))
      (node (ref "U25") (pin "5") (pinfunction "DELAY_5") (pintype "unspecified"))
    )
    (net (code "157") (name "Net-(U25-DIAG_EN)") (class "Default")
      (node (ref "R49") (pin "1") (pinfunction "1_1") (pintype "input"))
      (node (ref "R50") (pin "2") (pinfunction "2_2") (pintype "input"))
      (node (ref "U25") (pin "1") (pinfunction "IN_1") (pintype "unspecified"))
      (node (ref "U25") (pin "2") (pinfunction "DIAG_EN_2") (pintype "unspecified"))
    )
    (net (code "158") (name "Net-(U25-OUT)") (class "Default")
      (node (ref "CN17") (pin "1") (pinfunction "1_1") (pintype "unspecified"))
      (node (ref "U25") (pin "7") (pinfunction "OUT_7") (pintype "unspecified"))
    )
    (net (code "159") (name "Net-(U26-CL)") (class "Default")
      (node (ref "R84") (pin "1") (pinfunction "1_1") (pintype "input"))
      (node (ref "U26") (pin "4") (pinfunction "CL_4") (pintype "unspecified"))
    )
    (net (code "160") (name "Net-(U26-DELAY)") (class "Default")
      (node (ref "C18") (pin "2") (pinfunction "2_2") (pintype "unspecified"))
      (node (ref "U26") (pin "5") (pinfunction "DELAY_5") (pintype "unspecified"))
    )
    (net (code "161") (name "Net-(U26-DIAG_EN)") (class "Default")
      (node (ref "R51") (pin "1") (pinfunction "1_1") (pintype "input"))
      (node (ref "R52") (pin "2") (pinfunction "2_2") (pintype "input"))
      (node (ref "U26") (pin "1") (pinfunction "IN_1") (pintype "unspecified"))
      (node (ref "U26") (pin "2") (pinfunction "DIAG_EN_2") (pintype "unspecified"))
    )
    (net (code "162") (name "Net-(U26-OUT)") (class "Default")
      (node (ref "CN18") (pin "1") (pinfunction "1_1") (pintype "unspecified"))
      (node (ref "U26") (pin "7") (pinfunction "OUT_7") (pintype "unspecified"))
    )
    (net (code "163") (name "Net-(U27-CL)") (class "Default")
      (node (ref "R90") (pin "1") (pinfunction "1_1") (pintype "input"))
      (node (ref "U27") (pin "4") (pinfunction "CL_4") (pintype "unspecified"))
    )
    (net (code "164") (name "Net-(U27-DELAY)") (class "Default")
      (node (ref "C24") (pin "2") (pinfunction "2_2") (pintype "unspecified"))
      (node (ref "U27") (pin "5") (pinfunction "DELAY_5") (pintype "unspecified"))
    )
    (net (code "165") (name "Net-(U27-DIAG_EN)") (class "Default")
      (node (ref "R53") (pin "1") (pinfunction "1_1") (pintype "input"))
      (node (ref "R54") (pin "2") (pinfunction "2_2") (pintype "input"))
      (node (ref "U27") (pin "1") (pinfunction "IN_1") (pintype "unspecified"))
      (node (ref "U27") (pin "2") (pinfunction "DIAG_EN_2") (pintype "unspecified"))
    )
    (net (code "166") (name "Net-(U27-OUT)") (class "Default")
      (node (ref "CN19") (pin "1") (pinfunction "1_1") (pintype "unspecified"))
      (node (ref "U27") (pin "7") (pinfunction "OUT_7") (pintype "unspecified"))
    )
    (net (code "167") (name "Net-(U28-CL)") (class "Default")
      (node (ref "R91") (pin "1") (pinfunction "1_1") (pintype "input"))
      (node (ref "U28") (pin "4") (pinfunction "CL_4") (pintype "unspecified"))
    )
    (net (code "168") (name "Net-(U28-DELAY)") (class "Default")
      (node (ref "C25") (pin "2") (pinfunction "2_2") (pintype "unspecified"))
      (node (ref "U28") (pin "5") (pinfunction "DELAY_5") (pintype "unspecified"))
    )
    (net (code "169") (name "Net-(U28-DIAG_EN)") (class "Default")
      (node (ref "R55") (pin "1") (pinfunction "1_1") (pintype "input"))
      (node (ref "R56") (pin "2") (pinfunction "2_2") (pintype "input"))
      (node (ref "U28") (pin "1") (pinfunction "IN_1") (pintype "unspecified"))
      (node (ref "U28") (pin "2") (pinfunction "DIAG_EN_2") (pintype "unspecified"))
    )
    (net (code "170") (name "Net-(U28-OUT)") (class "Default")
      (node (ref "CN20") (pin "1") (pinfunction "1_1") (pintype "unspecified"))
      (node (ref "U28") (pin "7") (pinfunction "OUT_7") (pintype "unspecified"))
    )
    (net (code "171") (name "Net-(U29-CL)") (class "Default")
      (node (ref "R92") (pin "1") (pinfunction "1_1") (pintype "input"))
      (node (ref "U29") (pin "4") (pinfunction "CL_4") (pintype "unspecified"))
    )
    (net (code "172") (name "Net-(U29-DELAY)") (class "Default")
      (node (ref "C26") (pin "2") (pinfunction "2_2") (pintype "unspecified"))
      (node (ref "U29") (pin "5") (pinfunction "DELAY_5") (pintype "unspecified"))
    )
    (net (code "173") (name "Net-(U29-DIAG_EN)") (class "Default")
      (node (ref "R57") (pin "1") (pinfunction "1_1") (pintype "input"))
      (node (ref "R58") (pin "2") (pinfunction "2_2") (pintype "input"))
      (node (ref "U29") (pin "1") (pinfunction "IN_1") (pintype "unspecified"))
      (node (ref "U29") (pin "2") (pinfunction "DIAG_EN_2") (pintype "unspecified"))
    )
    (net (code "174") (name "Net-(U29-OUT)") (class "Default")
      (node (ref "CN21") (pin "1") (pinfunction "1_1") (pintype "unspecified"))
      (node (ref "U29") (pin "7") (pinfunction "OUT_7") (pintype "unspecified"))
    )
    (net (code "175") (name "Net-(U30-CL)") (class "Default")
      (node (ref "R93") (pin "1") (pinfunction "1_1") (pintype "input"))
      (node (ref "U30") (pin "4") (pinfunction "CL_4") (pintype "unspecified"))
    )
    (net (code "176") (name "Net-(U30-DELAY)") (class "Default")
      (node (ref "C27") (pin "2") (pinfunction "2_2") (pintype "unspecified"))
      (node (ref "U30") (pin "5") (pinfunction "DELAY_5") (pintype "unspecified"))
    )
    (net (code "177") (name "Net-(U30-DIAG_EN)") (class "Default")
      (node (ref "R59") (pin "1") (pinfunction "1_1") (pintype "input"))
      (node (ref "R60") (pin "2") (pinfunction "2_2") (pintype "input"))
      (node (ref "U30") (pin "1") (pinfunction "IN_1") (pintype "unspecified"))
      (node (ref "U30") (pin "2") (pinfunction "DIAG_EN_2") (pintype "unspecified"))
    )
    (net (code "178") (name "Net-(U30-OUT)") (class "Default")
      (node (ref "CN22") (pin "1") (pinfunction "1_1") (pintype "unspecified"))
      (node (ref "U30") (pin "7") (pinfunction "OUT_7") (pintype "unspecified"))
    )
    (net (code "179") (name "Net-(U31-CL)") (class "Default")
      (node (ref "R98") (pin "1") (pinfunction "1_1") (pintype "input"))
      (node (ref "U31") (pin "4") (pinfunction "CL_4") (pintype "unspecified"))
    )
    (net (code "180") (name "Net-(U31-DELAY)") (class "Default")
      (node (ref "C32") (pin "2") (pinfunction "2_2") (pintype "unspecified"))
      (node (ref "U31") (pin "5") (pinfunction "DELAY_5") (pintype "unspecified"))
    )
    (net (code "181") (name "Net-(U31-DIAG_EN)") (class "Default")
      (node (ref "R61") (pin "1") (pinfunction "1_1") (pintype "input"))
      (node (ref "R62") (pin "2") (pinfunction "2_2") (pintype "input"))
      (node (ref "U31") (pin "1") (pinfunction "IN_1") (pintype "unspecified"))
      (node (ref "U31") (pin "2") (pinfunction "DIAG_EN_2") (pintype "unspecified"))
    )
    (net (code "182") (name "Net-(U31-OUT)") (class "Default")
      (node (ref "CN23") (pin "1") (pinfunction "1_1") (pintype "unspecified"))
      (node (ref "U31") (pin "7") (pinfunction "OUT_7") (pintype "unspecified"))
    )
    (net (code "183") (name "Net-(U32-CL)") (class "Default")
      (node (ref "R99") (pin "1") (pinfunction "1_1") (pintype "input"))
      (node (ref "U32") (pin "4") (pinfunction "CL_4") (pintype "unspecified"))
    )
    (net (code "184") (name "Net-(U32-DELAY)") (class "Default")
      (node (ref "C33") (pin "2") (pinfunction "2_2") (pintype "unspecified"))
      (node (ref "U32") (pin "5") (pinfunction "DELAY_5") (pintype "unspecified"))
    )
    (net (code "185") (name "Net-(U32-DIAG_EN)") (class "Default")
      (node (ref "R63") (pin "1") (pinfunction "1_1") (pintype "input"))
      (node (ref "R64") (pin "2") (pinfunction "2_2") (pintype "input"))
      (node (ref "U32") (pin "1") (pinfunction "IN_1") (pintype "unspecified"))
      (node (ref "U32") (pin "2") (pinfunction "DIAG_EN_2") (pintype "unspecified"))
    )
    (net (code "186") (name "Net-(U32-OUT)") (class "Default")
      (node (ref "CN24") (pin "1") (pinfunction "1_1") (pintype "unspecified"))
      (node (ref "U32") (pin "7") (pinfunction "OUT_7") (pintype "unspecified"))
    )
    (net (code "187") (name "Net-(U33-CL)") (class "Default")
      (node (ref "R94") (pin "1") (pinfunction "1_1") (pintype "input"))
      (node (ref "U33") (pin "4") (pinfunction "CL_4") (pintype "unspecified"))
    )
    (net (code "188") (name "Net-(U33-DELAY)") (class "Default")
      (node (ref "C28") (pin "2") (pinfunction "2_2") (pintype "unspecified"))
      (node (ref "U33") (pin "5") (pinfunction "DELAY_5") (pintype "unspecified"))
    )
    (net (code "189") (name "Net-(U33-DIAG_EN)") (class "Default")
      (node (ref "R65") (pin "1") (pinfunction "1_1") (pintype "input"))
      (node (ref "R66") (pin "2") (pinfunction "2_2") (pintype "input"))
      (node (ref "U33") (pin "1") (pinfunction "IN_1") (pintype "unspecified"))
      (node (ref "U33") (pin "2") (pinfunction "DIAG_EN_2") (pintype "unspecified"))
    )
    (net (code "190") (name "Net-(U33-OUT)") (class "Default")
      (node (ref "CN25") (pin "1") (pinfunction "1_1") (pintype "unspecified"))
      (node (ref "U33") (pin "7") (pinfunction "OUT_7") (pintype "unspecified"))
    )
    (net (code "191") (name "Net-(U34-CL)") (class "Default")
      (node (ref "R95") (pin "1") (pinfunction "1_1") (pintype "input"))
      (node (ref "U34") (pin "4") (pinfunction "CL_4") (pintype "unspecified"))
    )
    (net (code "192") (name "Net-(U34-DELAY)") (class "Default")
      (node (ref "C29") (pin "2") (pinfunction "2_2") (pintype "unspecified"))
      (node (ref "U34") (pin "5") (pinfunction "DELAY_5") (pintype "unspecified"))
    )
    (net (code "193") (name "Net-(U34-DIAG_EN)") (class "Default")
      (node (ref "R67") (pin "1") (pinfunction "1_1") (pintype "input"))
      (node (ref "R68") (pin "2") (pinfunction "2_2") (pintype "input"))
      (node (ref "U34") (pin "1") (pinfunction "IN_1") (pintype "unspecified"))
      (node (ref "U34") (pin "2") (pinfunction "DIAG_EN_2") (pintype "unspecified"))
    )
    (net (code "194") (name "Net-(U34-OUT)") (class "Default")
      (node (ref "CN26") (pin "1") (pinfunction "1_1") (pintype "unspecified"))
      (node (ref "U34") (pin "7") (pinfunction "OUT_7") (pintype "unspecified"))
    )
    (net (code "195") (name "Net-(U35-CL)") (class "Default")
      (node (ref "R100") (pin "1") (pinfunction "1_1") (pintype "input"))
      (node (ref "U35") (pin "4") (pinfunction "CL_4") (pintype "unspecified"))
    )
    (net (code "196") (name "Net-(U35-DELAY)") (class "Default")
      (node (ref "C34") (pin "2") (pinfunction "2_2") (pintype "unspecified"))
      (node (ref "U35") (pin "5") (pinfunction "DELAY_5") (pintype "unspecified"))
    )
    (net (code "197") (name "Net-(U35-DIAG_EN)") (class "Default")
      (node (ref "R69") (pin "1") (pinfunction "1_1") (pintype "input"))
      (node (ref "R70") (pin "2") (pinfunction "2_2") (pintype "input"))
      (node (ref "U35") (pin "1") (pinfunction "IN_1") (pintype "unspecified"))
      (node (ref "U35") (pin "2") (pinfunction "DIAG_EN_2") (pintype "unspecified"))
    )
    (net (code "198") (name "Net-(U35-OUT)") (class "Default")
      (node (ref "CN27") (pin "1") (pinfunction "1_1") (pintype "unspecified"))
      (node (ref "U35") (pin "7") (pinfunction "OUT_7") (pintype "unspecified"))
    )
    (net (code "199") (name "Net-(U36-CL)") (class "Default")
      (node (ref "R101") (pin "1") (pinfunction "1_1") (pintype "input"))
      (node (ref "U36") (pin "4") (pinfunction "CL_4") (pintype "unspecified"))
    )
    (net (code "200") (name "Net-(U36-DELAY)") (class "Default")
      (node (ref "C35") (pin "2") (pinfunction "2_2") (pintype "unspecified"))
      (node (ref "U36") (pin "5") (pinfunction "DELAY_5") (pintype "unspecified"))
    )
    (net (code "201") (name "Net-(U36-DIAG_EN)") (class "Default")
      (node (ref "R71") (pin "1") (pinfunction "1_1") (pintype "input"))
      (node (ref "R72") (pin "2") (pinfunction "2_2") (pintype "input"))
      (node (ref "U36") (pin "1") (pinfunction "IN_1") (pintype "unspecified"))
      (node (ref "U36") (pin "2") (pinfunction "DIAG_EN_2") (pintype "unspecified"))
    )
    (net (code "202") (name "Net-(U36-OUT)") (class "Default")
      (node (ref "CN28") (pin "1") (pinfunction "1_1") (pintype "unspecified"))
      (node (ref "U36") (pin "7") (pinfunction "OUT_7") (pintype "unspecified"))
    )
    (net (code "203") (name "Net-(U37-CL)") (class "Default")
      (node (ref "R96") (pin "1") (pinfunction "1_1") (pintype "input"))
      (node (ref "U37") (pin "4") (pinfunction "CL_4") (pintype "unspecified"))
    )
    (net (code "204") (name "Net-(U37-DELAY)") (class "Default")
      (node (ref "C30") (pin "2") (pinfunction "2_2") (pintype "unspecified"))
      (node (ref "U37") (pin "5") (pinfunction "DELAY_5") (pintype "unspecified"))
    )
    (net (code "205") (name "Net-(U37-DIAG_EN)") (class "Default")
      (node (ref "R73") (pin "1") (pinfunction "1_1") (pintype "input"))
      (node (ref "R74") (pin "2") (pinfunction "2_2") (pintype "input"))
      (node (ref "U37") (pin "1") (pinfunction "IN_1") (pintype "unspecified"))
      (node (ref "U37") (pin "2") (pinfunction "DIAG_EN_2") (pintype "unspecified"))
    )
    (net (code "206") (name "Net-(U37-OUT)") (class "Default")
      (node (ref "CN29") (pin "1") (pinfunction "1_1") (pintype "unspecified"))
      (node (ref "U37") (pin "7") (pinfunction "OUT_7") (pintype "unspecified"))
    )
    (net (code "207") (name "Net-(U38-CL)") (class "Default")
      (node (ref "R97") (pin "1") (pinfunction "1_1") (pintype "input"))
      (node (ref "U38") (pin "4") (pinfunction "CL_4") (pintype "unspecified"))
    )
    (net (code "208") (name "Net-(U38-DELAY)") (class "Default")
      (node (ref "C31") (pin "2") (pinfunction "2_2") (pintype "unspecified"))
      (node (ref "U38") (pin "5") (pinfunction "DELAY_5") (pintype "unspecified"))
    )
    (net (code "209") (name "Net-(U38-DIAG_EN)") (class "Default")
      (node (ref "R75") (pin "1") (pinfunction "1_1") (pintype "input"))
      (node (ref "R76") (pin "2") (pinfunction "2_2") (pintype "input"))
      (node (ref "U38") (pin "1") (pinfunction "IN_1") (pintype "unspecified"))
      (node (ref "U38") (pin "2") (pinfunction "DIAG_EN_2") (pintype "unspecified"))
    )
    (net (code "210") (name "Net-(U38-OUT)") (class "Default")
      (node (ref "CN30") (pin "1") (pinfunction "1_1") (pintype "unspecified"))
      (node (ref "U38") (pin "7") (pinfunction "OUT_7") (pintype "unspecified"))
    )
    (net (code "211") (name "RINSER") (class "Default")
      (node (ref "R71") (pin "2") (pinfunction "2_2") (pintype "input"))
      (node (ref "U5") (pin "49") (pinfunction "49_49") (pintype "unspecified"))
    )
    (net (code "212") (name "SAUCE1") (class "Default")
      (node (ref "R37") (pin "2") (pinfunction "2_2") (pintype "input"))
      (node (ref "U5") (pin "10") (pinfunction "10_10") (pintype "unspecified"))
    )
    (net (code "213") (name "SAUCE2") (class "Default")
      (node (ref "R39") (pin "2") (pinfunction "2_2") (pintype "input"))
      (node (ref "U5") (pin "11") (pinfunction "11_11") (pintype "unspecified"))
    )
    (net (code "214") (name "SAUCE3") (class "Default")
      (node (ref "R45") (pin "2") (pinfunction "2_2") (pintype "input"))
      (node (ref "U5") (pin "12") (pinfunction "12_12") (pintype "unspecified"))
    )
    (net (code "215") (name "SAUCE4") (class "Default")
      (node (ref "R47") (pin "2") (pinfunction "2_2") (pintype "input"))
      (node (ref "U5") (pin "25") (pinfunction "25_25") (pintype "unspecified"))
    )
    (net (code "216") (name "SAUCE5") (class "Default")
      (node (ref "R53") (pin "2") (pinfunction "2_2") (pintype "input"))
      (node (ref "U5") (pin "27") (pinfunction "27_27") (pintype "unspecified"))
    )
    (net (code "217") (name "SAUCE6") (class "Default")
      (node (ref "R55") (pin "2") (pinfunction "2_2") (pintype "input"))
      (node (ref "U5") (pin "29") (pinfunction "29_29") (pintype "unspecified"))
    )
    (net (code "218") (name "SAUCE7") (class "Default")
      (node (ref "R57") (pin "2") (pinfunction "2_2") (pintype "input"))
      (node (ref "U5") (pin "31") (pinfunction "31_31") (pintype "unspecified"))
    )
    (net (code "219") (name "SAUCE8") (class "Default")
      (node (ref "R59") (pin "2") (pinfunction "2_2") (pintype "input"))
      (node (ref "U5") (pin "33") (pinfunction "33_33") (pintype "unspecified"))
    )
    (net (code "220") (name "SAUCE9") (class "Default")
      (node (ref "R65") (pin "2") (pinfunction "2_2") (pintype "input"))
      (node (ref "U5") (pin "35") (pinfunction "35_35") (pintype "unspecified"))
    )
    (net (code "221") (name "SAUCE10") (class "Default")
      (node (ref "R67") (pin "2") (pinfunction "2_2") (pintype "input"))
      (node (ref "U5") (pin "37") (pinfunction "37_37") (pintype "unspecified"))
    )
    (net (code "222") (name "SAUCE11") (class "Default")
      (node (ref "R73") (pin "2") (pinfunction "2_2") (pintype "input"))
      (node (ref "U5") (pin "39") (pinfunction "39_39") (pintype "unspecified"))
    )
    (net (code "223") (name "SAUCE12") (class "Default")
      (node (ref "R75") (pin "2") (pinfunction "2_2") (pintype "input"))
      (node (ref "U5") (pin "41") (pinfunction "41_41") (pintype "unspecified"))
    )
    (net (code "224") (name "SAUCE13") (class "Default")
      (node (ref "R61") (pin "2") (pinfunction "2_2") (pintype "input"))
      (node (ref "U5") (pin "43") (pinfunction "43_43") (pintype "unspecified"))
    )
    (net (code "225") (name "SAUCE14") (class "Default")
      (node (ref "R63") (pin "2") (pinfunction "2_2") (pintype "input"))
      (node (ref "U5") (pin "45") (pinfunction "45_45") (pintype "unspecified"))
    )
    (net (code "226") (name "SAUCE15") (class "Default")
      (node (ref "R69") (pin "2") (pinfunction "2_2") (pintype "input"))
      (node (ref "U5") (pin "47") (pinfunction "47_47") (pintype "unspecified"))
    )
    (net (code "227") (name "SCL") (class "Default")
      (node (ref "CN2") (pin "2") (pinfunction "2_2") (pintype "unspecified"))
      (node (ref "CN4") (pin "2") (pinfunction "2_2") (pintype "unspecified"))
      (node (ref "R12") (pin "2") (pinfunction "2_2") (pintype "input"))
      (node (ref "U5") (pin "21") (pinfunction "21(SCL)_21") (pintype "unspecified"))
    )
    (net (code "228") (name "SDA") (class "Default")
      (node (ref "CN2") (pin "3") (pinfunction "3_3") (pintype "unspecified"))
      (node (ref "CN4") (pin "3") (pinfunction "3_3") (pintype "unspecified"))
      (node (ref "R11") (pin "2") (pinfunction "2_2") (pintype "input"))
      (node (ref "U5") (pin "20") (pinfunction "20(SDA)_20") (pintype "unspecified"))
    )
    (net (code "229") (name "SPEED") (class "Default")
      (node (ref "R6") (pin "2") (pinfunction "2_2") (pintype "input"))
      (node (ref "U5") (pin "23") (pinfunction "23_23") (pintype "unspecified"))
    )
    (net (code "230") (name "unconnected-(U5-0(RX0)-Pad0)") (class "Default")
      (node (ref "U5") (pin "0") (pinfunction "0(RX0)_0") (pintype "unspecified"))
    )
    (net (code "231") (name "unconnected-(U5-1(TX0)-Pad1)") (class "Default")
      (node (ref "U5") (pin "1") (pinfunction "1(TX0)_1") (pintype "unspecified"))
    )
    (net (code "232") (name "unconnected-(U5-14(TX3)-Pad14)") (class "Default")
      (node (ref "U5") (pin "14") (pinfunction "14(TX3)_14") (pintype "unspecified"))
    )
    (net (code "233") (name "unconnected-(U5-15(RX3)-Pad15)") (class "Default")
      (node (ref "U5") (pin "15") (pinfunction "15(RX3)_15") (pintype "unspecified"))
    )
    (net (code "234") (name "unconnected-(U5-16(TX2)-Pad16)") (class "Default")
      (node (ref "U5") (pin "16") (pinfunction "16(TX2)_16") (pintype "unspecified"))
    )
    (net (code "235") (name "unconnected-(U5-A0(RX0)-PadA0)") (class "Default")
      (node (ref "U5") (pin "A0") (pinfunction "A0(RX0)_A0") (pintype "unspecified"))
    )
    (net (code "236") (name "unconnected-(U5-A1(TX0)-PadA1)") (class "Default")
      (node (ref "U5") (pin "A1") (pinfunction "A1(TX0)_A1") (pintype "unspecified"))
    )
    (net (code "237") (name "unconnected-(U5-Pad3.3V)") (class "Default")
      (node (ref "U5") (pin "3.3V") (pinfunction "3.3V_3.3V") (pintype "unspecified"))
    )
    (net (code "238") (name "unconnected-(U5-Pad13)") (class "Default")
      (node (ref "U5") (pin "13") (pinfunction "13_13") (pintype "unspecified"))
    )
    (net (code "239") (name "unconnected-(U5-Pad22)") (class "Default")
      (node (ref "U5") (pin "22") (pinfunction "22_22") (pintype "unspecified"))
    )
    (net (code "240") (name "unconnected-(U5-Pad24)") (class "Default")
      (node (ref "U5") (pin "24") (pinfunction "24_24") (pintype "unspecified"))
    )
    (net (code "241") (name "unconnected-(U5-Pad26)") (class "Default")
      (node (ref "U5") (pin "26") (pinfunction "26_26") (pintype "unspecified"))
    )
    (net (code "242") (name "unconnected-(U5-Pad28)") (class "Default")
      (node (ref "U5") (pin "28") (pinfunction "28_28") (pintype "unspecified"))
    )
    (net (code "243") (name "unconnected-(U5-Pad30)") (class "Default")
      (node (ref "U5") (pin "30") (pinfunction "30_30") (pintype "unspecified"))
    )
    (net (code "244") (name "unconnected-(U5-Pad32)") (class "Default")
      (node (ref "U5") (pin "32") (pinfunction "32_32") (pintype "unspecified"))
    )
    (net (code "245") (name "unconnected-(U5-Pad34)") (class "Default")
      (node (ref "U5") (pin "34") (pinfunction "34_34") (pintype "unspecified"))
    )
    (net (code "246") (name "unconnected-(U5-Pad36)") (class "Default")
      (node (ref "U5") (pin "36") (pinfunction "36_36") (pintype "unspecified"))
    )
    (net (code "247") (name "unconnected-(U5-Pad38)") (class "Default")
      (node (ref "U5") (pin "38") (pinfunction "38_38") (pintype "unspecified"))
    )
    (net (code "248") (name "unconnected-(U5-Pad40)") (class "Default")
      (node (ref "U5") (pin "40") (pinfunction "40_40") (pintype "unspecified"))
    )
    (net (code "249") (name "unconnected-(U5-Pad42)") (class "Default")
      (node (ref "U5") (pin "42") (pinfunction "42_42") (pintype "unspecified"))
    )
    (net (code "250") (name "unconnected-(U5-Pad44)") (class "Default")
      (node (ref "U5") (pin "44") (pinfunction "44_44") (pintype "unspecified"))
    )
    (net (code "251") (name "unconnected-(U5-Pad46)") (class "Default")
      (node (ref "U5") (pin "46") (pinfunction "46_46") (pintype "unspecified"))
    )
    (net (code "252") (name "unconnected-(U5-Pad48)") (class "Default")
      (node (ref "U5") (pin "48") (pinfunction "48_48") (pintype "unspecified"))
    )
    (net (code "253") (name "unconnected-(U5-Pad50)") (class "Default")
      (node (ref "U5") (pin "50") (pinfunction "50_50") (pintype "unspecified"))
    )
    (net (code "254") (name "unconnected-(U5-Pad52)") (class "Default")
      (node (ref "U5") (pin "52") (pinfunction "52_52") (pintype "unspecified"))
    )
    (net (code "255") (name "unconnected-(U5-Pad53)") (class "Default")
      (node (ref "U5") (pin "53") (pinfunction "53_53") (pintype "unspecified"))
    )
    (net (code "256") (name "unconnected-(U5-PadA2)") (class "Default")
      (node (ref "U5") (pin "A2") (pinfunction "A2_A2") (pintype "unspecified"))
    )
    (net (code "257") (name "unconnected-(U5-PadA3)") (class "Default")
      (node (ref "U5") (pin "A3") (pinfunction "A3_A3") (pintype "unspecified"))
    )
    (net (code "258") (name "unconnected-(U5-PadA4)") (class "Default")
      (node (ref "U5") (pin "A4") (pinfunction "A4_A4") (pintype "unspecified"))
    )
    (net (code "259") (name "unconnected-(U5-PadA7)") (class "Default")
      (node (ref "U5") (pin "A7") (pinfunction "A7_A7") (pintype "unspecified"))
    )
    (net (code "260") (name "unconnected-(U5-PadA10)") (class "Default")
      (node (ref "U5") (pin "A10") (pinfunction "A10_A10") (pintype "unspecified"))
    )
    (net (code "261") (name "unconnected-(U5-PadA11)") (class "Default")
      (node (ref "U5") (pin "A11") (pinfunction "A11_A11") (pintype "unspecified"))
    )
    (net (code "262") (name "unconnected-(U5-PadA12)") (class "Default")
      (node (ref "U5") (pin "A12") (pinfunction "A12_A12") (pintype "unspecified"))
    )
    (net (code "263") (name "unconnected-(U5-PadA13)") (class "Default")
      (node (ref "U5") (pin "A13") (pinfunction "A13_A13") (pintype "unspecified"))
    )
    (net (code "264") (name "unconnected-(U5-PadA14)") (class "Default")
      (node (ref "U5") (pin "A14") (pinfunction "A14_A14") (pintype "unspecified"))
    )
    (net (code "265") (name "unconnected-(U5-PadA15)") (class "Default")
      (node (ref "U5") (pin "A15") (pinfunction "A15_A15") (pintype "unspecified"))
    )
    (net (code "266") (name "unconnected-(U5-PadAREF)") (class "Default")
      (node (ref "U5") (pin "AREF") (pinfunction "AREF_AREF") (pintype "unspecified"))
    )
    (net (code "267") (name "unconnected-(U5-PadISP1_1)") (class "Default")
      (node (ref "U5") (pin "ISP1_1") (pinfunction "ISP1_1_ISP1_1") (pintype "unspecified"))
    )
    (net (code "268") (name "unconnected-(U5-PadISP1_2)") (class "Default")
      (node (ref "U5") (pin "ISP1_2") (pinfunction "ISP1_2_ISP1_2") (pintype "unspecified"))
    )
    (net (code "269") (name "unconnected-(U5-PadISP1_3)") (class "Default")
      (node (ref "U5") (pin "ISP1_3") (pinfunction "ISP1_3_ISP1_3") (pintype "unspecified"))
    )
    (net (code "270") (name "unconnected-(U5-PadISP1_4)") (class "Default")
      (node (ref "U5") (pin "ISP1_4") (pinfunction "ISP1_4_ISP1_4") (pintype "unspecified"))
    )
    (net (code "271") (name "unconnected-(U5-PadISP1_5)") (class "Default")
      (node (ref "U5") (pin "ISP1_5") (pinfunction "ISP1_5_ISP1_5") (pintype "unspecified"))
    )
    (net (code "272") (name "unconnected-(U5-PadISP1_6)") (class "Default")
      (node (ref "U5") (pin "ISP1_6") (pinfunction "ISP1_6_ISP1_6") (pintype "unspecified"))
    )
    (net (code "273") (name "unconnected-(U5-PadRESET)") (class "Default")
      (node (ref "U5") (pin "RESET") (pinfunction "RESET_RESET") (pintype "unspecified"))
    )
  )
)
